# MEM_MUX_3.net
KiCad netlist of a schematic drawn in EAGLE
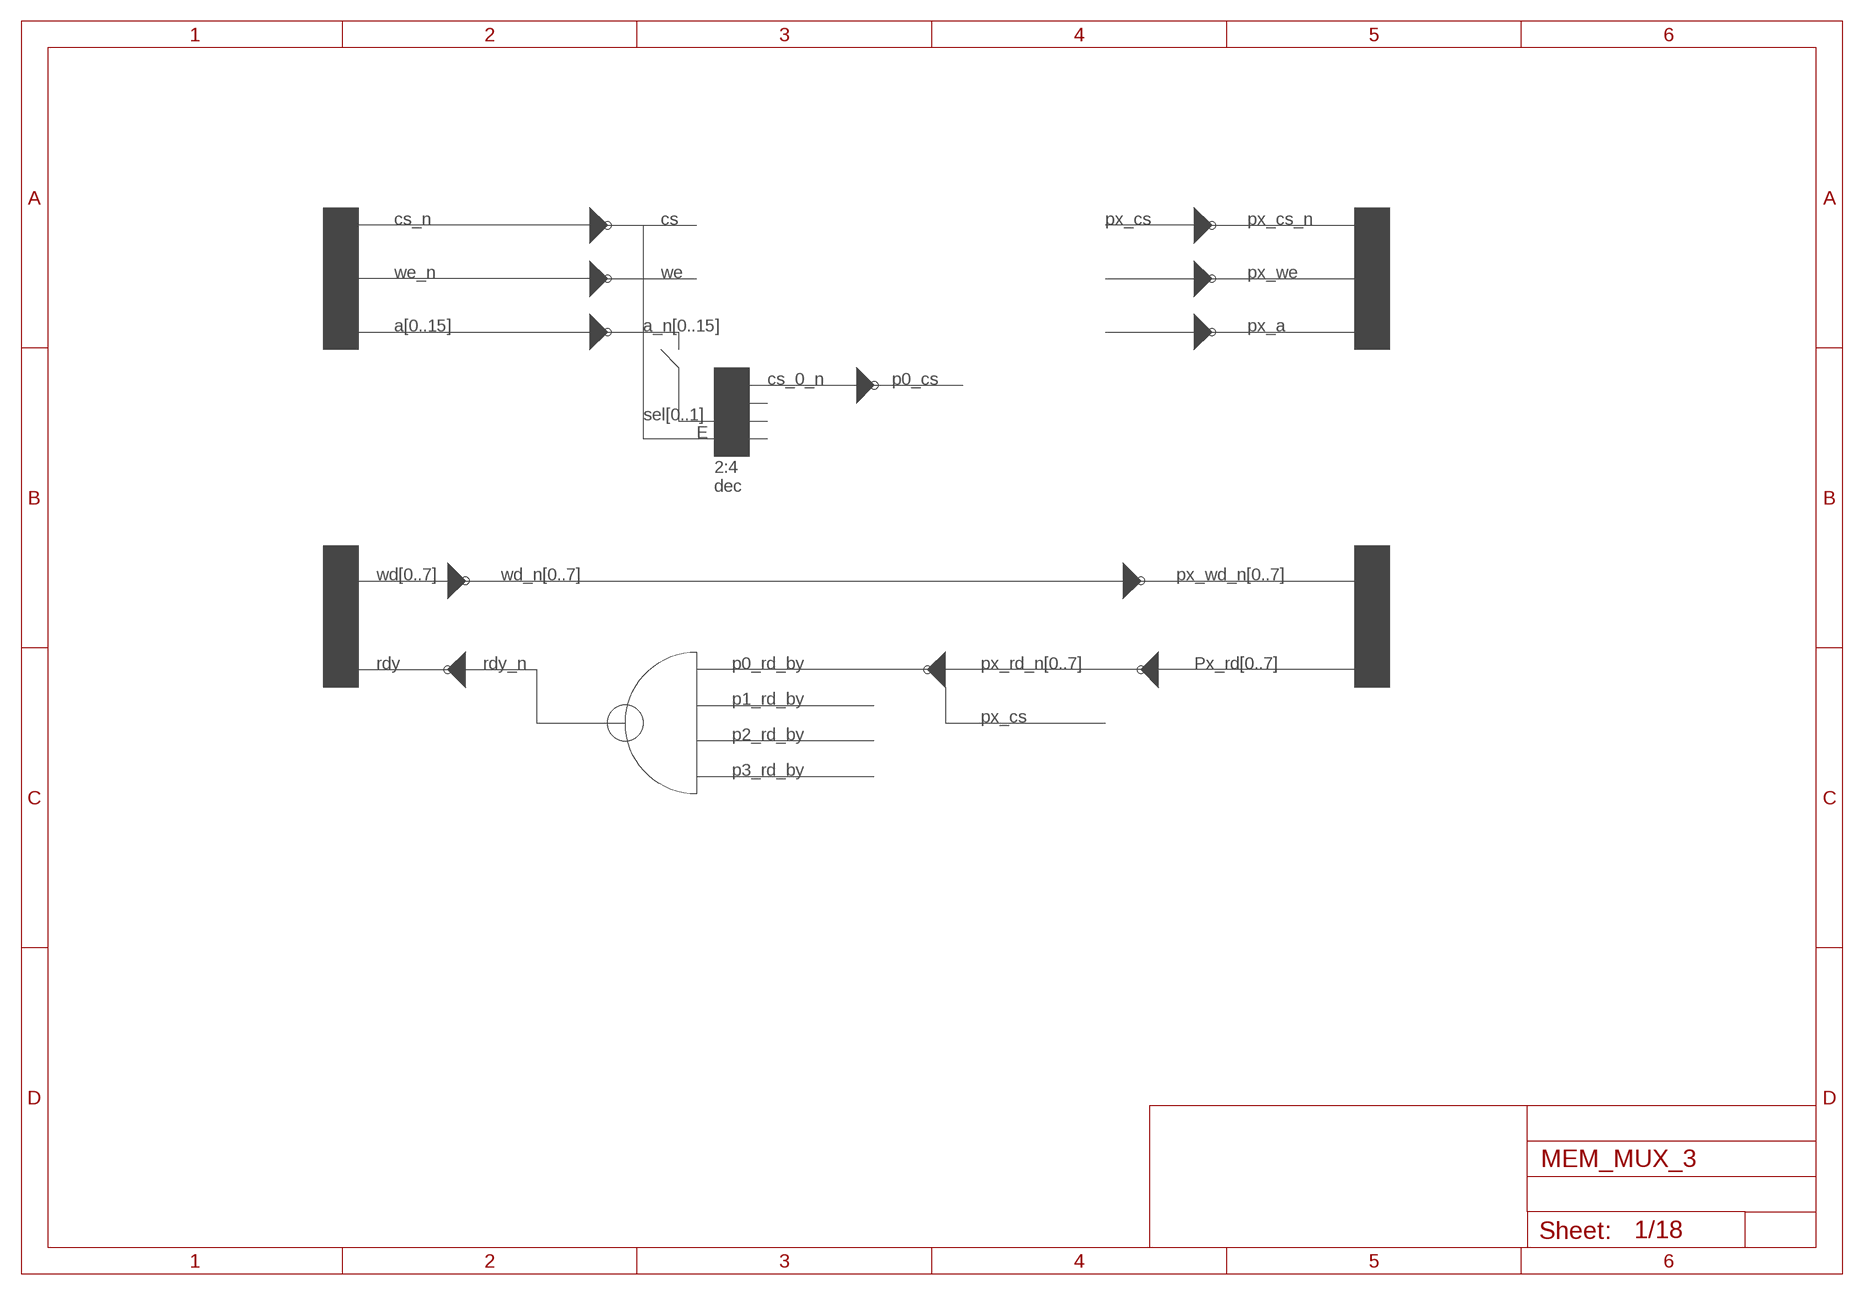
[diagram p0: schematic, sheet 1]
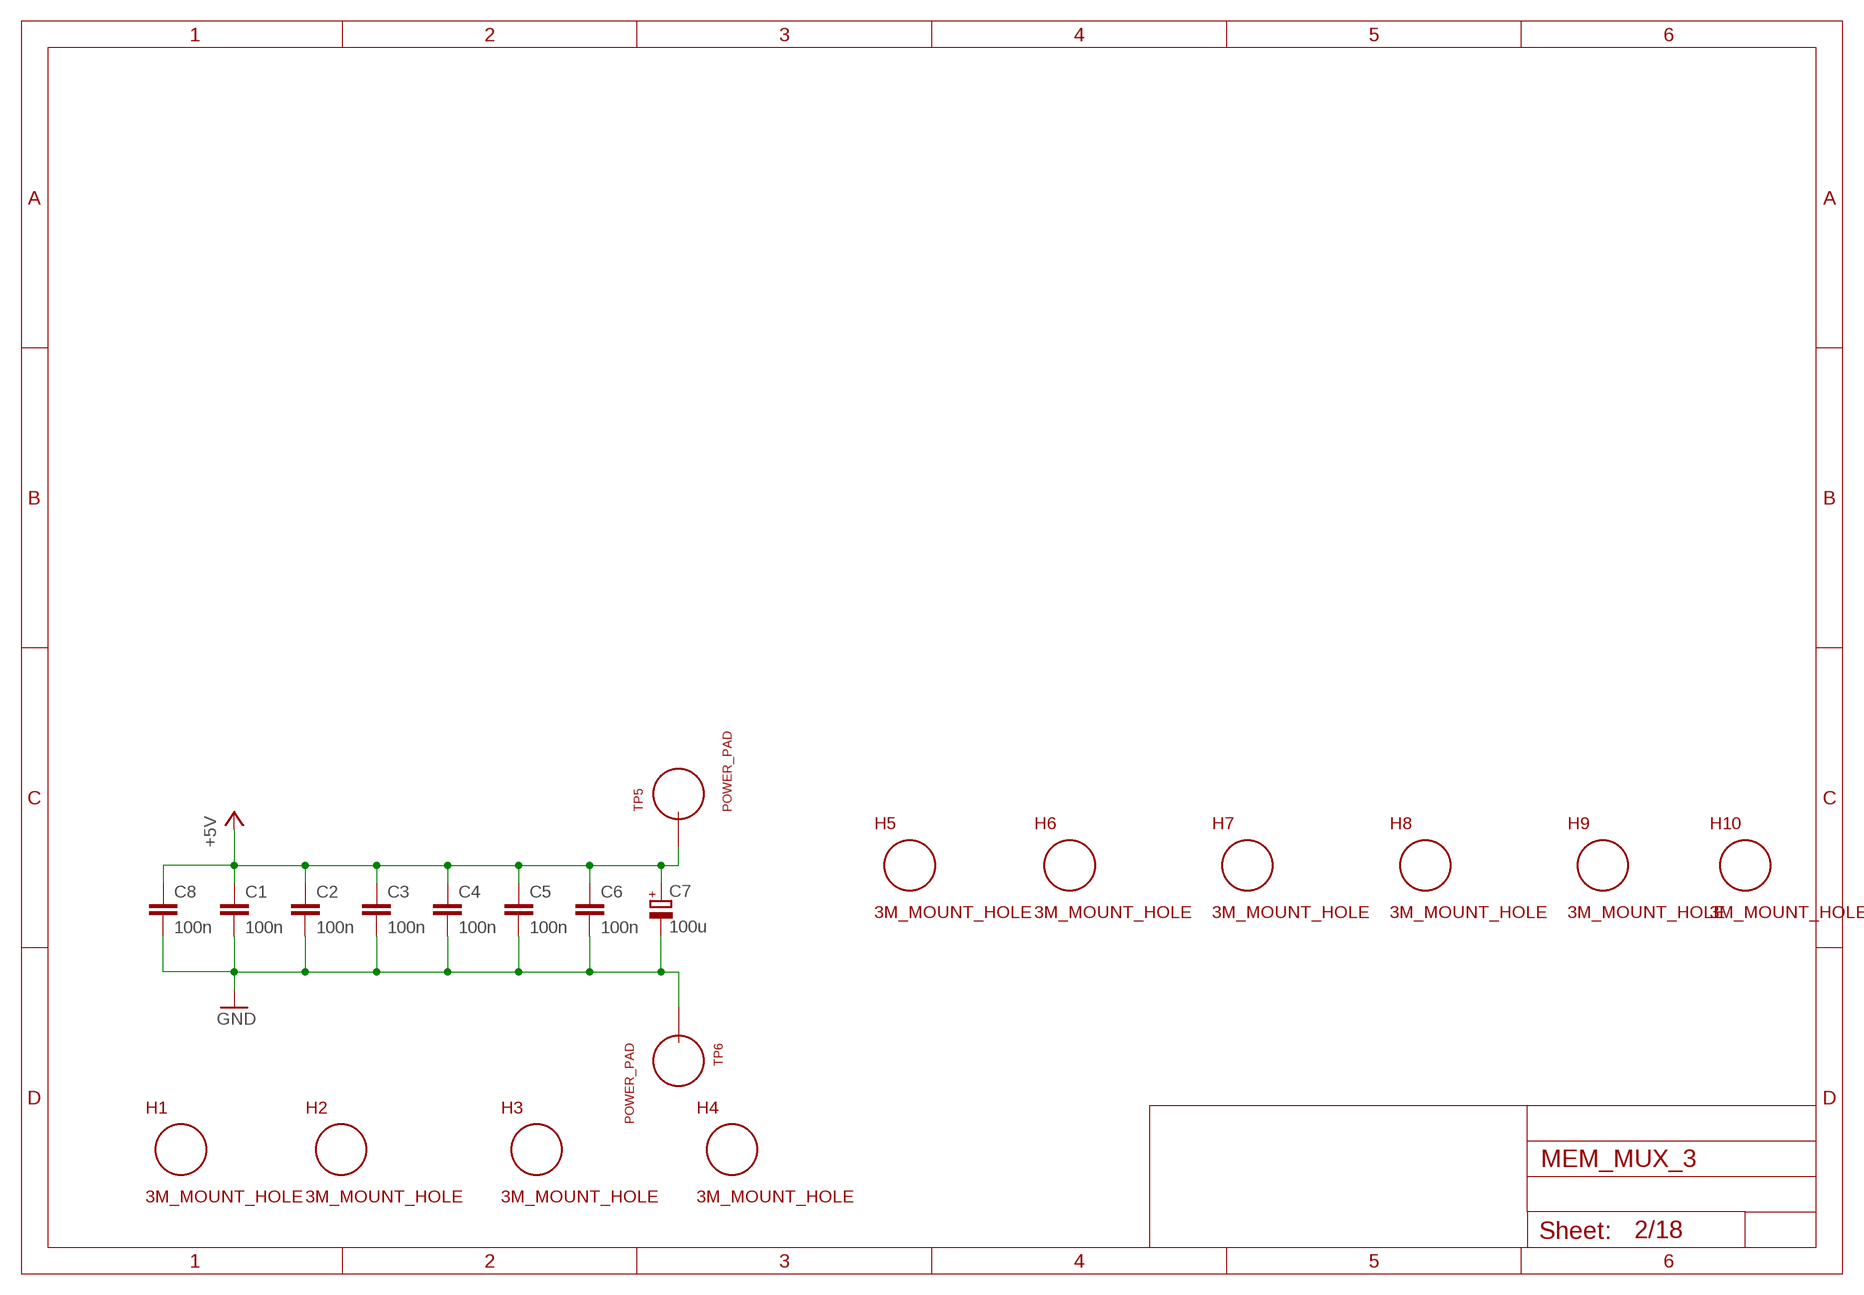
[diagram p1: schematic, sheet 2]
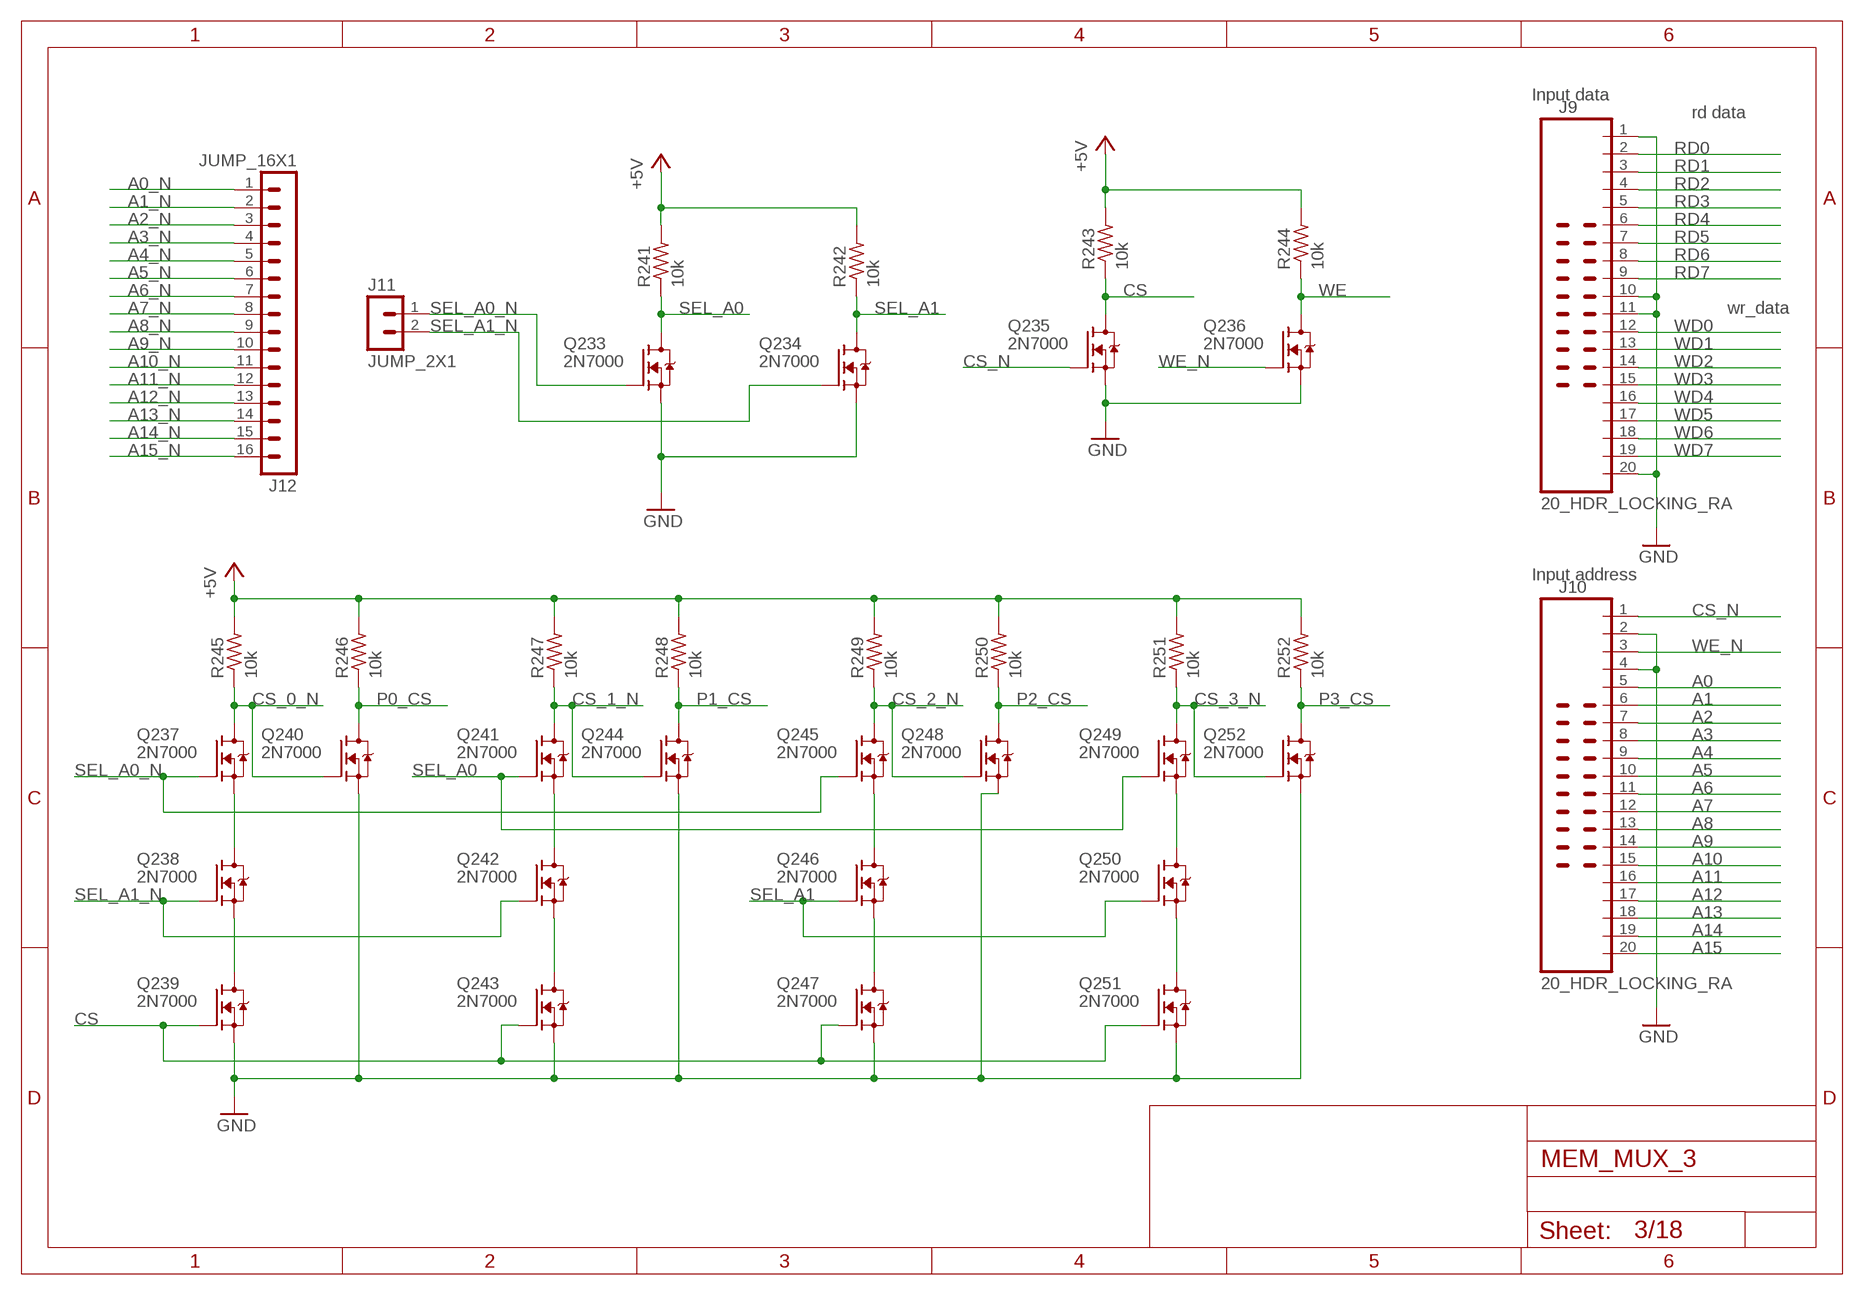
[diagram p2: schematic, sheet 3]
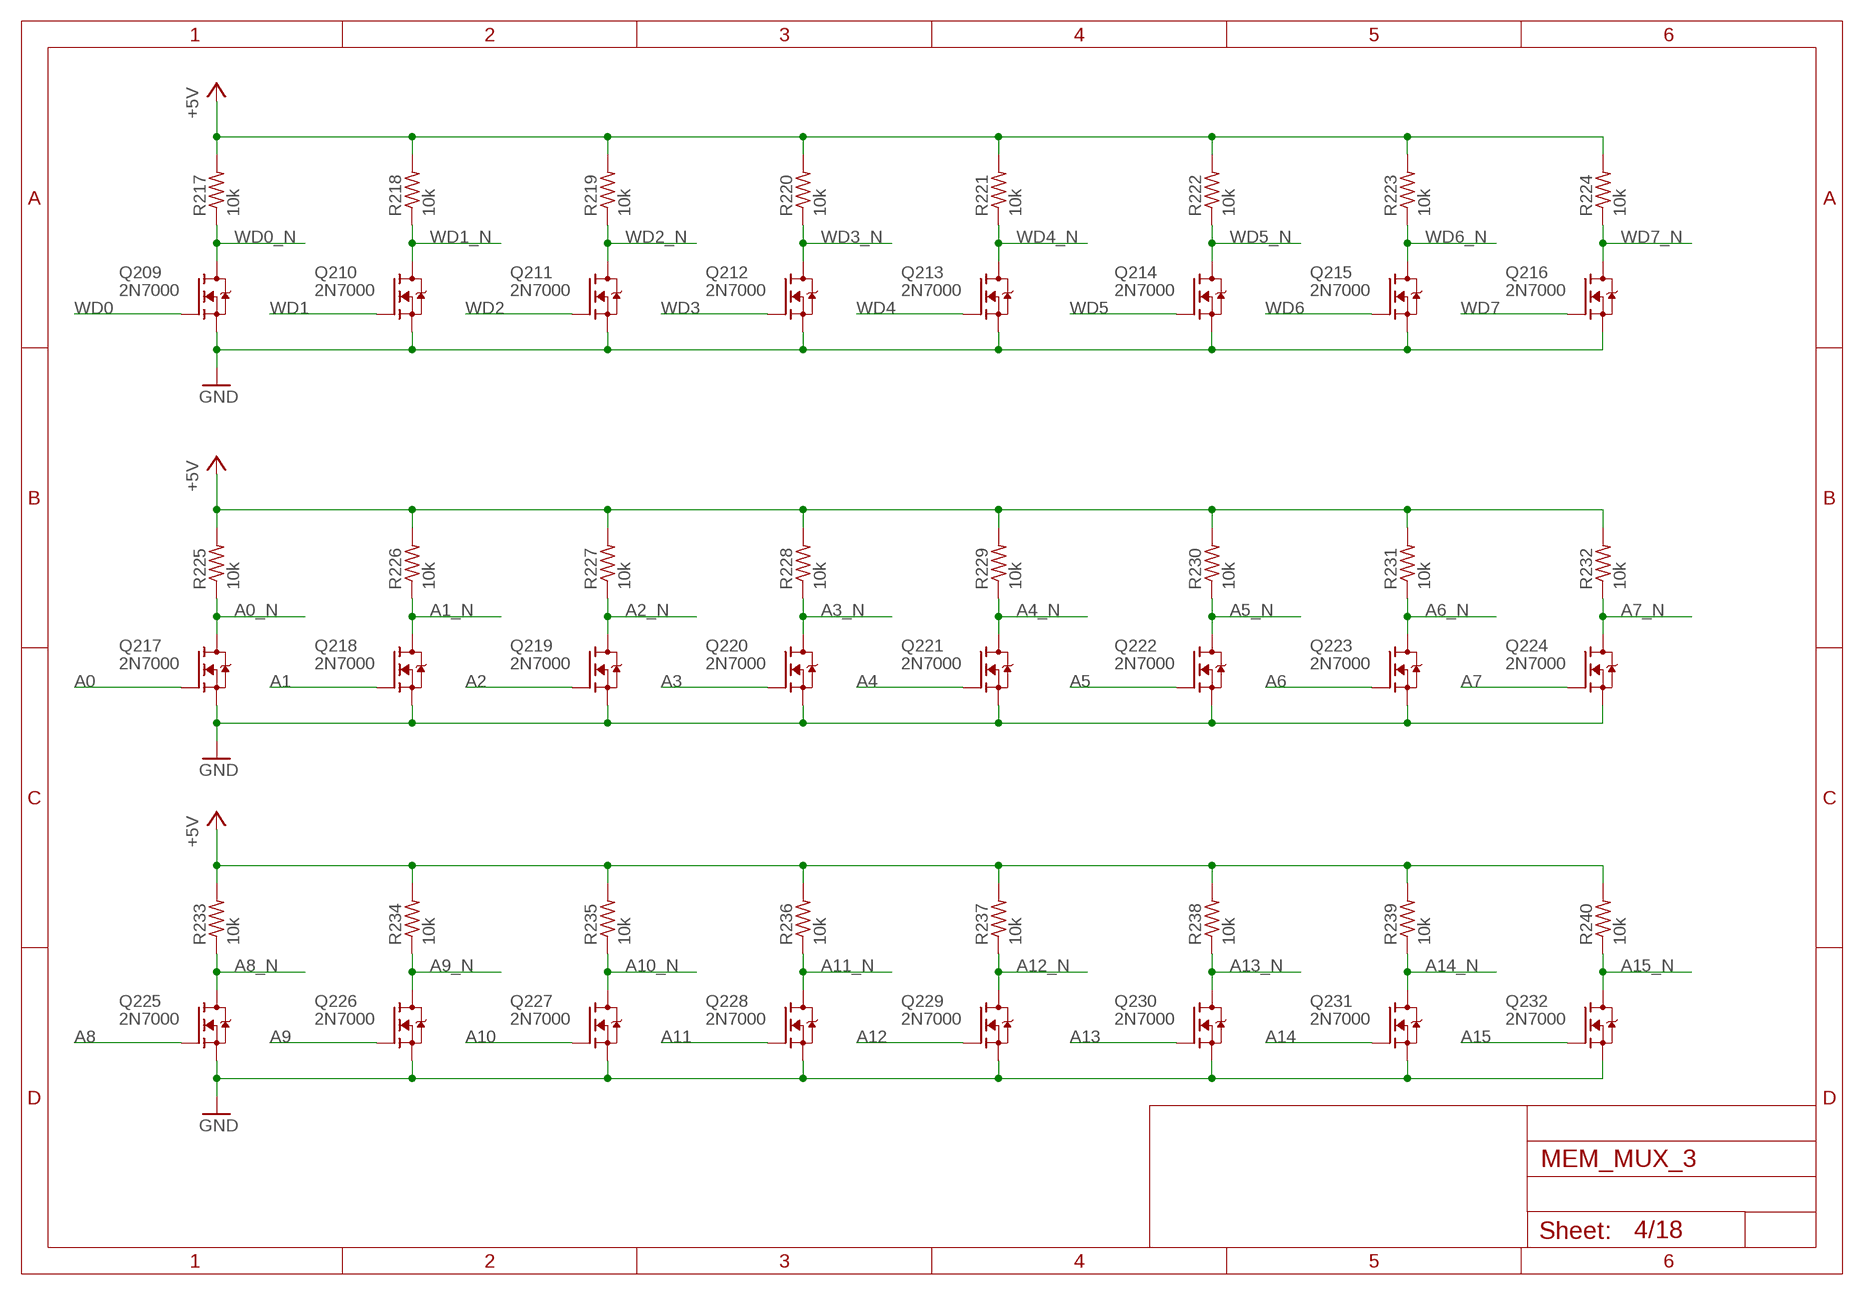
[diagram p3: schematic, sheet 4]
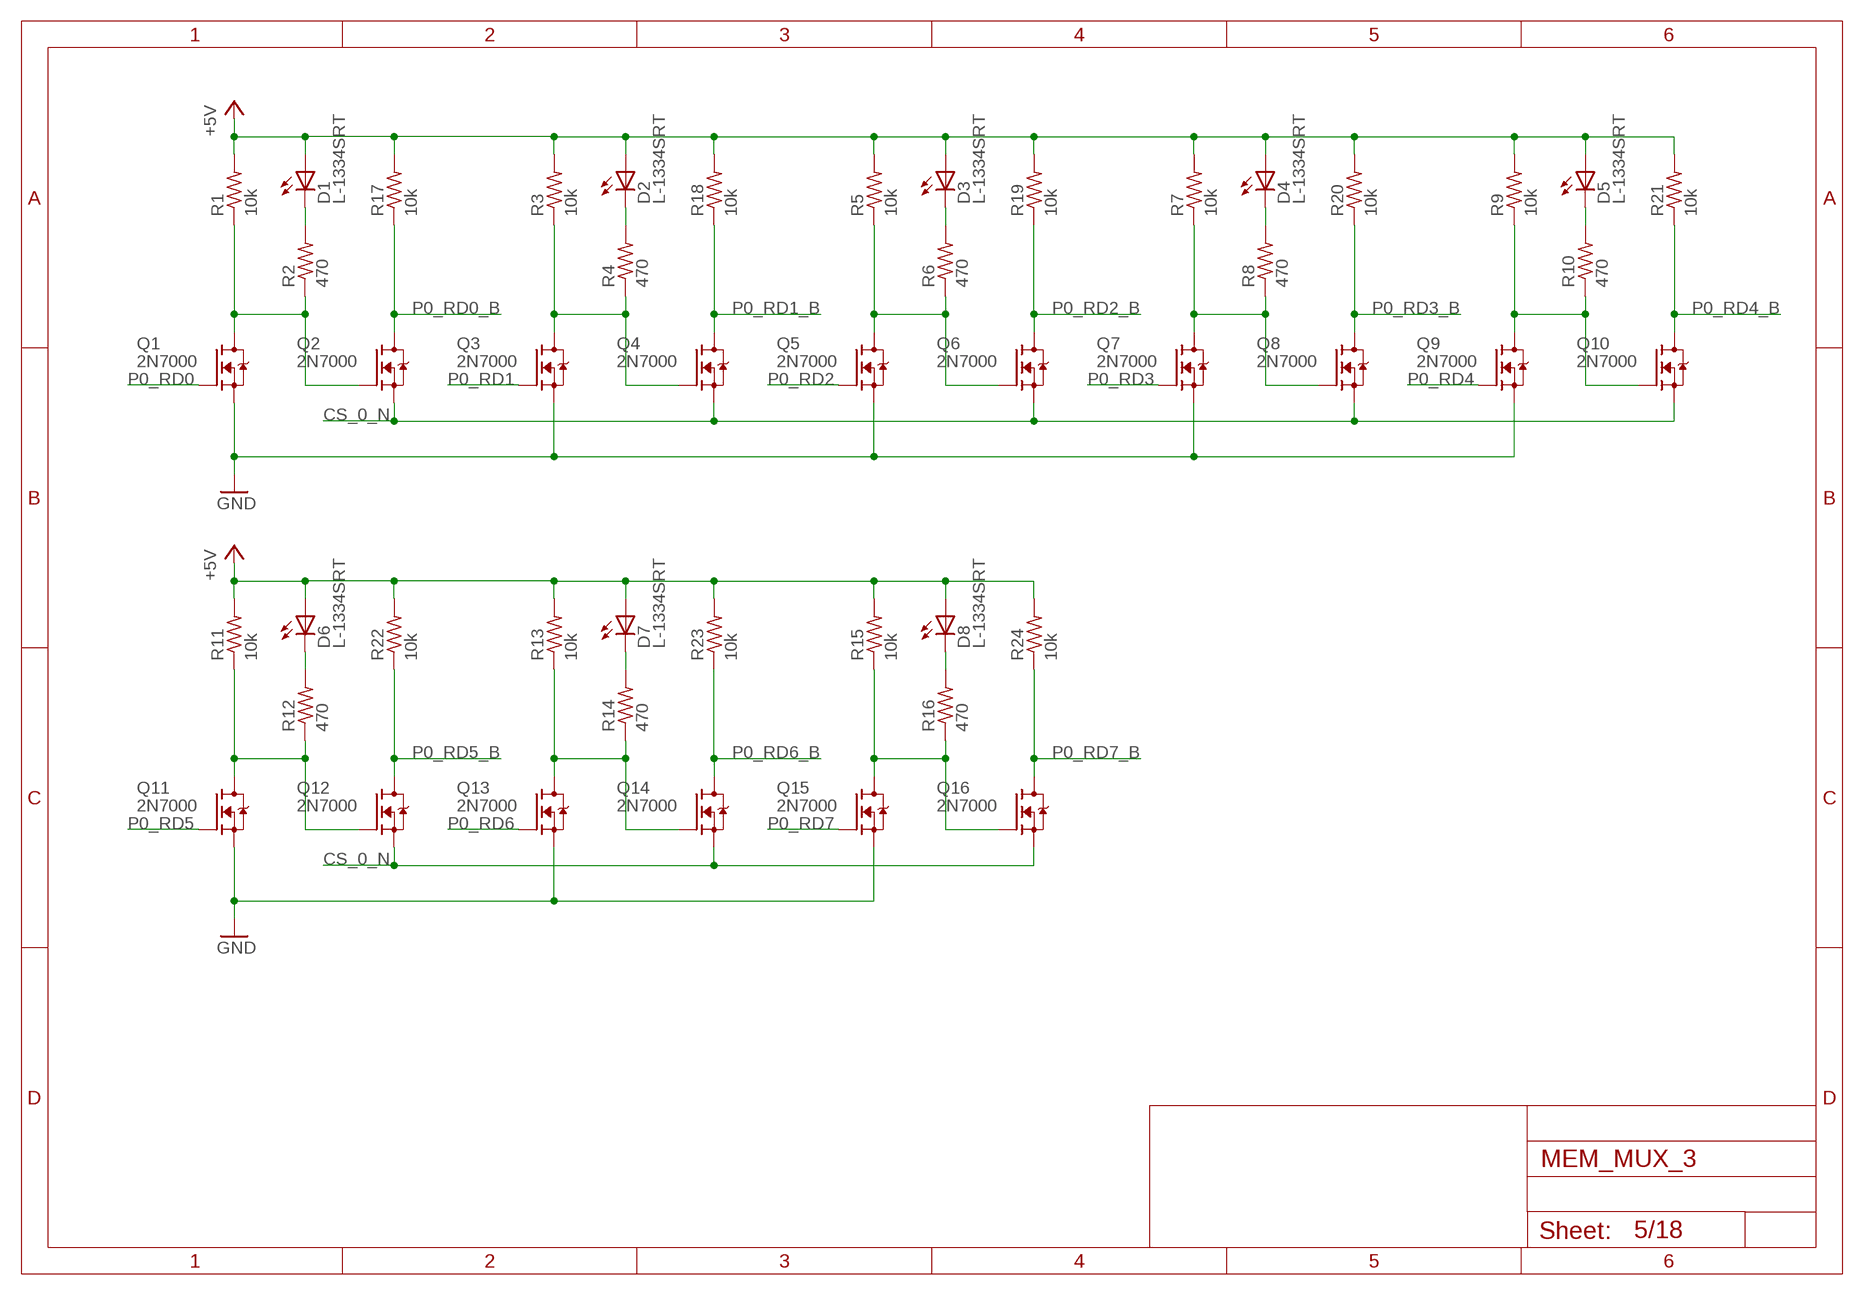
[diagram p4: schematic, sheet 5]
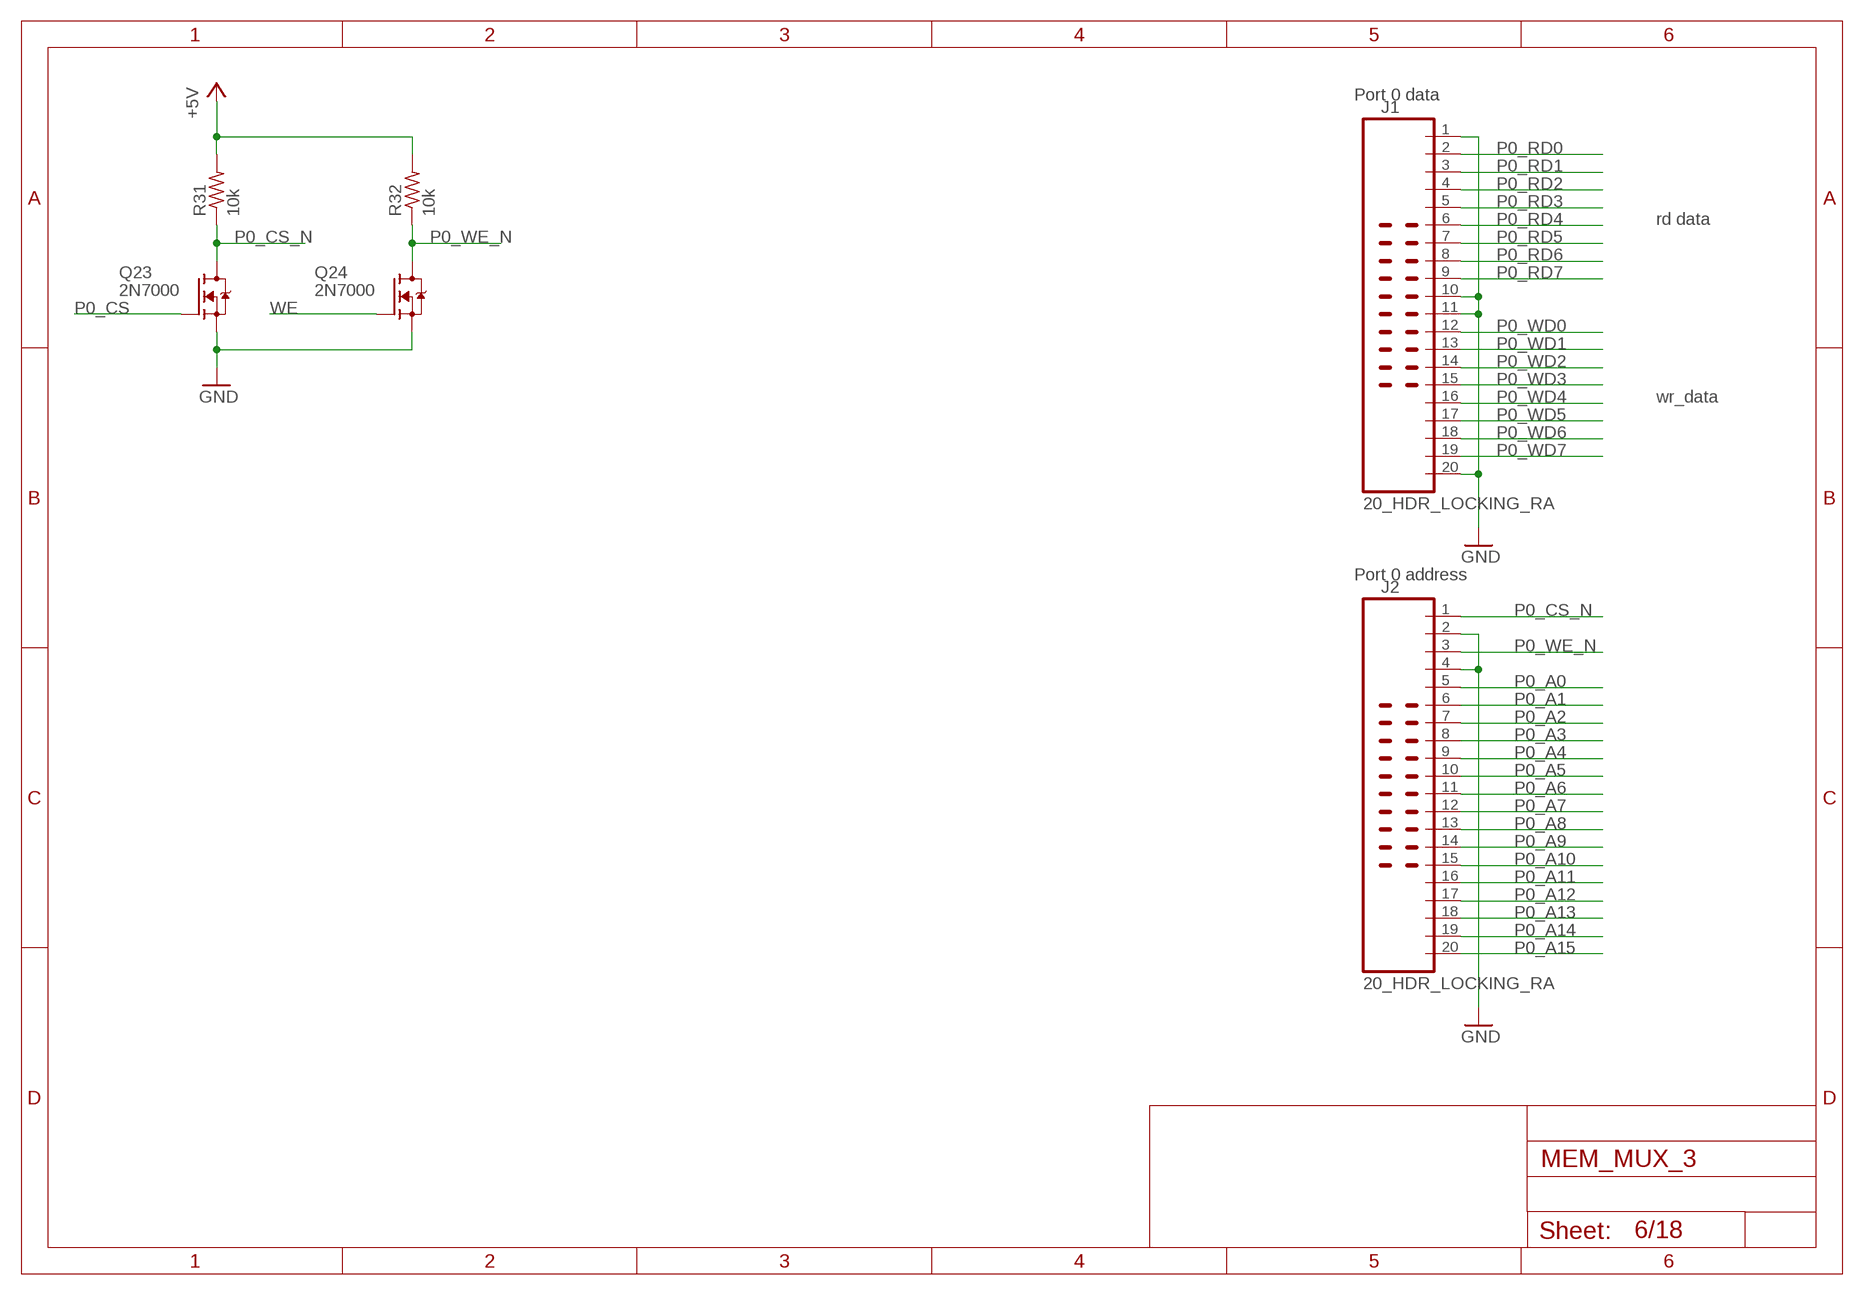
[diagram p5: schematic, sheet 6]
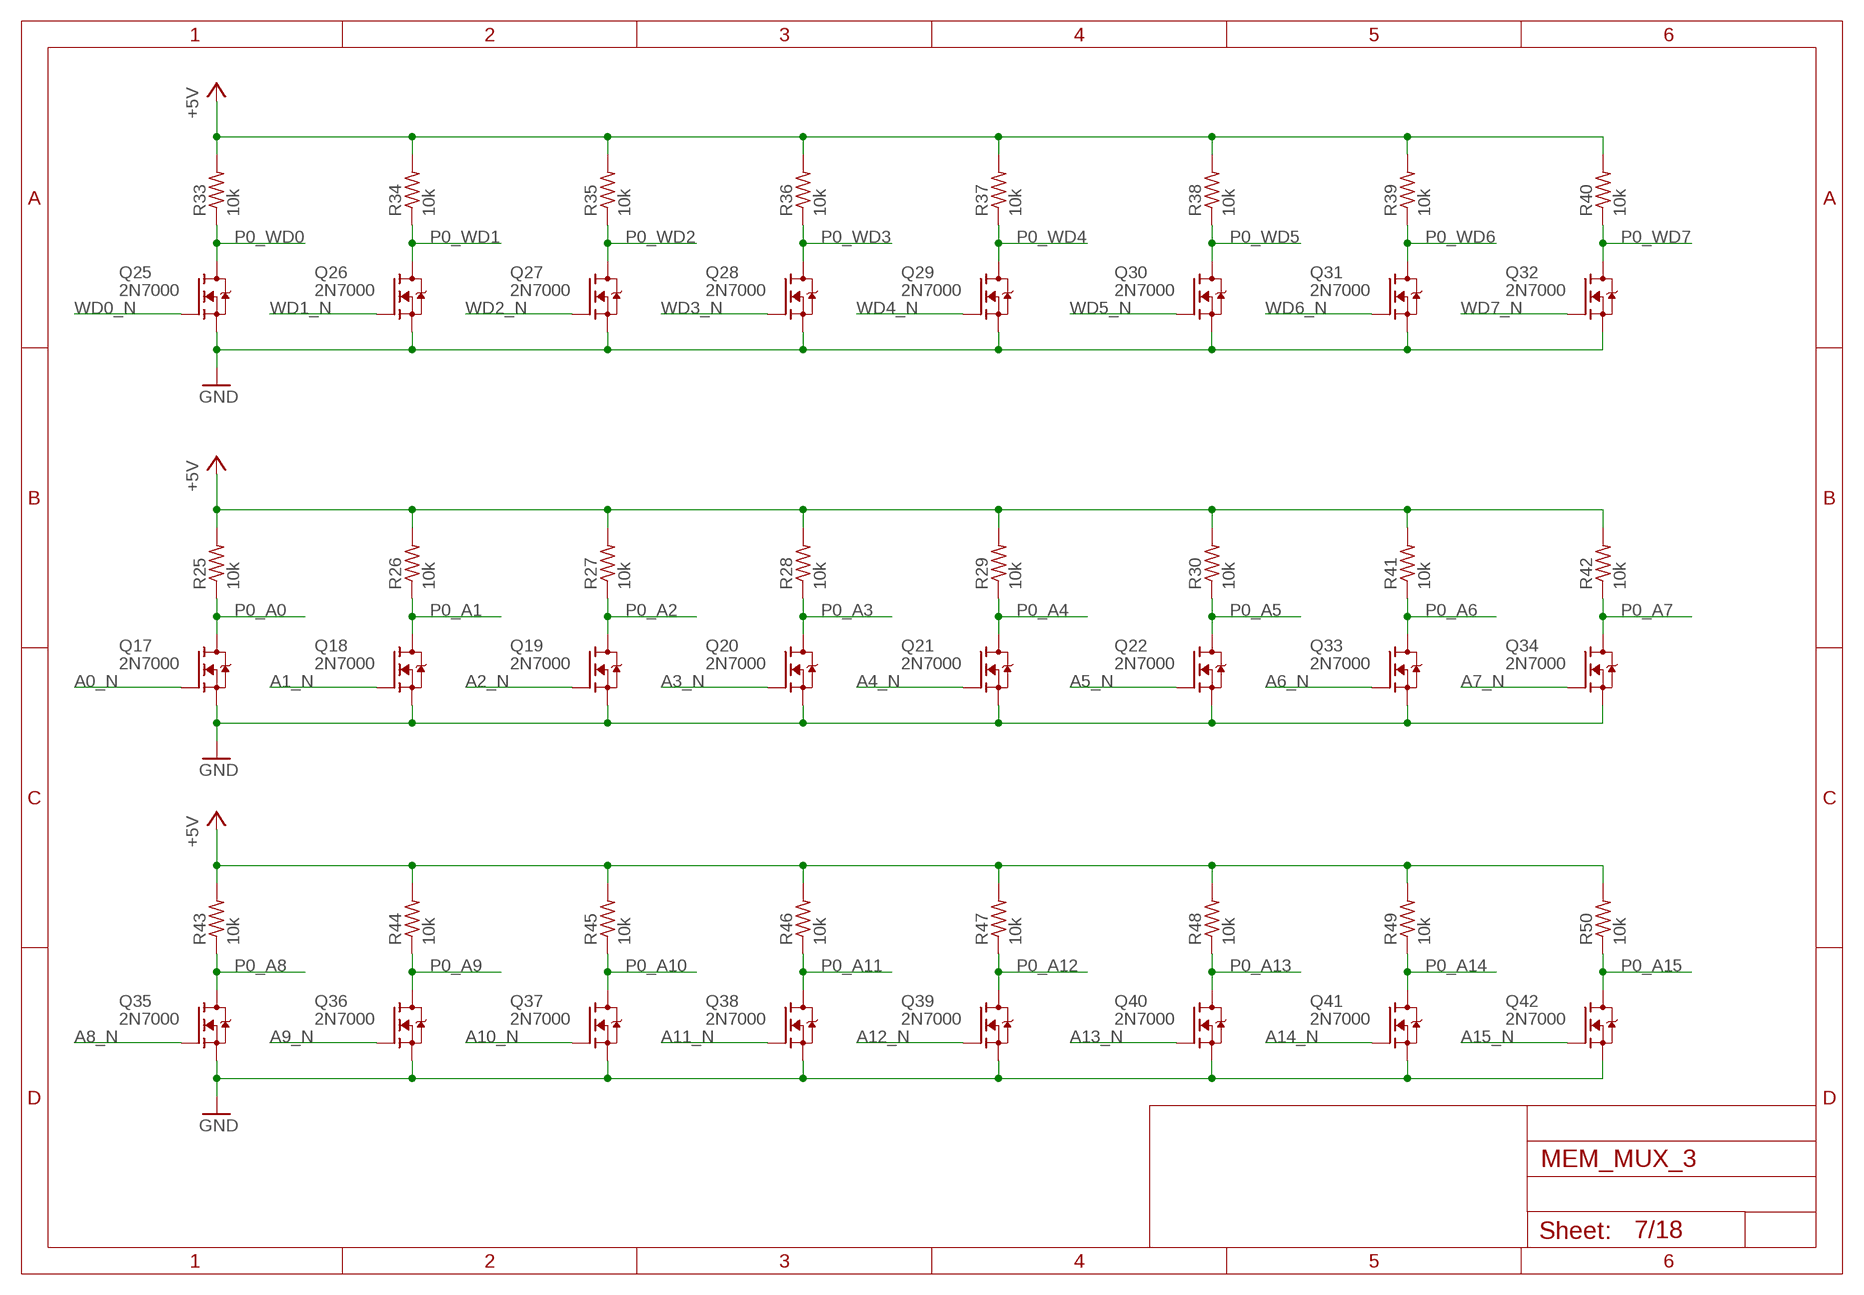
[diagram p6: schematic, sheet 7]
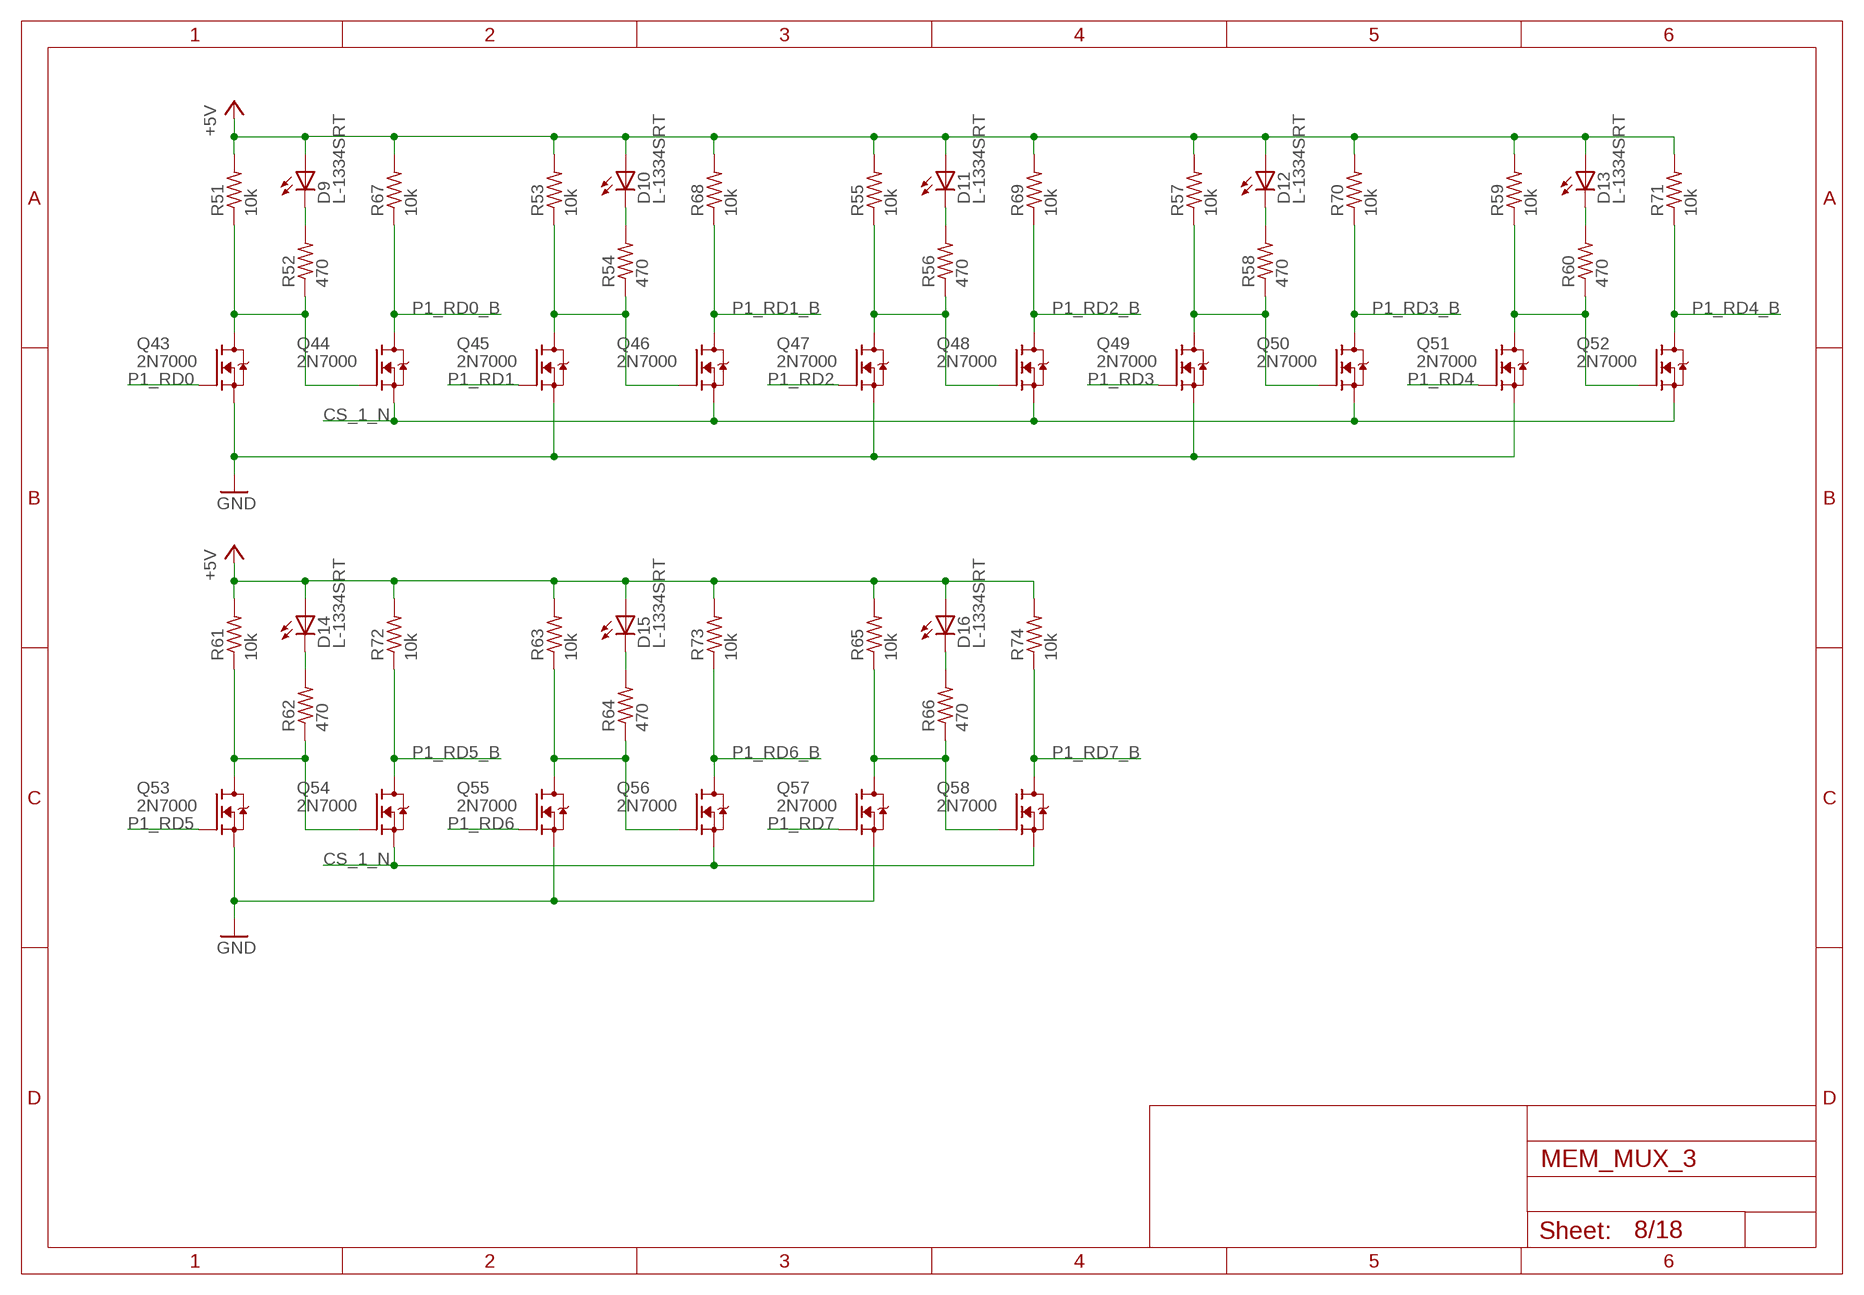
[diagram p7: schematic, sheet 8]
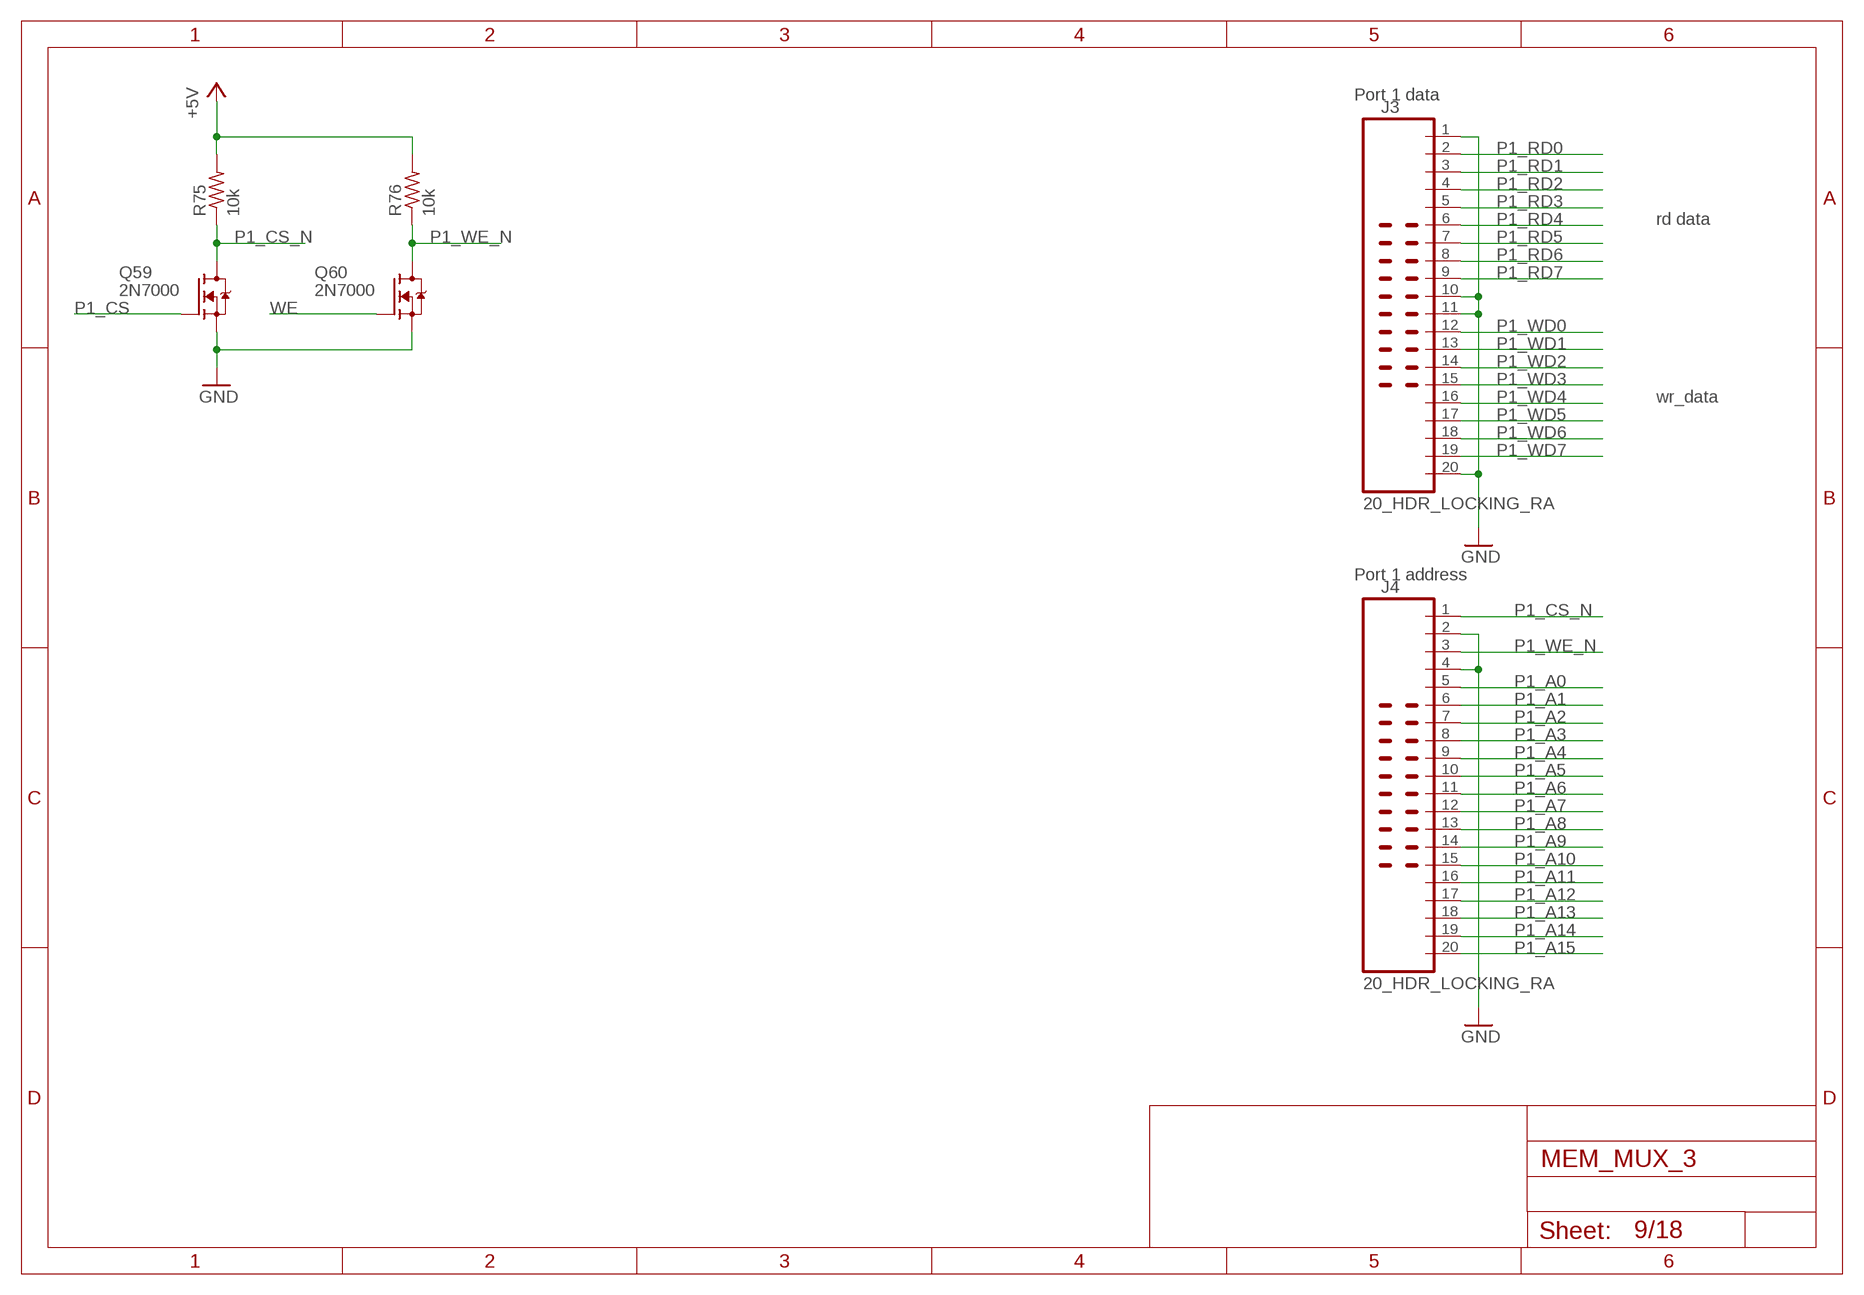
[diagram p8: schematic, sheet 9]
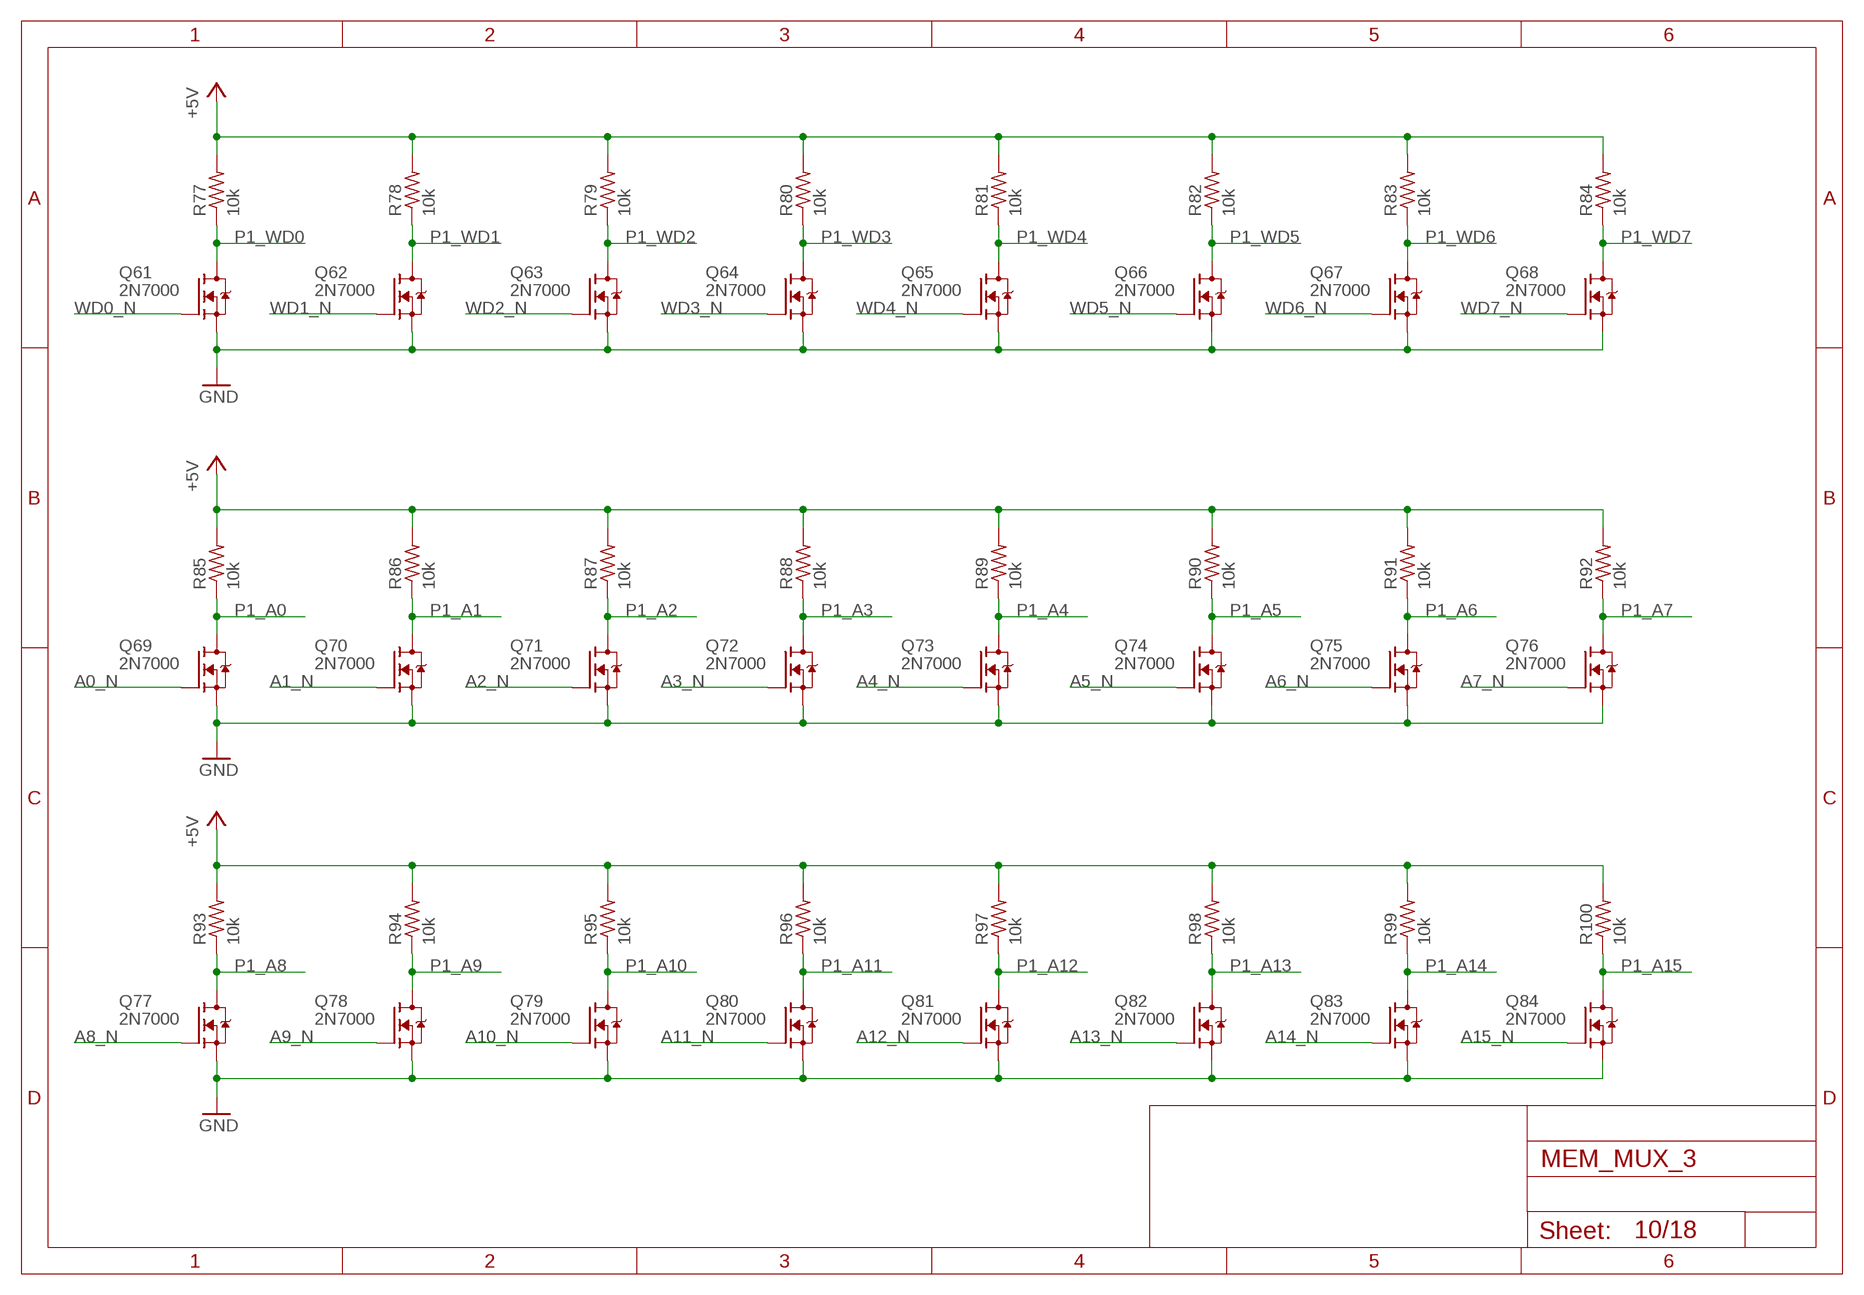
[diagram p9: schematic, sheet 10]
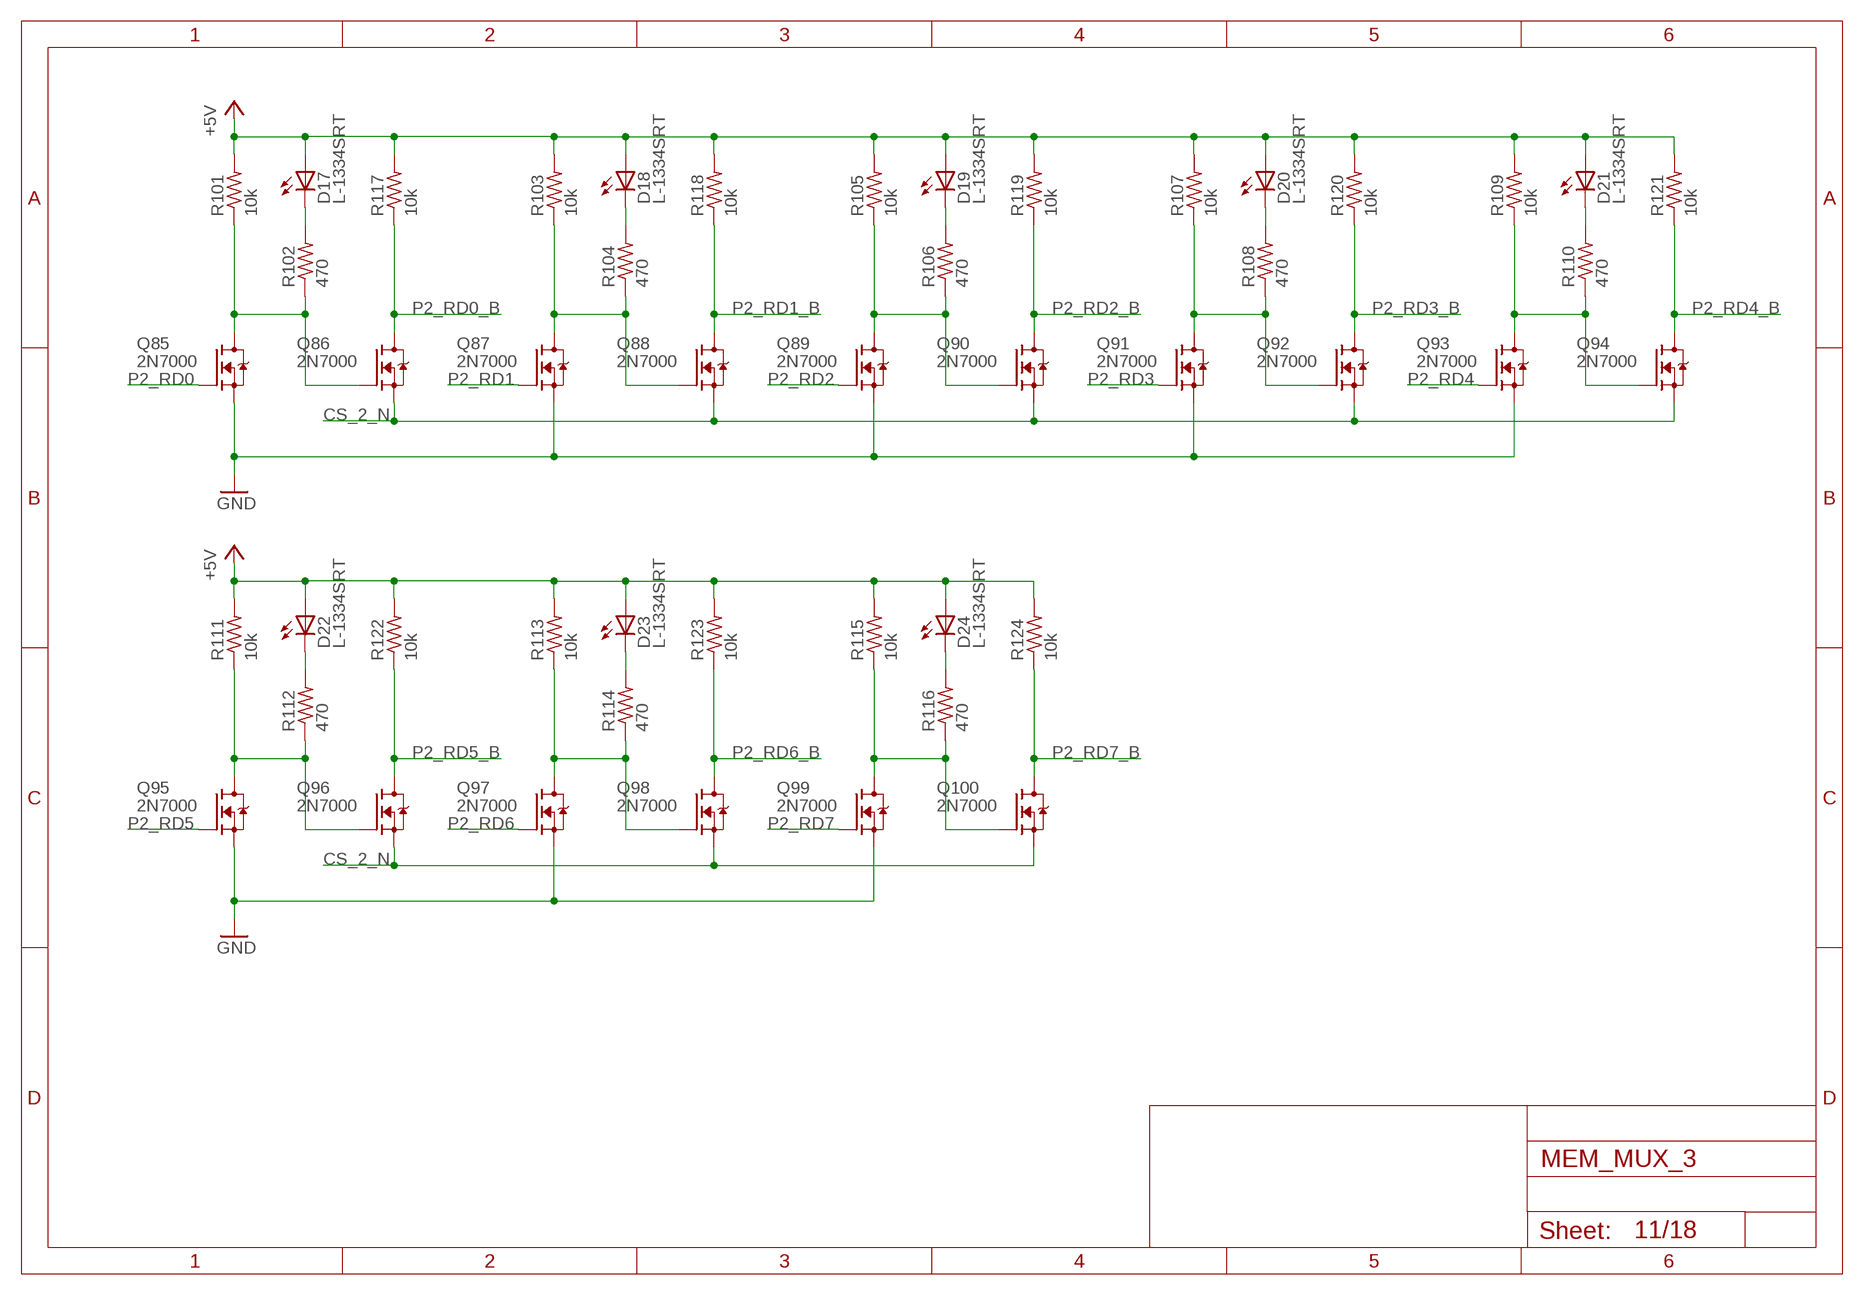
[diagram p10: schematic, sheet 11]
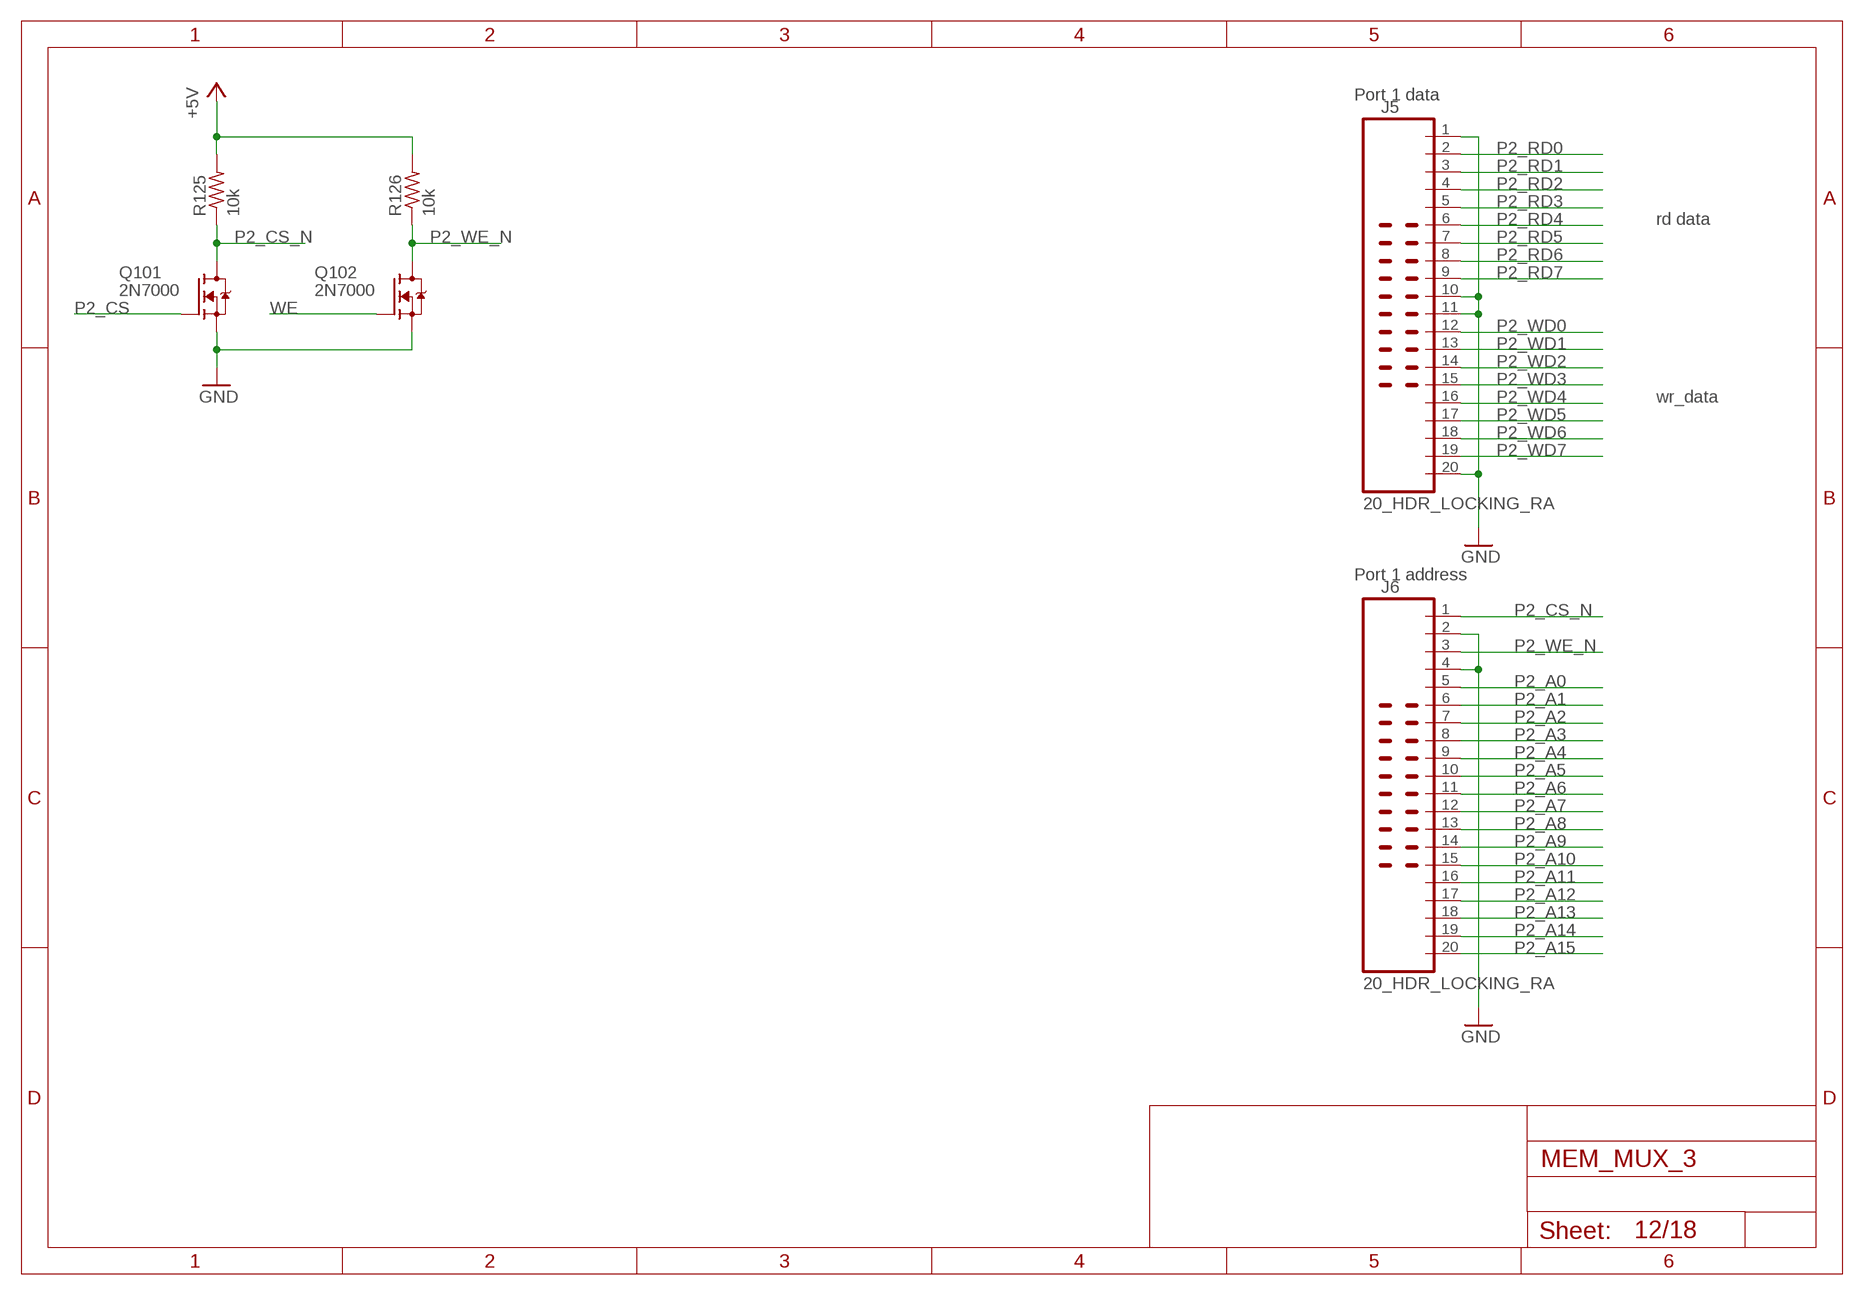
[diagram p11: schematic, sheet 12]
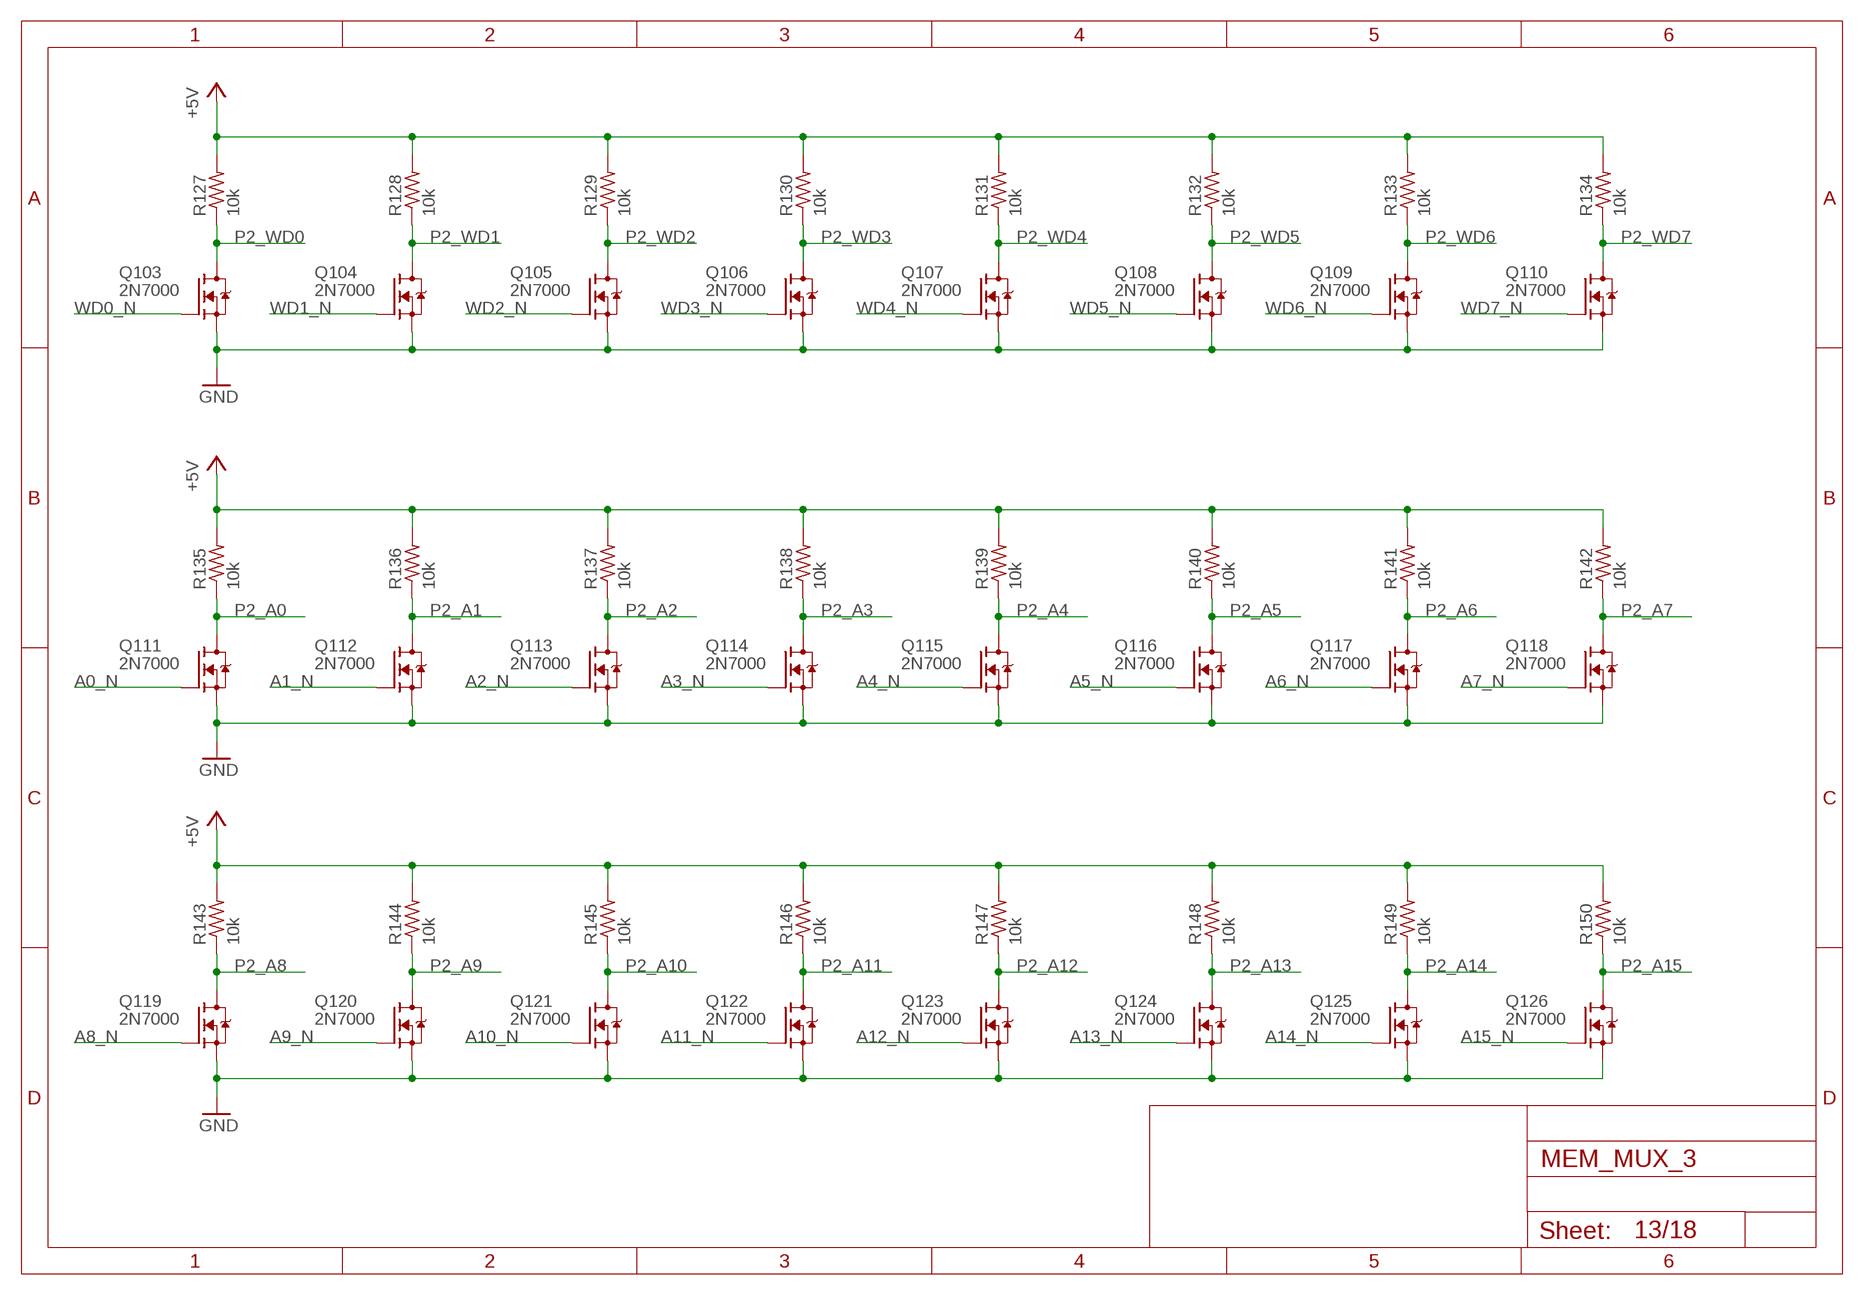
[diagram p12: schematic, sheet 13]
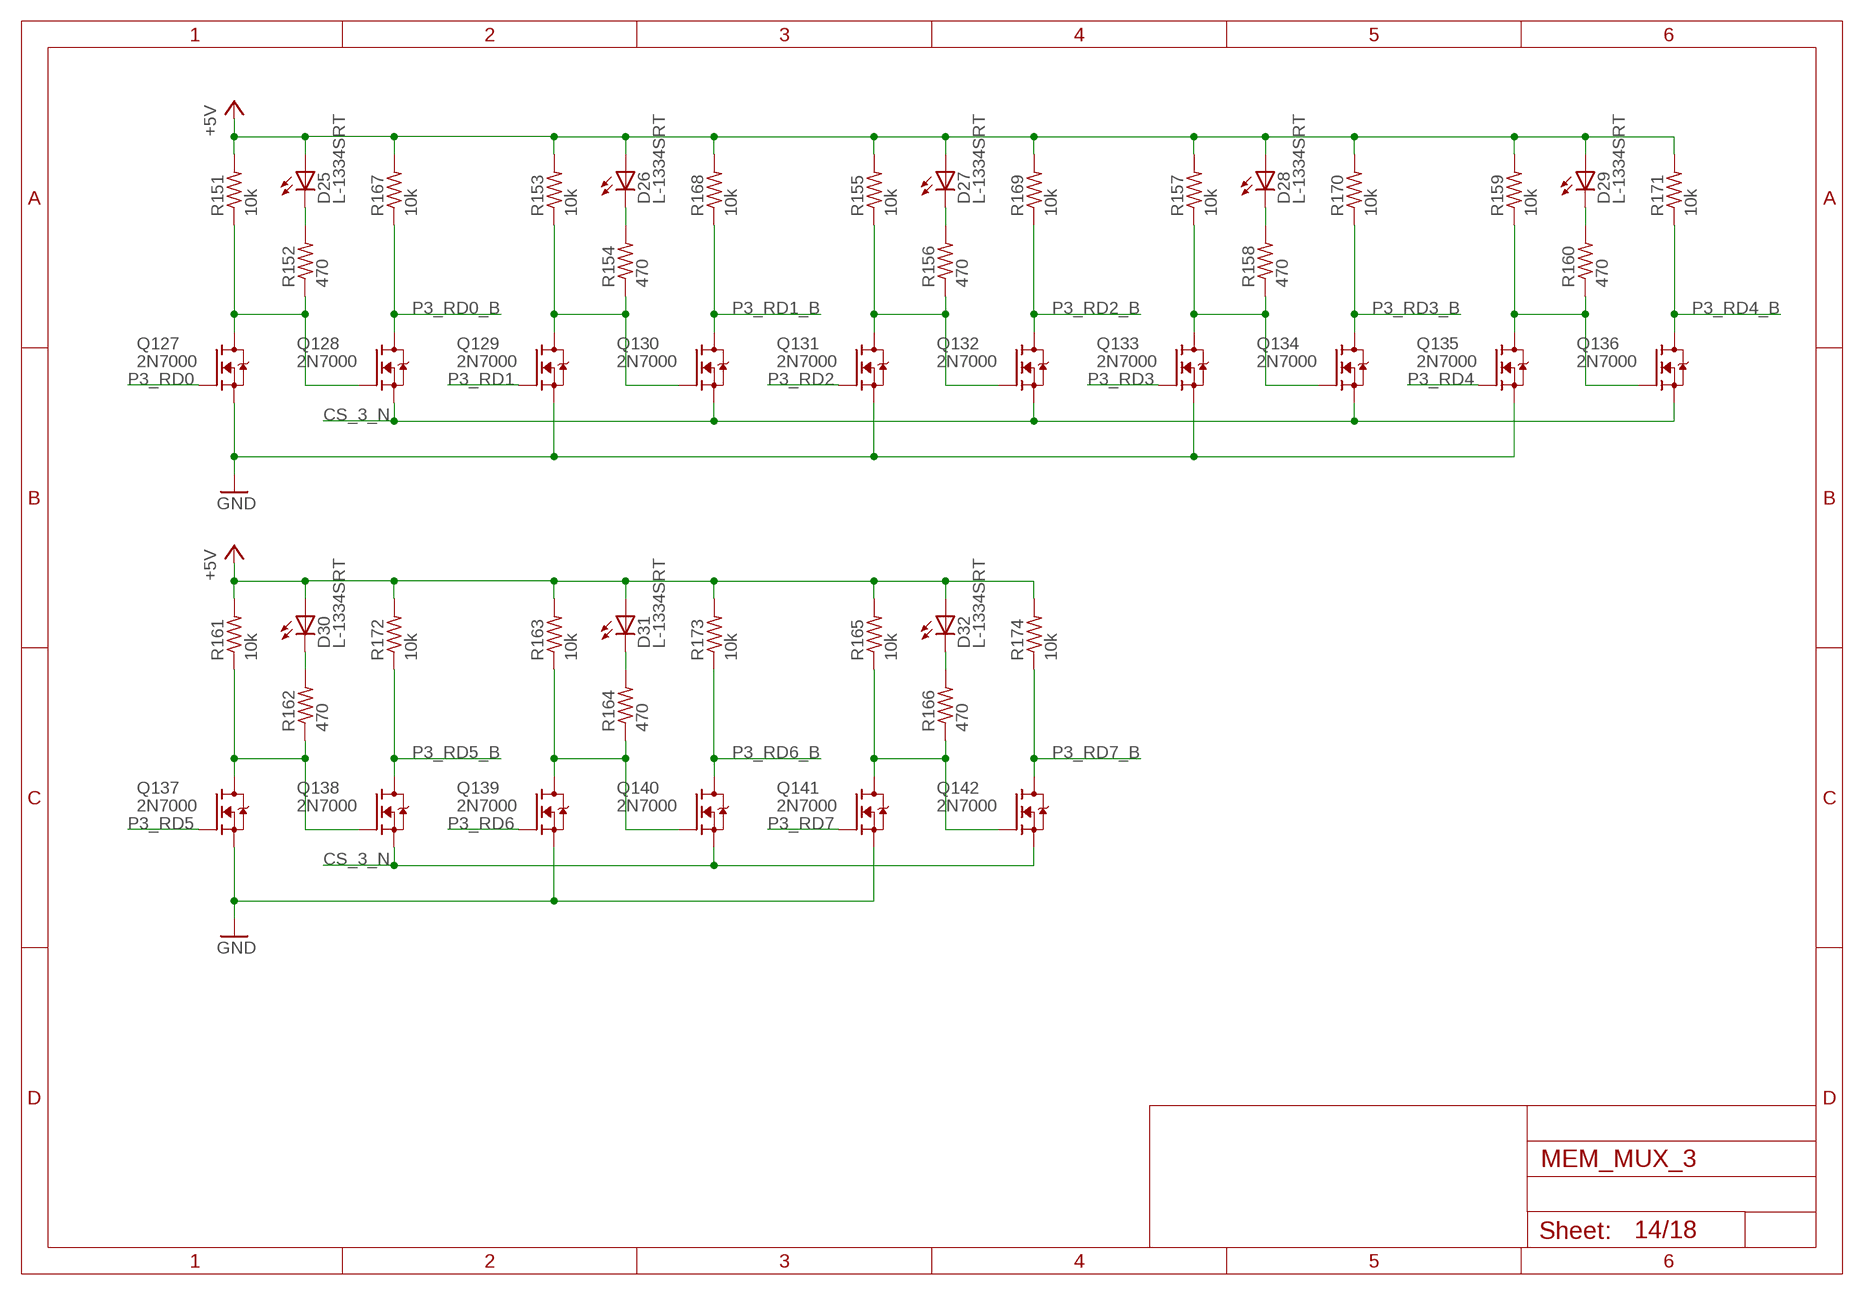
[diagram p13: schematic, sheet 14]
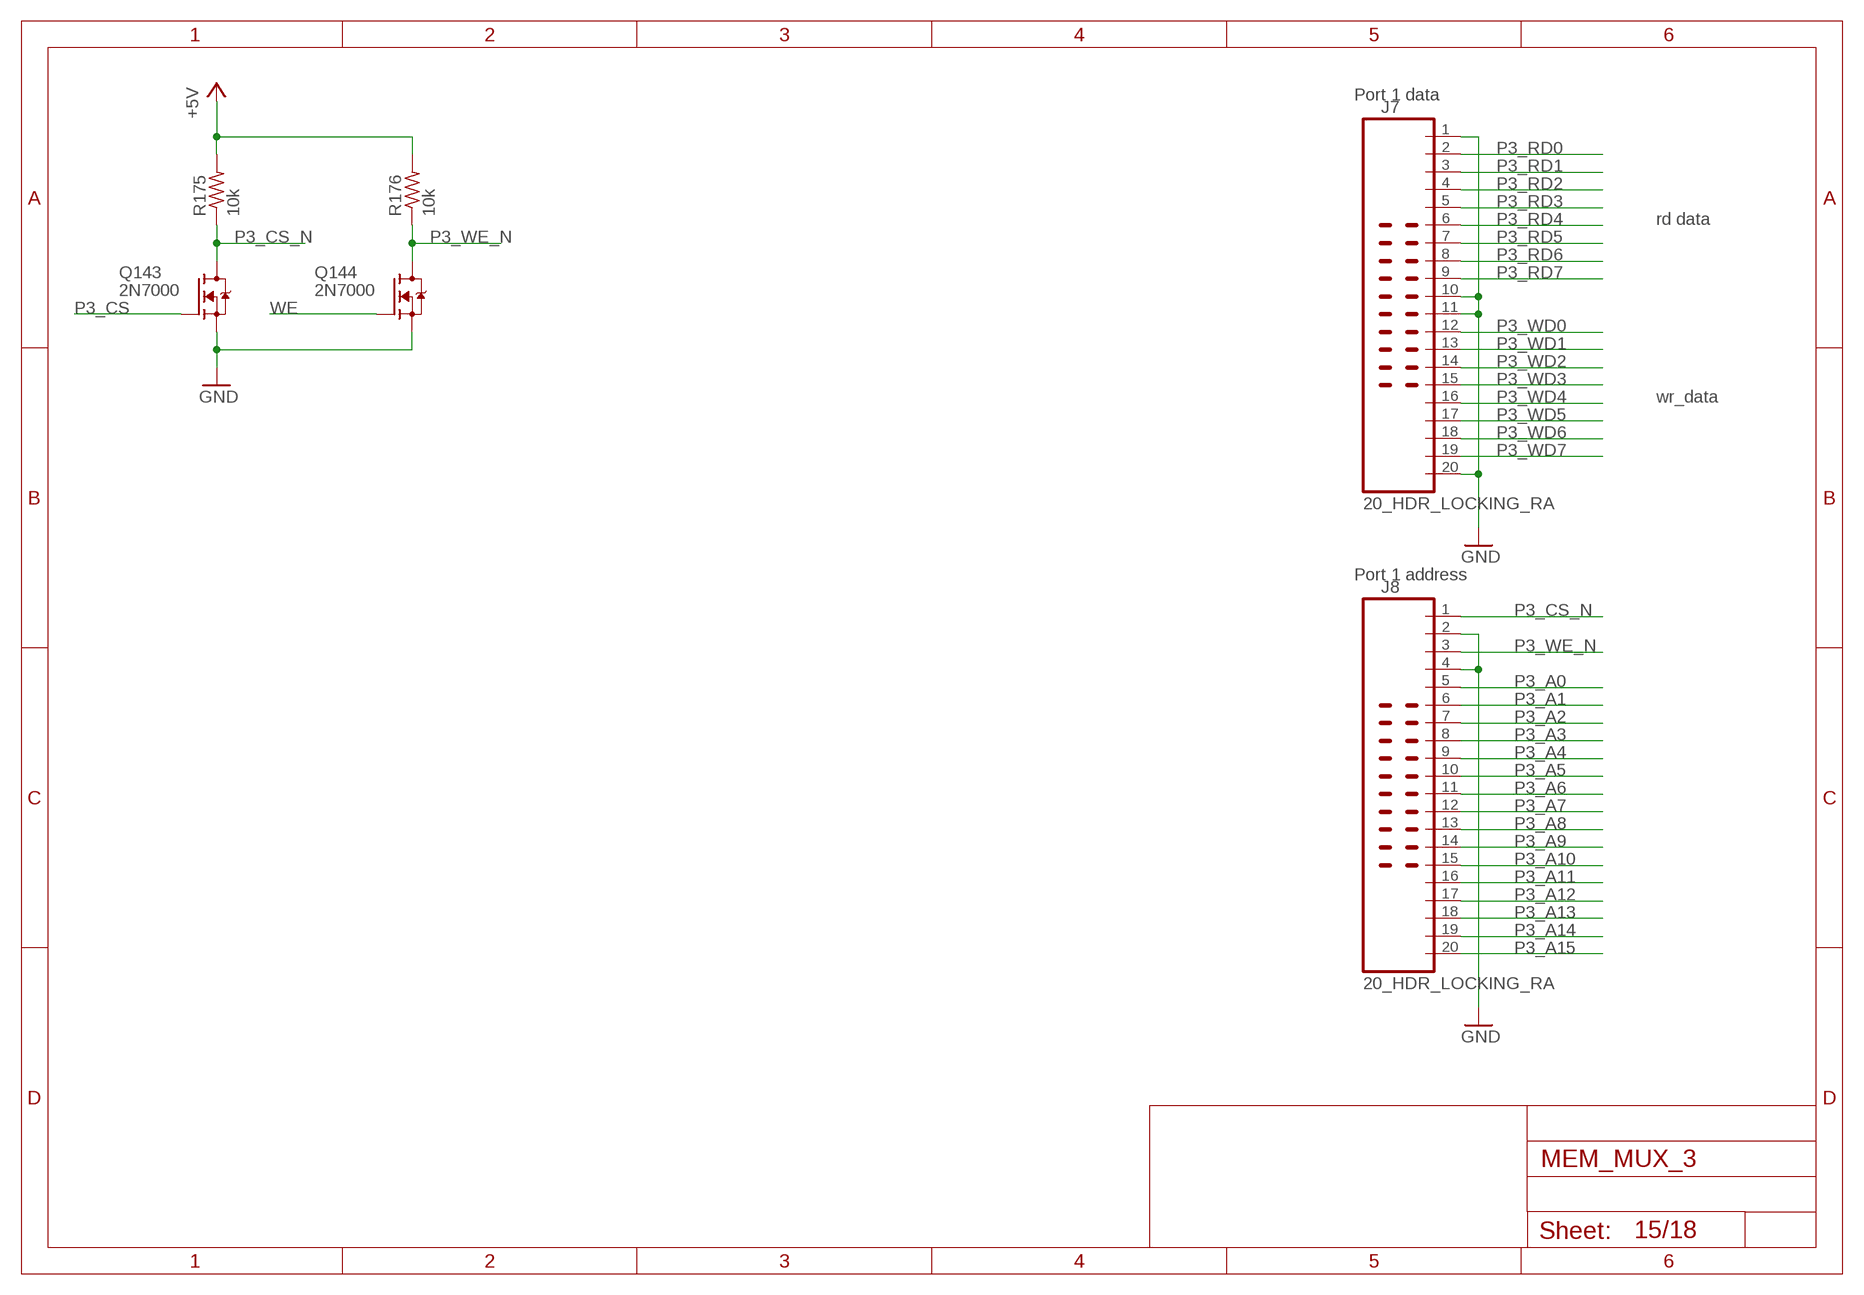
[diagram p14: schematic, sheet 15]
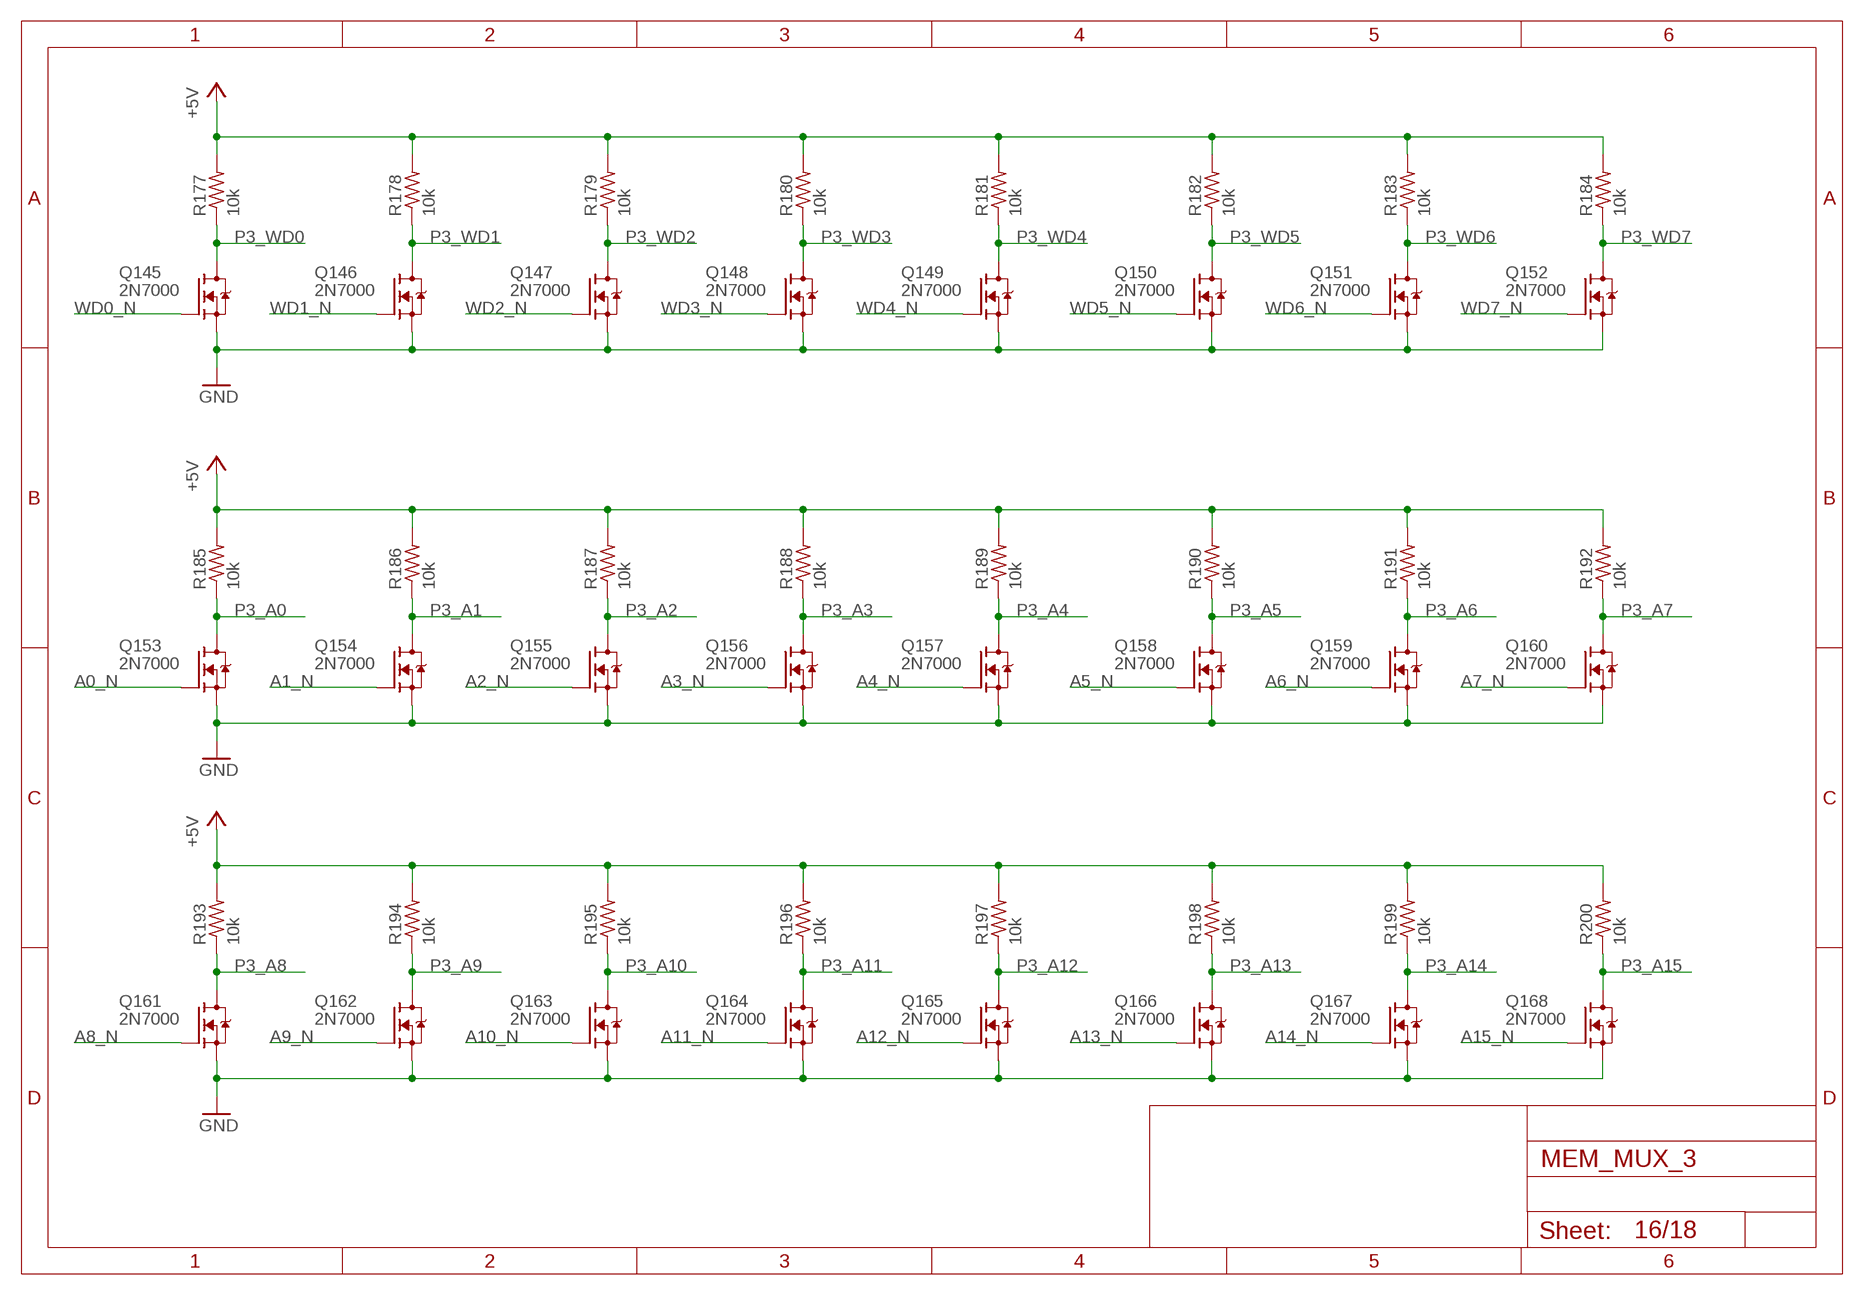
[diagram p15: schematic, sheet 16]
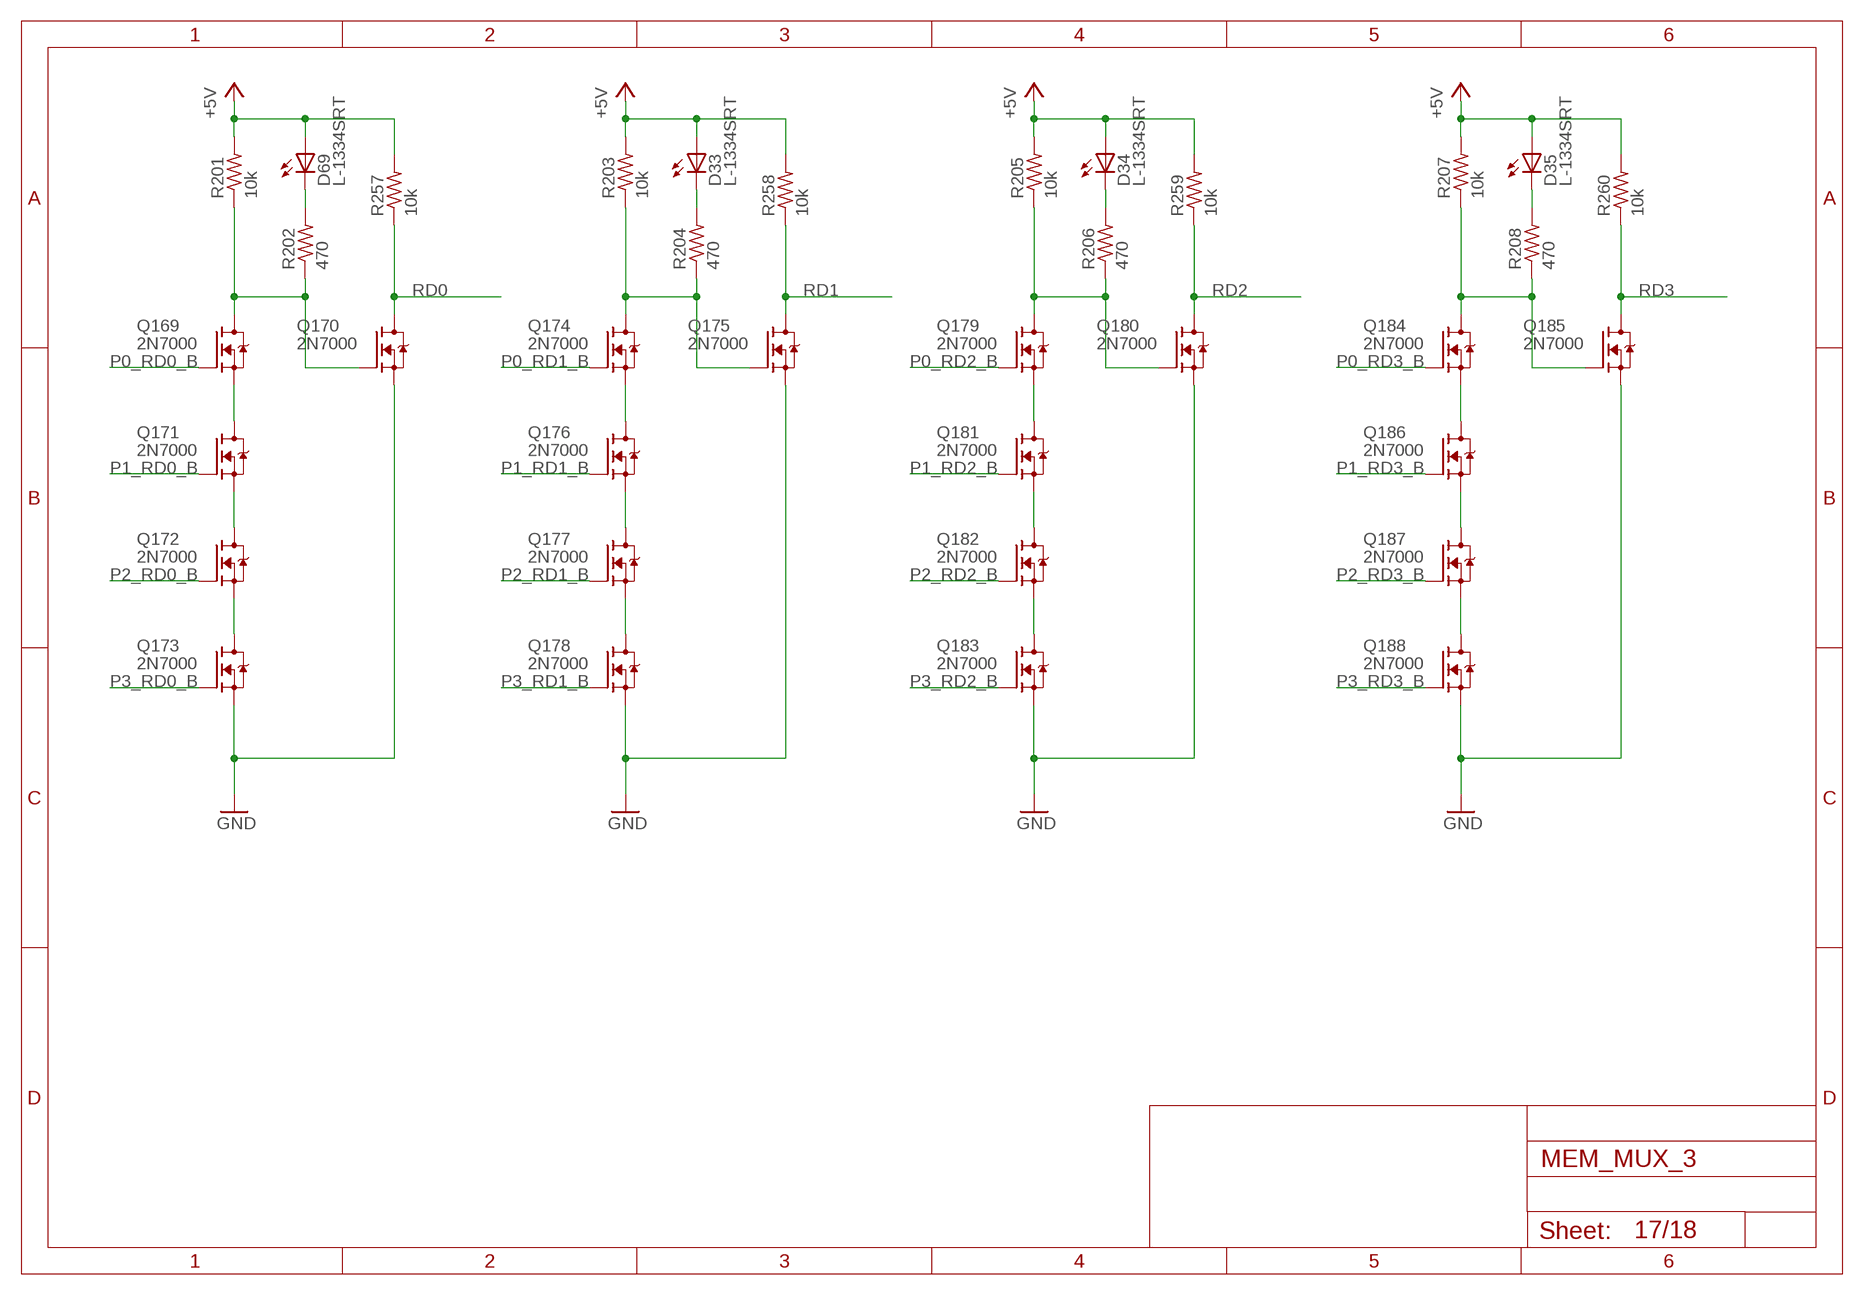
[diagram p16: schematic, sheet 17]
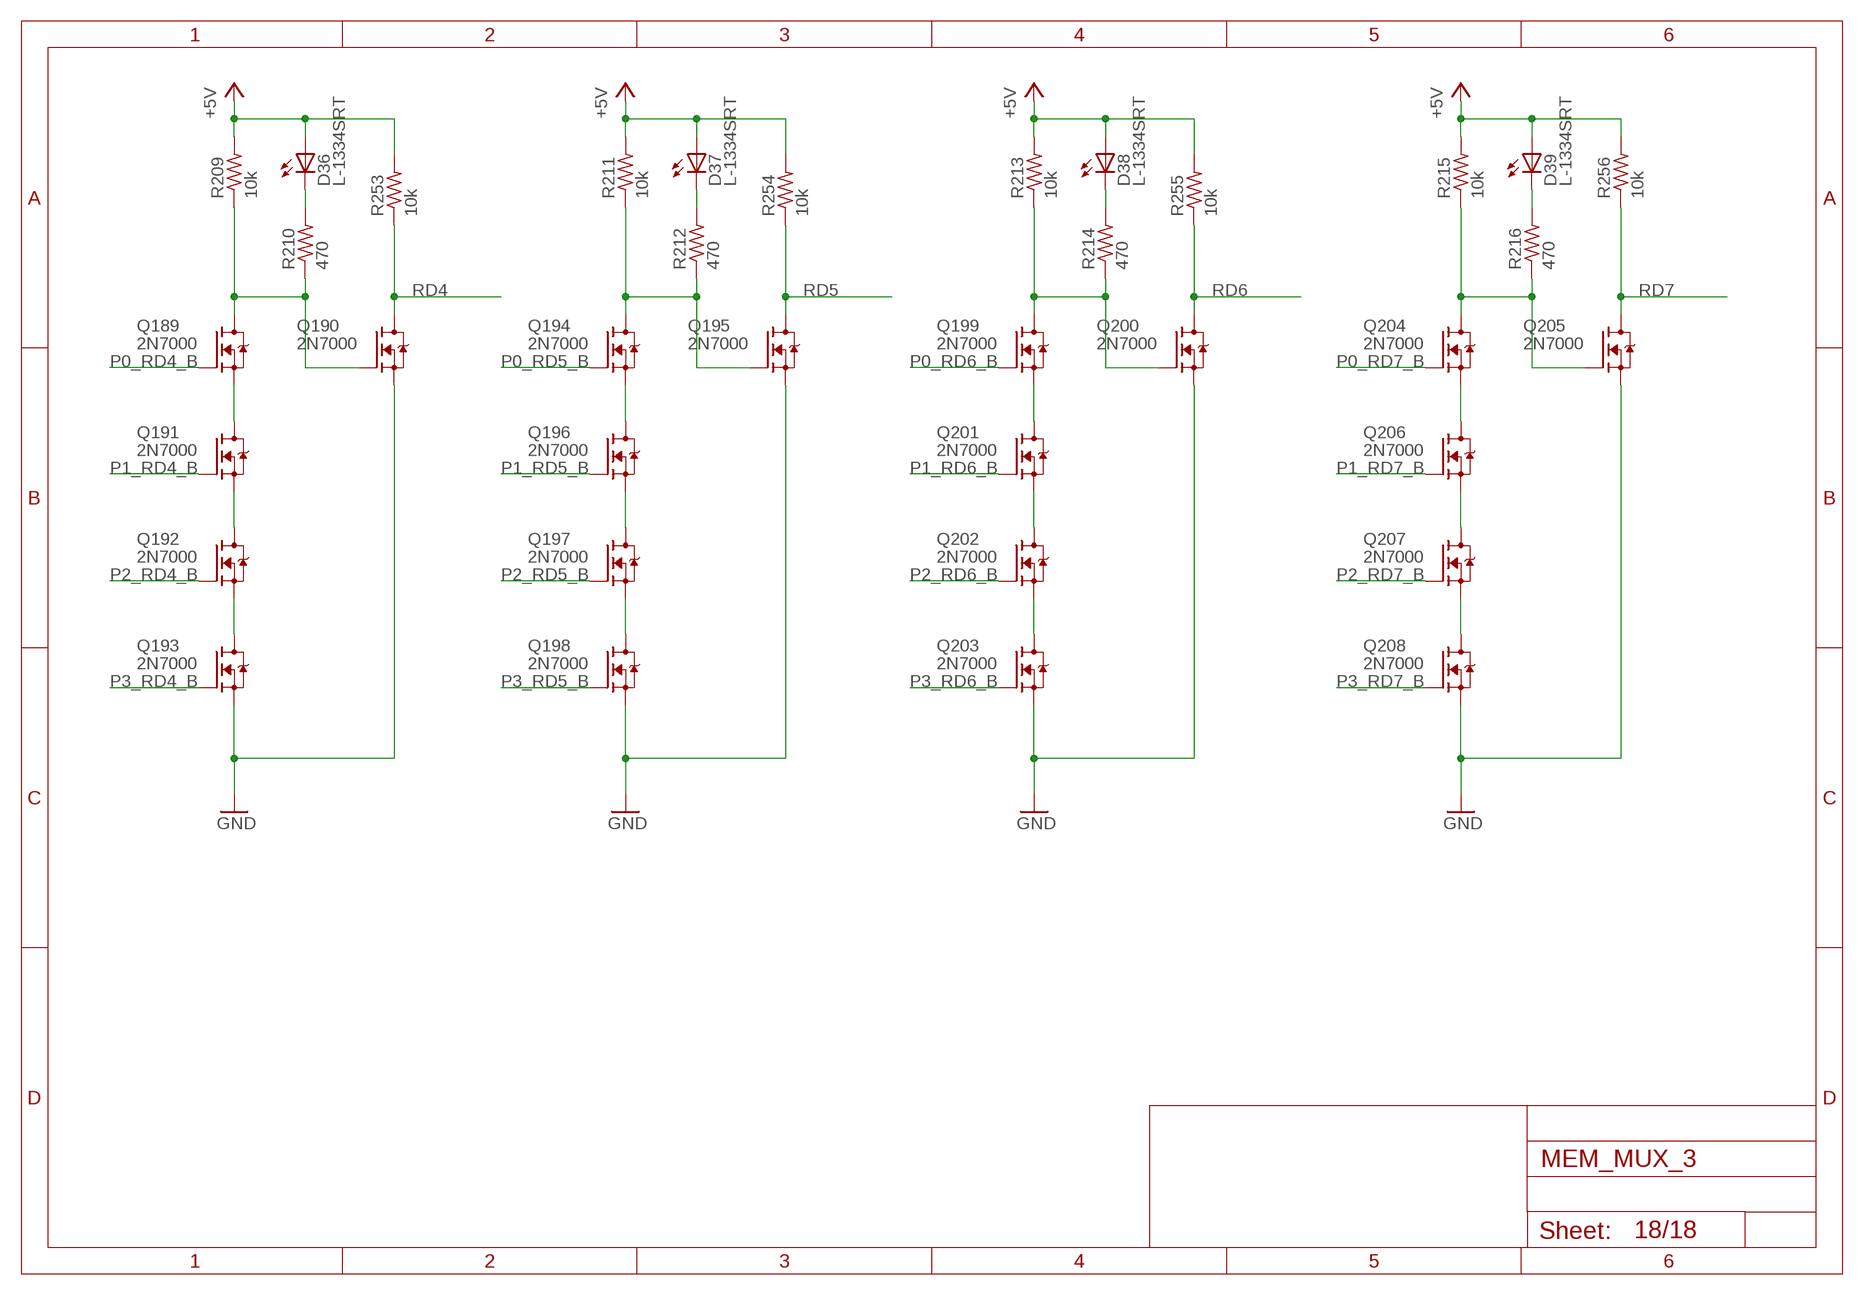
[diagram p17: schematic, sheet 18]

(export (version "E")
  (design (tool "Eeschema 10.0.6"))
  (components
    (comp (ref "J3")
      (value "20_HDR_LOCKING_RA")
      (footprint "eagle-import:20_HDR_LOCKING_RA")
      (libsource (lib "eagle-import") (part "20_HDR_LOCKING_RA"))
    )
    (comp (ref "J4")
      (value "20_HDR_LOCKING_RA")
      (footprint "eagle-import:20_HDR_LOCKING_RA")
      (libsource (lib "eagle-import") (part "20_HDR_LOCKING_RA"))
    )
    (comp (ref "Q59")
      (value "2N7000")
      (footprint "eagle-import:TO92-DGS")
      (libsource (lib "eagle-import") (part "2N7000"))
    )
    (comp (ref "Q60")
      (value "2N7000")
      (footprint "eagle-import:TO92-DGS")
      (libsource (lib "eagle-import") (part "2N7000"))
    )
    (comp (ref "R75")
      (value "10k")
      (footprint "eagle-import:R_P2INCH")
      (libsource (lib "eagle-import") (part "R_P2INCH"))
    )
    (comp (ref "R76")
      (value "10k")
      (footprint "eagle-import:R_P2INCH")
      (libsource (lib "eagle-import") (part "R_P2INCH"))
    )
    (comp (ref "D25")
      (value "L-1334SRT")
      (footprint "eagle-import:LED3MM")
      (libsource (lib "eagle-import") (part "L-1334SRT"))
    )
    (comp (ref "D26")
      (value "L-1334SRT")
      (footprint "eagle-import:LED3MM")
      (libsource (lib "eagle-import") (part "L-1334SRT"))
    )
    (comp (ref "D27")
      (value "L-1334SRT")
      (footprint "eagle-import:LED3MM")
      (libsource (lib "eagle-import") (part "L-1334SRT"))
    )
    (comp (ref "D28")
      (value "L-1334SRT")
      (footprint "eagle-import:LED3MM")
      (libsource (lib "eagle-import") (part "L-1334SRT"))
    )
    (comp (ref "D29")
      (value "L-1334SRT")
      (footprint "eagle-import:LED3MM")
      (libsource (lib "eagle-import") (part "L-1334SRT"))
    )
    (comp (ref "D30")
      (value "L-1334SRT")
      (footprint "eagle-import:LED3MM")
      (libsource (lib "eagle-import") (part "L-1334SRT"))
    )
    (comp (ref "D31")
      (value "L-1334SRT")
      (footprint "eagle-import:LED3MM")
      (libsource (lib "eagle-import") (part "L-1334SRT"))
    )
    (comp (ref "D32")
      (value "L-1334SRT")
      (footprint "eagle-import:LED3MM")
      (libsource (lib "eagle-import") (part "L-1334SRT"))
    )
    (comp (ref "Q127")
      (value "2N7000")
      (footprint "eagle-import:TO92-DGS")
      (libsource (lib "eagle-import") (part "2N7000"))
    )
    (comp (ref "Q128")
      (value "2N7000")
      (footprint "eagle-import:TO92-DGS")
      (libsource (lib "eagle-import") (part "2N7000"))
    )
    (comp (ref "Q129")
      (value "2N7000")
      (footprint "eagle-import:TO92-DGS")
      (libsource (lib "eagle-import") (part "2N7000"))
    )
    (comp (ref "Q130")
      (value "2N7000")
      (footprint "eagle-import:TO92-DGS")
      (libsource (lib "eagle-import") (part "2N7000"))
    )
    (comp (ref "Q131")
      (value "2N7000")
      (footprint "eagle-import:TO92-DGS")
      (libsource (lib "eagle-import") (part "2N7000"))
    )
    (comp (ref "Q132")
      (value "2N7000")
      (footprint "eagle-import:TO92-DGS")
      (libsource (lib "eagle-import") (part "2N7000"))
    )
    (comp (ref "Q133")
      (value "2N7000")
      (footprint "eagle-import:TO92-DGS")
      (libsource (lib "eagle-import") (part "2N7000"))
    )
    (comp (ref "Q134")
      (value "2N7000")
      (footprint "eagle-import:TO92-DGS")
      (libsource (lib "eagle-import") (part "2N7000"))
    )
    (comp (ref "Q135")
      (value "2N7000")
      (footprint "eagle-import:TO92-DGS")
      (libsource (lib "eagle-import") (part "2N7000"))
    )
    (comp (ref "Q136")
      (value "2N7000")
      (footprint "eagle-import:TO92-DGS")
      (libsource (lib "eagle-import") (part "2N7000"))
    )
    (comp (ref "Q137")
      (value "2N7000")
      (footprint "eagle-import:TO92-DGS")
      (libsource (lib "eagle-import") (part "2N7000"))
    )
    (comp (ref "Q138")
      (value "2N7000")
      (footprint "eagle-import:TO92-DGS")
      (libsource (lib "eagle-import") (part "2N7000"))
    )
    (comp (ref "Q139")
      (value "2N7000")
      (footprint "eagle-import:TO92-DGS")
      (libsource (lib "eagle-import") (part "2N7000"))
    )
    (comp (ref "Q140")
      (value "2N7000")
      (footprint "eagle-import:TO92-DGS")
      (libsource (lib "eagle-import") (part "2N7000"))
    )
    (comp (ref "Q141")
      (value "2N7000")
      (footprint "eagle-import:TO92-DGS")
      (libsource (lib "eagle-import") (part "2N7000"))
    )
    (comp (ref "Q142")
      (value "2N7000")
      (footprint "eagle-import:TO92-DGS")
      (libsource (lib "eagle-import") (part "2N7000"))
    )
    (comp (ref "R151")
      (value "10k")
      (footprint "eagle-import:R_P2INCH")
      (libsource (lib "eagle-import") (part "R_P2INCH"))
    )
    (comp (ref "R152")
      (value "470")
      (footprint "eagle-import:R_P2INCH")
      (libsource (lib "eagle-import") (part "R_P2INCH"))
    )
    (comp (ref "R153")
      (value "10k")
      (footprint "eagle-import:R_P2INCH")
      (libsource (lib "eagle-import") (part "R_P2INCH"))
    )
    (comp (ref "R154")
      (value "470")
      (footprint "eagle-import:R_P2INCH")
      (libsource (lib "eagle-import") (part "R_P2INCH"))
    )
    (comp (ref "R155")
      (value "10k")
      (footprint "eagle-import:R_P2INCH")
      (libsource (lib "eagle-import") (part "R_P2INCH"))
    )
    (comp (ref "R156")
      (value "470")
      (footprint "eagle-import:R_P2INCH")
      (libsource (lib "eagle-import") (part "R_P2INCH"))
    )
    (comp (ref "R157")
      (value "10k")
      (footprint "eagle-import:R_P2INCH")
      (libsource (lib "eagle-import") (part "R_P2INCH"))
    )
    (comp (ref "R158")
      (value "470")
      (footprint "eagle-import:R_P2INCH")
      (libsource (lib "eagle-import") (part "R_P2INCH"))
    )
    (comp (ref "R159")
      (value "10k")
      (footprint "eagle-import:R_P2INCH")
      (libsource (lib "eagle-import") (part "R_P2INCH"))
    )
    (comp (ref "R160")
      (value "470")
      (footprint "eagle-import:R_P2INCH")
      (libsource (lib "eagle-import") (part "R_P2INCH"))
    )
    (comp (ref "R161")
      (value "10k")
      (footprint "eagle-import:R_P2INCH")
      (libsource (lib "eagle-import") (part "R_P2INCH"))
    )
    (comp (ref "R162")
      (value "470")
      (footprint "eagle-import:R_P2INCH")
      (libsource (lib "eagle-import") (part "R_P2INCH"))
    )
    (comp (ref "R163")
      (value "10k")
      (footprint "eagle-import:R_P2INCH")
      (libsource (lib "eagle-import") (part "R_P2INCH"))
    )
    (comp (ref "R164")
      (value "470")
      (footprint "eagle-import:R_P2INCH")
      (libsource (lib "eagle-import") (part "R_P2INCH"))
    )
    (comp (ref "R165")
      (value "10k")
      (footprint "eagle-import:R_P2INCH")
      (libsource (lib "eagle-import") (part "R_P2INCH"))
    )
    (comp (ref "R166")
      (value "470")
      (footprint "eagle-import:R_P2INCH")
      (libsource (lib "eagle-import") (part "R_P2INCH"))
    )
    (comp (ref "R167")
      (value "10k")
      (footprint "eagle-import:R_P2INCH")
      (libsource (lib "eagle-import") (part "R_P2INCH"))
    )
    (comp (ref "R168")
      (value "10k")
      (footprint "eagle-import:R_P2INCH")
      (libsource (lib "eagle-import") (part "R_P2INCH"))
    )
    (comp (ref "R169")
      (value "10k")
      (footprint "eagle-import:R_P2INCH")
      (libsource (lib "eagle-import") (part "R_P2INCH"))
    )
    (comp (ref "R170")
      (value "10k")
      (footprint "eagle-import:R_P2INCH")
      (libsource (lib "eagle-import") (part "R_P2INCH"))
    )
    (comp (ref "R171")
      (value "10k")
      (footprint "eagle-import:R_P2INCH")
      (libsource (lib "eagle-import") (part "R_P2INCH"))
    )
    (comp (ref "R172")
      (value "10k")
      (footprint "eagle-import:R_P2INCH")
      (libsource (lib "eagle-import") (part "R_P2INCH"))
    )
    (comp (ref "R173")
      (value "10k")
      (footprint "eagle-import:R_P2INCH")
      (libsource (lib "eagle-import") (part "R_P2INCH"))
    )
    (comp (ref "R174")
      (value "10k")
      (footprint "eagle-import:R_P2INCH")
      (libsource (lib "eagle-import") (part "R_P2INCH"))
    )
    (comp (ref "Q145")
      (value "2N7000")
      (footprint "eagle-import:TO92-DGS")
      (libsource (lib "eagle-import") (part "2N7000"))
    )
    (comp (ref "Q146")
      (value "2N7000")
      (footprint "eagle-import:TO92-DGS")
      (libsource (lib "eagle-import") (part "2N7000"))
    )
    (comp (ref "Q147")
      (value "2N7000")
      (footprint "eagle-import:TO92-DGS")
      (libsource (lib "eagle-import") (part "2N7000"))
    )
    (comp (ref "Q148")
      (value "2N7000")
      (footprint "eagle-import:TO92-DGS")
      (libsource (lib "eagle-import") (part "2N7000"))
    )
    (comp (ref "Q149")
      (value "2N7000")
      (footprint "eagle-import:TO92-DGS")
      (libsource (lib "eagle-import") (part "2N7000"))
    )
    (comp (ref "Q150")
      (value "2N7000")
      (footprint "eagle-import:TO92-DGS")
      (libsource (lib "eagle-import") (part "2N7000"))
    )
    (comp (ref "Q151")
      (value "2N7000")
      (footprint "eagle-import:TO92-DGS")
      (libsource (lib "eagle-import") (part "2N7000"))
    )
    (comp (ref "Q152")
      (value "2N7000")
      (footprint "eagle-import:TO92-DGS")
      (libsource (lib "eagle-import") (part "2N7000"))
    )
    (comp (ref "Q153")
      (value "2N7000")
      (footprint "eagle-import:TO92-DGS")
      (libsource (lib "eagle-import") (part "2N7000"))
    )
    (comp (ref "Q154")
      (value "2N7000")
      (footprint "eagle-import:TO92-DGS")
      (libsource (lib "eagle-import") (part "2N7000"))
    )
    (comp (ref "Q155")
      (value "2N7000")
      (footprint "eagle-import:TO92-DGS")
      (libsource (lib "eagle-import") (part "2N7000"))
    )
    (comp (ref "Q156")
      (value "2N7000")
      (footprint "eagle-import:TO92-DGS")
      (libsource (lib "eagle-import") (part "2N7000"))
    )
    (comp (ref "Q157")
      (value "2N7000")
      (footprint "eagle-import:TO92-DGS")
      (libsource (lib "eagle-import") (part "2N7000"))
    )
    (comp (ref "Q158")
      (value "2N7000")
      (footprint "eagle-import:TO92-DGS")
      (libsource (lib "eagle-import") (part "2N7000"))
    )
    (comp (ref "Q159")
      (value "2N7000")
      (footprint "eagle-import:TO92-DGS")
      (libsource (lib "eagle-import") (part "2N7000"))
    )
    (comp (ref "Q160")
      (value "2N7000")
      (footprint "eagle-import:TO92-DGS")
      (libsource (lib "eagle-import") (part "2N7000"))
    )
    (comp (ref "Q161")
      (value "2N7000")
      (footprint "eagle-import:TO92-DGS")
      (libsource (lib "eagle-import") (part "2N7000"))
    )
    (comp (ref "Q162")
      (value "2N7000")
      (footprint "eagle-import:TO92-DGS")
      (libsource (lib "eagle-import") (part "2N7000"))
    )
    (comp (ref "Q163")
      (value "2N7000")
      (footprint "eagle-import:TO92-DGS")
      (libsource (lib "eagle-import") (part "2N7000"))
    )
    (comp (ref "Q164")
      (value "2N7000")
      (footprint "eagle-import:TO92-DGS")
      (libsource (lib "eagle-import") (part "2N7000"))
    )
    (comp (ref "Q165")
      (value "2N7000")
      (footprint "eagle-import:TO92-DGS")
      (libsource (lib "eagle-import") (part "2N7000"))
    )
    (comp (ref "Q166")
      (value "2N7000")
      (footprint "eagle-import:TO92-DGS")
      (libsource (lib "eagle-import") (part "2N7000"))
    )
    (comp (ref "Q167")
      (value "2N7000")
      (footprint "eagle-import:TO92-DGS")
      (libsource (lib "eagle-import") (part "2N7000"))
    )
    (comp (ref "Q168")
      (value "2N7000")
      (footprint "eagle-import:TO92-DGS")
      (libsource (lib "eagle-import") (part "2N7000"))
    )
    (comp (ref "R177")
      (value "10k")
      (footprint "eagle-import:R_P2INCH")
      (libsource (lib "eagle-import") (part "R_P2INCH"))
    )
    (comp (ref "R178")
      (value "10k")
      (footprint "eagle-import:R_P2INCH")
      (libsource (lib "eagle-import") (part "R_P2INCH"))
    )
    (comp (ref "R179")
      (value "10k")
      (footprint "eagle-import:R_P2INCH")
      (libsource (lib "eagle-import") (part "R_P2INCH"))
    )
    (comp (ref "R180")
      (value "10k")
      (footprint "eagle-import:R_P2INCH")
      (libsource (lib "eagle-import") (part "R_P2INCH"))
    )
    (comp (ref "R181")
      (value "10k")
      (footprint "eagle-import:R_P2INCH")
      (libsource (lib "eagle-import") (part "R_P2INCH"))
    )
    (comp (ref "R182")
      (value "10k")
      (footprint "eagle-import:R_P2INCH")
      (libsource (lib "eagle-import") (part "R_P2INCH"))
    )
    (comp (ref "R183")
      (value "10k")
      (footprint "eagle-import:R_P2INCH")
      (libsource (lib "eagle-import") (part "R_P2INCH"))
    )
    (comp (ref "R184")
      (value "10k")
      (footprint "eagle-import:R_P2INCH")
      (libsource (lib "eagle-import") (part "R_P2INCH"))
    )
    (comp (ref "R185")
      (value "10k")
      (footprint "eagle-import:R_P2INCH")
      (libsource (lib "eagle-import") (part "R_P2INCH"))
    )
    (comp (ref "R186")
      (value "10k")
      (footprint "eagle-import:R_P2INCH")
      (libsource (lib "eagle-import") (part "R_P2INCH"))
    )
    (comp (ref "R187")
      (value "10k")
      (footprint "eagle-import:R_P2INCH")
      (libsource (lib "eagle-import") (part "R_P2INCH"))
    )
    (comp (ref "R188")
      (value "10k")
      (footprint "eagle-import:R_P2INCH")
      (libsource (lib "eagle-import") (part "R_P2INCH"))
    )
    (comp (ref "R189")
      (value "10k")
      (footprint "eagle-import:R_P2INCH")
      (libsource (lib "eagle-import") (part "R_P2INCH"))
    )
    (comp (ref "R190")
      (value "10k")
      (footprint "eagle-import:R_P2INCH")
      (libsource (lib "eagle-import") (part "R_P2INCH"))
    )
    (comp (ref "R191")
      (value "10k")
      (footprint "eagle-import:R_P2INCH")
      (libsource (lib "eagle-import") (part "R_P2INCH"))
    )
    (comp (ref "R192")
      (value "10k")
      (footprint "eagle-import:R_P2INCH")
      (libsource (lib "eagle-import") (part "R_P2INCH"))
    )
    (comp (ref "R193")
      (value "10k")
      (footprint "eagle-import:R_P2INCH")
      (libsource (lib "eagle-import") (part "R_P2INCH"))
    )
    (comp (ref "R194")
      (value "10k")
      (footprint "eagle-import:R_P2INCH")
      (libsource (lib "eagle-import") (part "R_P2INCH"))
    )
    (comp (ref "R195")
      (value "10k")
      (footprint "eagle-import:R_P2INCH")
      (libsource (lib "eagle-import") (part "R_P2INCH"))
    )
    (comp (ref "R196")
      (value "10k")
      (footprint "eagle-import:R_P2INCH")
      (libsource (lib "eagle-import") (part "R_P2INCH"))
    )
    (comp (ref "R197")
      (value "10k")
      (footprint "eagle-import:R_P2INCH")
      (libsource (lib "eagle-import") (part "R_P2INCH"))
    )
    (comp (ref "R198")
      (value "10k")
      (footprint "eagle-import:R_P2INCH")
      (libsource (lib "eagle-import") (part "R_P2INCH"))
    )
    (comp (ref "R199")
      (value "10k")
      (footprint "eagle-import:R_P2INCH")
      (libsource (lib "eagle-import") (part "R_P2INCH"))
    )
    (comp (ref "R200")
      (value "10k")
      (footprint "eagle-import:R_P2INCH")
      (libsource (lib "eagle-import") (part "R_P2INCH"))
    )
    (comp (ref "C1")
      (value "100n")
      (footprint "eagle-import:CAP_P2INCH")
      (libsource (lib "eagle-import") (part "C_P2INCH"))
    )
    (comp (ref "C2")
      (value "100n")
      (footprint "eagle-import:CAP_P2INCH")
      (libsource (lib "eagle-import") (part "C_P2INCH"))
    )
    (comp (ref "C3")
      (value "100n")
      (footprint "eagle-import:CAP_P2INCH")
      (libsource (lib "eagle-import") (part "C_P2INCH"))
    )
    (comp (ref "C4")
      (value "100n")
      (footprint "eagle-import:CAP_P2INCH")
      (libsource (lib "eagle-import") (part "C_P2INCH"))
    )
    (comp (ref "C5")
      (value "100n")
      (footprint "eagle-import:CAP_P2INCH")
      (libsource (lib "eagle-import") (part "C_P2INCH"))
    )
    (comp (ref "C6")
      (value "100n")
      (footprint "eagle-import:CAP_P2INCH")
      (libsource (lib "eagle-import") (part "C_P2INCH"))
    )
    (comp (ref "C7")
      (value "100u")
      (footprint "eagle-import:POLARISED_CAP_2P5_6P3MM")
      (libsource (lib "eagle-import") (part "POLARISED_CAP_2P5_6P3MM"))
    )
    (comp (ref "C8")
      (value "100n")
      (footprint "eagle-import:CAP_P2INCH")
      (libsource (lib "eagle-import") (part "C_P2INCH"))
    )
    (comp (ref "H1")
      (value "3M_MOUNT_HOLE")
      (footprint "eagle-import:3M_HOLE")
      (libsource (lib "eagle-import") (part "3M_MOUNT_HOLE"))
    )
    (comp (ref "H2")
      (value "3M_MOUNT_HOLE")
      (footprint "eagle-import:3M_HOLE")
      (libsource (lib "eagle-import") (part "3M_MOUNT_HOLE"))
    )
    (comp (ref "H3")
      (value "3M_MOUNT_HOLE")
      (footprint "eagle-import:3M_HOLE")
      (libsource (lib "eagle-import") (part "3M_MOUNT_HOLE"))
    )
    (comp (ref "H4")
      (value "3M_MOUNT_HOLE")
      (footprint "eagle-import:3M_HOLE")
      (libsource (lib "eagle-import") (part "3M_MOUNT_HOLE"))
    )
    (comp (ref "H5")
      (value "3M_MOUNT_HOLE")
      (footprint "eagle-import:3M_HOLE")
      (libsource (lib "eagle-import") (part "3M_MOUNT_HOLE"))
    )
    (comp (ref "H6")
      (value "3M_MOUNT_HOLE")
      (footprint "eagle-import:3M_HOLE")
      (libsource (lib "eagle-import") (part "3M_MOUNT_HOLE"))
    )
    (comp (ref "H7")
      (value "3M_MOUNT_HOLE")
      (footprint "eagle-import:3M_HOLE")
      (libsource (lib "eagle-import") (part "3M_MOUNT_HOLE"))
    )
    (comp (ref "H8")
      (value "3M_MOUNT_HOLE")
      (footprint "eagle-import:3M_HOLE")
      (libsource (lib "eagle-import") (part "3M_MOUNT_HOLE"))
    )
    (comp (ref "H9")
      (value "3M_MOUNT_HOLE")
      (footprint "eagle-import:3M_HOLE")
      (libsource (lib "eagle-import") (part "3M_MOUNT_HOLE"))
    )
    (comp (ref "H10")
      (value "3M_MOUNT_HOLE")
      (footprint "eagle-import:3M_HOLE")
      (libsource (lib "eagle-import") (part "3M_MOUNT_HOLE"))
    )
    (comp (ref "TP5")
      (value "POWER_PAD")
      (footprint "eagle-import:POWER_PAD")
      (libsource (lib "eagle-import") (part "POWER_PAD"))
    )
    (comp (ref "TP6")
      (value "POWER_PAD")
      (footprint "eagle-import:POWER_PAD")
      (libsource (lib "eagle-import") (part "POWER_PAD"))
    )
    (comp (ref "Q61")
      (value "2N7000")
      (footprint "eagle-import:TO92-DGS")
      (libsource (lib "eagle-import") (part "2N7000"))
    )
    (comp (ref "Q62")
      (value "2N7000")
      (footprint "eagle-import:TO92-DGS")
      (libsource (lib "eagle-import") (part "2N7000"))
    )
    (comp (ref "Q63")
      (value "2N7000")
      (footprint "eagle-import:TO92-DGS")
      (libsource (lib "eagle-import") (part "2N7000"))
    )
    (comp (ref "Q64")
      (value "2N7000")
      (footprint "eagle-import:TO92-DGS")
      (libsource (lib "eagle-import") (part "2N7000"))
    )
    (comp (ref "Q65")
      (value "2N7000")
      (footprint "eagle-import:TO92-DGS")
      (libsource (lib "eagle-import") (part "2N7000"))
    )
    (comp (ref "Q66")
      (value "2N7000")
      (footprint "eagle-import:TO92-DGS")
      (libsource (lib "eagle-import") (part "2N7000"))
    )
    (comp (ref "Q67")
      (value "2N7000")
      (footprint "eagle-import:TO92-DGS")
      (libsource (lib "eagle-import") (part "2N7000"))
    )
    (comp (ref "Q68")
      (value "2N7000")
      (footprint "eagle-import:TO92-DGS")
      (libsource (lib "eagle-import") (part "2N7000"))
    )
    (comp (ref "Q69")
      (value "2N7000")
      (footprint "eagle-import:TO92-DGS")
      (libsource (lib "eagle-import") (part "2N7000"))
    )
    (comp (ref "Q70")
      (value "2N7000")
      (footprint "eagle-import:TO92-DGS")
      (libsource (lib "eagle-import") (part "2N7000"))
    )
    (comp (ref "Q71")
      (value "2N7000")
      (footprint "eagle-import:TO92-DGS")
      (libsource (lib "eagle-import") (part "2N7000"))
    )
    (comp (ref "Q72")
      (value "2N7000")
      (footprint "eagle-import:TO92-DGS")
      (libsource (lib "eagle-import") (part "2N7000"))
    )
    (comp (ref "Q73")
      (value "2N7000")
      (footprint "eagle-import:TO92-DGS")
      (libsource (lib "eagle-import") (part "2N7000"))
    )
    (comp (ref "Q74")
      (value "2N7000")
      (footprint "eagle-import:TO92-DGS")
      (libsource (lib "eagle-import") (part "2N7000"))
    )
    (comp (ref "Q75")
      (value "2N7000")
      (footprint "eagle-import:TO92-DGS")
      (libsource (lib "eagle-import") (part "2N7000"))
    )
    (comp (ref "Q76")
      (value "2N7000")
      (footprint "eagle-import:TO92-DGS")
      (libsource (lib "eagle-import") (part "2N7000"))
    )
    (comp (ref "Q77")
      (value "2N7000")
      (footprint "eagle-import:TO92-DGS")
      (libsource (lib "eagle-import") (part "2N7000"))
    )
    (comp (ref "Q78")
      (value "2N7000")
      (footprint "eagle-import:TO92-DGS")
      (libsource (lib "eagle-import") (part "2N7000"))
    )
    (comp (ref "Q79")
      (value "2N7000")
      (footprint "eagle-import:TO92-DGS")
      (libsource (lib "eagle-import") (part "2N7000"))
    )
    (comp (ref "Q80")
      (value "2N7000")
      (footprint "eagle-import:TO92-DGS")
      (libsource (lib "eagle-import") (part "2N7000"))
    )
    (comp (ref "Q81")
      (value "2N7000")
      (footprint "eagle-import:TO92-DGS")
      (libsource (lib "eagle-import") (part "2N7000"))
    )
    (comp (ref "Q82")
      (value "2N7000")
      (footprint "eagle-import:TO92-DGS")
      (libsource (lib "eagle-import") (part "2N7000"))
    )
    (comp (ref "Q83")
      (value "2N7000")
      (footprint "eagle-import:TO92-DGS")
      (libsource (lib "eagle-import") (part "2N7000"))
    )
    (comp (ref "Q84")
      (value "2N7000")
      (footprint "eagle-import:TO92-DGS")
      (libsource (lib "eagle-import") (part "2N7000"))
    )
    (comp (ref "R77")
      (value "10k")
      (footprint "eagle-import:R_P2INCH")
      (libsource (lib "eagle-import") (part "R_P2INCH"))
    )
    (comp (ref "R78")
      (value "10k")
      (footprint "eagle-import:R_P2INCH")
      (libsource (lib "eagle-import") (part "R_P2INCH"))
    )
    (comp (ref "R79")
      (value "10k")
      (footprint "eagle-import:R_P2INCH")
      (libsource (lib "eagle-import") (part "R_P2INCH"))
    )
    (comp (ref "R80")
      (value "10k")
      (footprint "eagle-import:R_P2INCH")
      (libsource (lib "eagle-import") (part "R_P2INCH"))
    )
    (comp (ref "R81")
      (value "10k")
      (footprint "eagle-import:R_P2INCH")
      (libsource (lib "eagle-import") (part "R_P2INCH"))
    )
    (comp (ref "R82")
      (value "10k")
      (footprint "eagle-import:R_P2INCH")
      (libsource (lib "eagle-import") (part "R_P2INCH"))
    )
    (comp (ref "R83")
      (value "10k")
      (footprint "eagle-import:R_P2INCH")
      (libsource (lib "eagle-import") (part "R_P2INCH"))
    )
    (comp (ref "R84")
      (value "10k")
      (footprint "eagle-import:R_P2INCH")
      (libsource (lib "eagle-import") (part "R_P2INCH"))
    )
    (comp (ref "R85")
      (value "10k")
      (footprint "eagle-import:R_P2INCH")
      (libsource (lib "eagle-import") (part "R_P2INCH"))
    )
    (comp (ref "R86")
      (value "10k")
      (footprint "eagle-import:R_P2INCH")
      (libsource (lib "eagle-import") (part "R_P2INCH"))
    )
    (comp (ref "R87")
      (value "10k")
      (footprint "eagle-import:R_P2INCH")
      (libsource (lib "eagle-import") (part "R_P2INCH"))
    )
    (comp (ref "R88")
      (value "10k")
      (footprint "eagle-import:R_P2INCH")
      (libsource (lib "eagle-import") (part "R_P2INCH"))
    )
    (comp (ref "R89")
      (value "10k")
      (footprint "eagle-import:R_P2INCH")
      (libsource (lib "eagle-import") (part "R_P2INCH"))
    )
    (comp (ref "R90")
      (value "10k")
      (footprint "eagle-import:R_P2INCH")
      (libsource (lib "eagle-import") (part "R_P2INCH"))
    )
    (comp (ref "R91")
      (value "10k")
      (footprint "eagle-import:R_P2INCH")
      (libsource (lib "eagle-import") (part "R_P2INCH"))
    )
    (comp (ref "R92")
      (value "10k")
      (footprint "eagle-import:R_P2INCH")
      (libsource (lib "eagle-import") (part "R_P2INCH"))
    )
    (comp (ref "R93")
      (value "10k")
      (footprint "eagle-import:R_P2INCH")
      (libsource (lib "eagle-import") (part "R_P2INCH"))
    )
    (comp (ref "R94")
      (value "10k")
      (footprint "eagle-import:R_P2INCH")
      (libsource (lib "eagle-import") (part "R_P2INCH"))
    )
    (comp (ref "R95")
      (value "10k")
      (footprint "eagle-import:R_P2INCH")
      (libsource (lib "eagle-import") (part "R_P2INCH"))
    )
    (comp (ref "R96")
      (value "10k")
      (footprint "eagle-import:R_P2INCH")
      (libsource (lib "eagle-import") (part "R_P2INCH"))
    )
    (comp (ref "R97")
      (value "10k")
      (footprint "eagle-import:R_P2INCH")
      (libsource (lib "eagle-import") (part "R_P2INCH"))
    )
    (comp (ref "R98")
      (value "10k")
      (footprint "eagle-import:R_P2INCH")
      (libsource (lib "eagle-import") (part "R_P2INCH"))
    )
    (comp (ref "R99")
      (value "10k")
      (footprint "eagle-import:R_P2INCH")
      (libsource (lib "eagle-import") (part "R_P2INCH"))
    )
    (comp (ref "R100")
      (value "10k")
      (footprint "eagle-import:R_P2INCH")
      (libsource (lib "eagle-import") (part "R_P2INCH"))
    )
    (comp (ref "Q209")
      (value "2N7000")
      (footprint "eagle-import:TO92-DGS")
      (libsource (lib "eagle-import") (part "2N7000"))
    )
    (comp (ref "Q210")
      (value "2N7000")
      (footprint "eagle-import:TO92-DGS")
      (libsource (lib "eagle-import") (part "2N7000"))
    )
    (comp (ref "Q211")
      (value "2N7000")
      (footprint "eagle-import:TO92-DGS")
      (libsource (lib "eagle-import") (part "2N7000"))
    )
    (comp (ref "Q212")
      (value "2N7000")
      (footprint "eagle-import:TO92-DGS")
      (libsource (lib "eagle-import") (part "2N7000"))
    )
    (comp (ref "Q213")
      (value "2N7000")
      (footprint "eagle-import:TO92-DGS")
      (libsource (lib "eagle-import") (part "2N7000"))
    )
    (comp (ref "Q214")
      (value "2N7000")
      (footprint "eagle-import:TO92-DGS")
      (libsource (lib "eagle-import") (part "2N7000"))
    )
    (comp (ref "Q215")
      (value "2N7000")
      (footprint "eagle-import:TO92-DGS")
      (libsource (lib "eagle-import") (part "2N7000"))
    )
    (comp (ref "Q216")
      (value "2N7000")
      (footprint "eagle-import:TO92-DGS")
      (libsource (lib "eagle-import") (part "2N7000"))
    )
    (comp (ref "Q217")
      (value "2N7000")
      (footprint "eagle-import:TO92-DGS")
      (libsource (lib "eagle-import") (part "2N7000"))
    )
    (comp (ref "Q218")
      (value "2N7000")
      (footprint "eagle-import:TO92-DGS")
      (libsource (lib "eagle-import") (part "2N7000"))
    )
    (comp (ref "Q219")
      (value "2N7000")
      (footprint "eagle-import:TO92-DGS")
      (libsource (lib "eagle-import") (part "2N7000"))
    )
    (comp (ref "Q220")
      (value "2N7000")
      (footprint "eagle-import:TO92-DGS")
      (libsource (lib "eagle-import") (part "2N7000"))
    )
    (comp (ref "Q221")
      (value "2N7000")
      (footprint "eagle-import:TO92-DGS")
      (libsource (lib "eagle-import") (part "2N7000"))
    )
    (comp (ref "Q222")
      (value "2N7000")
      (footprint "eagle-import:TO92-DGS")
      (libsource (lib "eagle-import") (part "2N7000"))
    )
    (comp (ref "Q223")
      (value "2N7000")
      (footprint "eagle-import:TO92-DGS")
      (libsource (lib "eagle-import") (part "2N7000"))
    )
    (comp (ref "Q224")
      (value "2N7000")
      (footprint "eagle-import:TO92-DGS")
      (libsource (lib "eagle-import") (part "2N7000"))
    )
    (comp (ref "Q225")
      (value "2N7000")
      (footprint "eagle-import:TO92-DGS")
      (libsource (lib "eagle-import") (part "2N7000"))
    )
    (comp (ref "Q226")
      (value "2N7000")
      (footprint "eagle-import:TO92-DGS")
      (libsource (lib "eagle-import") (part "2N7000"))
    )
    (comp (ref "Q227")
      (value "2N7000")
      (footprint "eagle-import:TO92-DGS")
      (libsource (lib "eagle-import") (part "2N7000"))
    )
    (comp (ref "Q228")
      (value "2N7000")
      (footprint "eagle-import:TO92-DGS")
      (libsource (lib "eagle-import") (part "2N7000"))
    )
    (comp (ref "Q229")
      (value "2N7000")
      (footprint "eagle-import:TO92-DGS")
      (libsource (lib "eagle-import") (part "2N7000"))
    )
    (comp (ref "Q230")
      (value "2N7000")
      (footprint "eagle-import:TO92-DGS")
      (libsource (lib "eagle-import") (part "2N7000"))
    )
    (comp (ref "Q231")
      (value "2N7000")
      (footprint "eagle-import:TO92-DGS")
      (libsource (lib "eagle-import") (part "2N7000"))
    )
    (comp (ref "Q232")
      (value "2N7000")
      (footprint "eagle-import:TO92-DGS")
      (libsource (lib "eagle-import") (part "2N7000"))
    )
    (comp (ref "R217")
      (value "10k")
      (footprint "eagle-import:R_P2INCH")
      (libsource (lib "eagle-import") (part "R_P2INCH"))
    )
    (comp (ref "R218")
      (value "10k")
      (footprint "eagle-import:R_P2INCH")
      (libsource (lib "eagle-import") (part "R_P2INCH"))
    )
    (comp (ref "R219")
      (value "10k")
      (footprint "eagle-import:R_P2INCH")
      (libsource (lib "eagle-import") (part "R_P2INCH"))
    )
    (comp (ref "R220")
      (value "10k")
      (footprint "eagle-import:R_P2INCH")
      (libsource (lib "eagle-import") (part "R_P2INCH"))
    )
    (comp (ref "R221")
      (value "10k")
      (footprint "eagle-import:R_P2INCH")
      (libsource (lib "eagle-import") (part "R_P2INCH"))
    )
    (comp (ref "R222")
      (value "10k")
      (footprint "eagle-import:R_P2INCH")
      (libsource (lib "eagle-import") (part "R_P2INCH"))
    )
    (comp (ref "R223")
      (value "10k")
      (footprint "eagle-import:R_P2INCH")
      (libsource (lib "eagle-import") (part "R_P2INCH"))
    )
    (comp (ref "R224")
      (value "10k")
      (footprint "eagle-import:R_P2INCH")
      (libsource (lib "eagle-import") (part "R_P2INCH"))
    )
    (comp (ref "R225")
      (value "10k")
      (footprint "eagle-import:R_P2INCH")
      (libsource (lib "eagle-import") (part "R_P2INCH"))
    )
    (comp (ref "R226")
      (value "10k")
      (footprint "eagle-import:R_P2INCH")
      (libsource (lib "eagle-import") (part "R_P2INCH"))
    )
    (comp (ref "R227")
      (value "10k")
      (footprint "eagle-import:R_P2INCH")
      (libsource (lib "eagle-import") (part "R_P2INCH"))
    )
    (comp (ref "R228")
      (value "10k")
      (footprint "eagle-import:R_P2INCH")
      (libsource (lib "eagle-import") (part "R_P2INCH"))
    )
    (comp (ref "R229")
      (value "10k")
      (footprint "eagle-import:R_P2INCH")
      (libsource (lib "eagle-import") (part "R_P2INCH"))
    )
    (comp (ref "R230")
      (value "10k")
      (footprint "eagle-import:R_P2INCH")
      (libsource (lib "eagle-import") (part "R_P2INCH"))
    )
    (comp (ref "R231")
      (value "10k")
      (footprint "eagle-import:R_P2INCH")
      (libsource (lib "eagle-import") (part "R_P2INCH"))
    )
    (comp (ref "R232")
      (value "10k")
      (footprint "eagle-import:R_P2INCH")
      (libsource (lib "eagle-import") (part "R_P2INCH"))
    )
    (comp (ref "R233")
      (value "10k")
      (footprint "eagle-import:R_P2INCH")
      (libsource (lib "eagle-import") (part "R_P2INCH"))
    )
    (comp (ref "R234")
      (value "10k")
      (footprint "eagle-import:R_P2INCH")
      (libsource (lib "eagle-import") (part "R_P2INCH"))
    )
    (comp (ref "R235")
      (value "10k")
      (footprint "eagle-import:R_P2INCH")
      (libsource (lib "eagle-import") (part "R_P2INCH"))
    )
    (comp (ref "R236")
      (value "10k")
      (footprint "eagle-import:R_P2INCH")
      (libsource (lib "eagle-import") (part "R_P2INCH"))
    )
    (comp (ref "R237")
      (value "10k")
      (footprint "eagle-import:R_P2INCH")
      (libsource (lib "eagle-import") (part "R_P2INCH"))
    )
    (comp (ref "R238")
      (value "10k")
      (footprint "eagle-import:R_P2INCH")
      (libsource (lib "eagle-import") (part "R_P2INCH"))
    )
    (comp (ref "R239")
      (value "10k")
      (footprint "eagle-import:R_P2INCH")
      (libsource (lib "eagle-import") (part "R_P2INCH"))
    )
    (comp (ref "R240")
      (value "10k")
      (footprint "eagle-import:R_P2INCH")
      (libsource (lib "eagle-import") (part "R_P2INCH"))
    )
    (comp (ref "Q103")
      (value "2N7000")
      (footprint "eagle-import:TO92-DGS")
      (libsource (lib "eagle-import") (part "2N7000"))
    )
    (comp (ref "Q104")
      (value "2N7000")
      (footprint "eagle-import:TO92-DGS")
      (libsource (lib "eagle-import") (part "2N7000"))
    )
    (comp (ref "Q105")
      (value "2N7000")
      (footprint "eagle-import:TO92-DGS")
      (libsource (lib "eagle-import") (part "2N7000"))
    )
    (comp (ref "Q106")
      (value "2N7000")
      (footprint "eagle-import:TO92-DGS")
      (libsource (lib "eagle-import") (part "2N7000"))
    )
    (comp (ref "Q107")
      (value "2N7000")
      (footprint "eagle-import:TO92-DGS")
      (libsource (lib "eagle-import") (part "2N7000"))
    )
    (comp (ref "Q108")
      (value "2N7000")
      (footprint "eagle-import:TO92-DGS")
      (libsource (lib "eagle-import") (part "2N7000"))
    )
    (comp (ref "Q109")
      (value "2N7000")
      (footprint "eagle-import:TO92-DGS")
      (libsource (lib "eagle-import") (part "2N7000"))
    )
    (comp (ref "Q110")
      (value "2N7000")
      (footprint "eagle-import:TO92-DGS")
      (libsource (lib "eagle-import") (part "2N7000"))
    )
    (comp (ref "Q111")
      (value "2N7000")
      (footprint "eagle-import:TO92-DGS")
      (libsource (lib "eagle-import") (part "2N7000"))
    )
    (comp (ref "Q112")
      (value "2N7000")
      (footprint "eagle-import:TO92-DGS")
      (libsource (lib "eagle-import") (part "2N7000"))
    )
    (comp (ref "Q113")
      (value "2N7000")
      (footprint "eagle-import:TO92-DGS")
      (libsource (lib "eagle-import") (part "2N7000"))
    )
    (comp (ref "Q114")
      (value "2N7000")
      (footprint "eagle-import:TO92-DGS")
      (libsource (lib "eagle-import") (part "2N7000"))
    )
    (comp (ref "Q115")
      (value "2N7000")
      (footprint "eagle-import:TO92-DGS")
      (libsource (lib "eagle-import") (part "2N7000"))
    )
    (comp (ref "Q116")
      (value "2N7000")
      (footprint "eagle-import:TO92-DGS")
      (libsource (lib "eagle-import") (part "2N7000"))
    )
    (comp (ref "Q117")
      (value "2N7000")
      (footprint "eagle-import:TO92-DGS")
      (libsource (lib "eagle-import") (part "2N7000"))
    )
    (comp (ref "Q118")
      (value "2N7000")
      (footprint "eagle-import:TO92-DGS")
      (libsource (lib "eagle-import") (part "2N7000"))
    )
    (comp (ref "Q119")
      (value "2N7000")
      (footprint "eagle-import:TO92-DGS")
      (libsource (lib "eagle-import") (part "2N7000"))
    )
    (comp (ref "Q120")
      (value "2N7000")
      (footprint "eagle-import:TO92-DGS")
      (libsource (lib "eagle-import") (part "2N7000"))
    )
    (comp (ref "Q121")
      (value "2N7000")
      (footprint "eagle-import:TO92-DGS")
      (libsource (lib "eagle-import") (part "2N7000"))
    )
    (comp (ref "Q122")
      (value "2N7000")
      (footprint "eagle-import:TO92-DGS")
      (libsource (lib "eagle-import") (part "2N7000"))
    )
    (comp (ref "Q123")
      (value "2N7000")
      (footprint "eagle-import:TO92-DGS")
      (libsource (lib "eagle-import") (part "2N7000"))
    )
    (comp (ref "Q124")
      (value "2N7000")
      (footprint "eagle-import:TO92-DGS")
      (libsource (lib "eagle-import") (part "2N7000"))
    )
    (comp (ref "Q125")
      (value "2N7000")
      (footprint "eagle-import:TO92-DGS")
      (libsource (lib "eagle-import") (part "2N7000"))
    )
    (comp (ref "Q126")
      (value "2N7000")
      (footprint "eagle-import:TO92-DGS")
      (libsource (lib "eagle-import") (part "2N7000"))
    )
    (comp (ref "R127")
      (value "10k")
      (footprint "eagle-import:R_P2INCH")
      (libsource (lib "eagle-import") (part "R_P2INCH"))
    )
    (comp (ref "R128")
      (value "10k")
      (footprint "eagle-import:R_P2INCH")
      (libsource (lib "eagle-import") (part "R_P2INCH"))
    )
    (comp (ref "R129")
      (value "10k")
      (footprint "eagle-import:R_P2INCH")
      (libsource (lib "eagle-import") (part "R_P2INCH"))
    )
    (comp (ref "R130")
      (value "10k")
      (footprint "eagle-import:R_P2INCH")
      (libsource (lib "eagle-import") (part "R_P2INCH"))
    )
    (comp (ref "R131")
      (value "10k")
      (footprint "eagle-import:R_P2INCH")
      (libsource (lib "eagle-import") (part "R_P2INCH"))
    )
    (comp (ref "R132")
      (value "10k")
      (footprint "eagle-import:R_P2INCH")
      (libsource (lib "eagle-import") (part "R_P2INCH"))
    )
    (comp (ref "R133")
      (value "10k")
      (footprint "eagle-import:R_P2INCH")
      (libsource (lib "eagle-import") (part "R_P2INCH"))
    )
    (comp (ref "R134")
      (value "10k")
      (footprint "eagle-import:R_P2INCH")
      (libsource (lib "eagle-import") (part "R_P2INCH"))
    )
    (comp (ref "R135")
      (value "10k")
      (footprint "eagle-import:R_P2INCH")
      (libsource (lib "eagle-import") (part "R_P2INCH"))
    )
    (comp (ref "R136")
      (value "10k")
      (footprint "eagle-import:R_P2INCH")
      (libsource (lib "eagle-import") (part "R_P2INCH"))
    )
    (comp (ref "R137")
      (value "10k")
      (footprint "eagle-import:R_P2INCH")
      (libsource (lib "eagle-import") (part "R_P2INCH"))
    )
    (comp (ref "R138")
      (value "10k")
      (footprint "eagle-import:R_P2INCH")
      (libsource (lib "eagle-import") (part "R_P2INCH"))
    )
    (comp (ref "R139")
      (value "10k")
      (footprint "eagle-import:R_P2INCH")
      (libsource (lib "eagle-import") (part "R_P2INCH"))
    )
    (comp (ref "R140")
      (value "10k")
      (footprint "eagle-import:R_P2INCH")
      (libsource (lib "eagle-import") (part "R_P2INCH"))
    )
    (comp (ref "R141")
      (value "10k")
      (footprint "eagle-import:R_P2INCH")
      (libsource (lib "eagle-import") (part "R_P2INCH"))
    )
    (comp (ref "R142")
      (value "10k")
      (footprint "eagle-import:R_P2INCH")
      (libsource (lib "eagle-import") (part "R_P2INCH"))
    )
    (comp (ref "R143")
      (value "10k")
      (footprint "eagle-import:R_P2INCH")
      (libsource (lib "eagle-import") (part "R_P2INCH"))
    )
    (comp (ref "R144")
      (value "10k")
      (footprint "eagle-import:R_P2INCH")
      (libsource (lib "eagle-import") (part "R_P2INCH"))
    )
    (comp (ref "R145")
      (value "10k")
      (footprint "eagle-import:R_P2INCH")
      (libsource (lib "eagle-import") (part "R_P2INCH"))
    )
    (comp (ref "R146")
      (value "10k")
      (footprint "eagle-import:R_P2INCH")
      (libsource (lib "eagle-import") (part "R_P2INCH"))
    )
    (comp (ref "R147")
      (value "10k")
      (footprint "eagle-import:R_P2INCH")
      (libsource (lib "eagle-import") (part "R_P2INCH"))
    )
    (comp (ref "R148")
      (value "10k")
      (footprint "eagle-import:R_P2INCH")
      (libsource (lib "eagle-import") (part "R_P2INCH"))
    )
    (comp (ref "R149")
      (value "10k")
      (footprint "eagle-import:R_P2INCH")
      (libsource (lib "eagle-import") (part "R_P2INCH"))
    )
    (comp (ref "R150")
      (value "10k")
      (footprint "eagle-import:R_P2INCH")
      (libsource (lib "eagle-import") (part "R_P2INCH"))
    )
    (comp (ref "J1")
      (value "20_HDR_LOCKING_RA")
      (footprint "eagle-import:20_HDR_LOCKING_RA")
      (libsource (lib "eagle-import") (part "20_HDR_LOCKING_RA"))
    )
    (comp (ref "J2")
      (value "20_HDR_LOCKING_RA")
      (footprint "eagle-import:20_HDR_LOCKING_RA")
      (libsource (lib "eagle-import") (part "20_HDR_LOCKING_RA"))
    )
    (comp (ref "Q23")
      (value "2N7000")
      (footprint "eagle-import:TO92-DGS")
      (libsource (lib "eagle-import") (part "2N7000"))
    )
    (comp (ref "Q24")
      (value "2N7000")
      (footprint "eagle-import:TO92-DGS")
      (libsource (lib "eagle-import") (part "2N7000"))
    )
    (comp (ref "R31")
      (value "10k")
      (footprint "eagle-import:R_P2INCH")
      (libsource (lib "eagle-import") (part "R_P2INCH"))
    )
    (comp (ref "R32")
      (value "10k")
      (footprint "eagle-import:R_P2INCH")
      (libsource (lib "eagle-import") (part "R_P2INCH"))
    )
    (comp (ref "D36")
      (value "L-1334SRT")
      (footprint "eagle-import:LED3MM")
      (libsource (lib "eagle-import") (part "L-1334SRT"))
    )
    (comp (ref "D37")
      (value "L-1334SRT")
      (footprint "eagle-import:LED3MM")
      (libsource (lib "eagle-import") (part "L-1334SRT"))
    )
    (comp (ref "D38")
      (value "L-1334SRT")
      (footprint "eagle-import:LED3MM")
      (libsource (lib "eagle-import") (part "L-1334SRT"))
    )
    (comp (ref "D39")
      (value "L-1334SRT")
      (footprint "eagle-import:LED3MM")
      (libsource (lib "eagle-import") (part "L-1334SRT"))
    )
    (comp (ref "Q189")
      (value "2N7000")
      (footprint "eagle-import:TO92-DGS")
      (libsource (lib "eagle-import") (part "2N7000"))
    )
    (comp (ref "Q190")
      (value "2N7000")
      (footprint "eagle-import:TO92-DGS")
      (libsource (lib "eagle-import") (part "2N7000"))
    )
    (comp (ref "Q191")
      (value "2N7000")
      (footprint "eagle-import:TO92-DGS")
      (libsource (lib "eagle-import") (part "2N7000"))
    )
    (comp (ref "Q192")
      (value "2N7000")
      (footprint "eagle-import:TO92-DGS")
      (libsource (lib "eagle-import") (part "2N7000"))
    )
    (comp (ref "Q193")
      (value "2N7000")
      (footprint "eagle-import:TO92-DGS")
      (libsource (lib "eagle-import") (part "2N7000"))
    )
    (comp (ref "Q194")
      (value "2N7000")
      (footprint "eagle-import:TO92-DGS")
      (libsource (lib "eagle-import") (part "2N7000"))
    )
    (comp (ref "Q195")
      (value "2N7000")
      (footprint "eagle-import:TO92-DGS")
      (libsource (lib "eagle-import") (part "2N7000"))
    )
    (comp (ref "Q196")
      (value "2N7000")
      (footprint "eagle-import:TO92-DGS")
      (libsource (lib "eagle-import") (part "2N7000"))
    )
    (comp (ref "Q197")
      (value "2N7000")
      (footprint "eagle-import:TO92-DGS")
      (libsource (lib "eagle-import") (part "2N7000"))
    )
    (comp (ref "Q198")
      (value "2N7000")
      (footprint "eagle-import:TO92-DGS")
      (libsource (lib "eagle-import") (part "2N7000"))
    )
    (comp (ref "Q199")
      (value "2N7000")
      (footprint "eagle-import:TO92-DGS")
      (libsource (lib "eagle-import") (part "2N7000"))
    )
    (comp (ref "Q200")
      (value "2N7000")
      (footprint "eagle-import:TO92-DGS")
      (libsource (lib "eagle-import") (part "2N7000"))
    )
    (comp (ref "Q201")
      (value "2N7000")
      (footprint "eagle-import:TO92-DGS")
      (libsource (lib "eagle-import") (part "2N7000"))
    )
    (comp (ref "Q202")
      (value "2N7000")
      (footprint "eagle-import:TO92-DGS")
      (libsource (lib "eagle-import") (part "2N7000"))
    )
    (comp (ref "Q203")
      (value "2N7000")
      (footprint "eagle-import:TO92-DGS")
      (libsource (lib "eagle-import") (part "2N7000"))
    )
    (comp (ref "Q204")
      (value "2N7000")
      (footprint "eagle-import:TO92-DGS")
      (libsource (lib "eagle-import") (part "2N7000"))
    )
    (comp (ref "Q205")
      (value "2N7000")
      (footprint "eagle-import:TO92-DGS")
      (libsource (lib "eagle-import") (part "2N7000"))
    )
    (comp (ref "Q206")
      (value "2N7000")
      (footprint "eagle-import:TO92-DGS")
      (libsource (lib "eagle-import") (part "2N7000"))
    )
    (comp (ref "Q207")
      (value "2N7000")
      (footprint "eagle-import:TO92-DGS")
      (libsource (lib "eagle-import") (part "2N7000"))
    )
    (comp (ref "Q208")
      (value "2N7000")
      (footprint "eagle-import:TO92-DGS")
      (libsource (lib "eagle-import") (part "2N7000"))
    )
    (comp (ref "R209")
      (value "10k")
      (footprint "eagle-import:R_P2INCH")
      (libsource (lib "eagle-import") (part "R_P2INCH"))
    )
    (comp (ref "R210")
      (value "470")
      (footprint "eagle-import:R_P2INCH")
      (libsource (lib "eagle-import") (part "R_P2INCH"))
    )
    (comp (ref "R211")
      (value "10k")
      (footprint "eagle-import:R_P2INCH")
      (libsource (lib "eagle-import") (part "R_P2INCH"))
    )
    (comp (ref "R212")
      (value "470")
      (footprint "eagle-import:R_P2INCH")
      (libsource (lib "eagle-import") (part "R_P2INCH"))
    )
    (comp (ref "R213")
      (value "10k")
      (footprint "eagle-import:R_P2INCH")
      (libsource (lib "eagle-import") (part "R_P2INCH"))
    )
    (comp (ref "R214")
      (value "470")
      (footprint "eagle-import:R_P2INCH")
      (libsource (lib "eagle-import") (part "R_P2INCH"))
    )
    (comp (ref "R215")
      (value "10k")
      (footprint "eagle-import:R_P2INCH")
      (libsource (lib "eagle-import") (part "R_P2INCH"))
    )
    (comp (ref "R216")
      (value "470")
      (footprint "eagle-import:R_P2INCH")
      (libsource (lib "eagle-import") (part "R_P2INCH"))
    )
    (comp (ref "R253")
      (value "10k")
      (footprint "eagle-import:R_P2INCH")
      (libsource (lib "eagle-import") (part "R_P2INCH"))
    )
    (comp (ref "R254")
      (value "10k")
      (footprint "eagle-import:R_P2INCH")
      (libsource (lib "eagle-import") (part "R_P2INCH"))
    )
    (comp (ref "R255")
      (value "10k")
      (footprint "eagle-import:R_P2INCH")
      (libsource (lib "eagle-import") (part "R_P2INCH"))
    )
    (comp (ref "R256")
      (value "10k")
      (footprint "eagle-import:R_P2INCH")
      (libsource (lib "eagle-import") (part "R_P2INCH"))
    )
    (comp (ref "D17")
      (value "L-1334SRT")
      (footprint "eagle-import:LED3MM")
      (libsource (lib "eagle-import") (part "L-1334SRT"))
    )
    (comp (ref "D18")
      (value "L-1334SRT")
      (footprint "eagle-import:LED3MM")
      (libsource (lib "eagle-import") (part "L-1334SRT"))
    )
    (comp (ref "D19")
      (value "L-1334SRT")
      (footprint "eagle-import:LED3MM")
      (libsource (lib "eagle-import") (part "L-1334SRT"))
    )
    (comp (ref "D20")
      (value "L-1334SRT")
      (footprint "eagle-import:LED3MM")
      (libsource (lib "eagle-import") (part "L-1334SRT"))
    )
    (comp (ref "D21")
      (value "L-1334SRT")
      (footprint "eagle-import:LED3MM")
      (libsource (lib "eagle-import") (part "L-1334SRT"))
    )
    (comp (ref "D22")
      (value "L-1334SRT")
      (footprint "eagle-import:LED3MM")
      (libsource (lib "eagle-import") (part "L-1334SRT"))
    )
    (comp (ref "D23")
      (value "L-1334SRT")
      (footprint "eagle-import:LED3MM")
      (libsource (lib "eagle-import") (part "L-1334SRT"))
    )
    (comp (ref "D24")
      (value "L-1334SRT")
      (footprint "eagle-import:LED3MM")
      (libsource (lib "eagle-import") (part "L-1334SRT"))
    )
    (comp (ref "Q85")
      (value "2N7000")
      (footprint "eagle-import:TO92-DGS")
      (libsource (lib "eagle-import") (part "2N7000"))
    )
    (comp (ref "Q86")
      (value "2N7000")
      (footprint "eagle-import:TO92-DGS")
      (libsource (lib "eagle-import") (part "2N7000"))
    )
    (comp (ref "Q87")
      (value "2N7000")
      (footprint "eagle-import:TO92-DGS")
      (libsource (lib "eagle-import") (part "2N7000"))
    )
    (comp (ref "Q88")
      (value "2N7000")
      (footprint "eagle-import:TO92-DGS")
      (libsource (lib "eagle-import") (part "2N7000"))
    )
    (comp (ref "Q89")
      (value "2N7000")
      (footprint "eagle-import:TO92-DGS")
      (libsource (lib "eagle-import") (part "2N7000"))
    )
    (comp (ref "Q90")
      (value "2N7000")
      (footprint "eagle-import:TO92-DGS")
      (libsource (lib "eagle-import") (part "2N7000"))
    )
    (comp (ref "Q91")
      (value "2N7000")
      (footprint "eagle-import:TO92-DGS")
      (libsource (lib "eagle-import") (part "2N7000"))
    )
    (comp (ref "Q92")
      (value "2N7000")
      (footprint "eagle-import:TO92-DGS")
      (libsource (lib "eagle-import") (part "2N7000"))
    )
    (comp (ref "Q93")
      (value "2N7000")
      (footprint "eagle-import:TO92-DGS")
      (libsource (lib "eagle-import") (part "2N7000"))
    )
    (comp (ref "Q94")
      (value "2N7000")
      (footprint "eagle-import:TO92-DGS")
      (libsource (lib "eagle-import") (part "2N7000"))
    )
    (comp (ref "Q95")
      (value "2N7000")
      (footprint "eagle-import:TO92-DGS")
      (libsource (lib "eagle-import") (part "2N7000"))
    )
    (comp (ref "Q96")
      (value "2N7000")
      (footprint "eagle-import:TO92-DGS")
      (libsource (lib "eagle-import") (part "2N7000"))
    )
    (comp (ref "Q97")
      (value "2N7000")
      (footprint "eagle-import:TO92-DGS")
      (libsource (lib "eagle-import") (part "2N7000"))
    )
    (comp (ref "Q98")
      (value "2N7000")
      (footprint "eagle-import:TO92-DGS")
      (libsource (lib "eagle-import") (part "2N7000"))
    )
    (comp (ref "Q99")
      (value "2N7000")
      (footprint "eagle-import:TO92-DGS")
      (libsource (lib "eagle-import") (part "2N7000"))
    )
    (comp (ref "Q100")
      (value "2N7000")
      (footprint "eagle-import:TO92-DGS")
      (libsource (lib "eagle-import") (part "2N7000"))
    )
    (comp (ref "R101")
      (value "10k")
      (footprint "eagle-import:R_P2INCH")
      (libsource (lib "eagle-import") (part "R_P2INCH"))
    )
    (comp (ref "R102")
      (value "470")
      (footprint "eagle-import:R_P2INCH")
      (libsource (lib "eagle-import") (part "R_P2INCH"))
    )
    (comp (ref "R103")
      (value "10k")
      (footprint "eagle-import:R_P2INCH")
      (libsource (lib "eagle-import") (part "R_P2INCH"))
    )
    (comp (ref "R104")
      (value "470")
      (footprint "eagle-import:R_P2INCH")
      (libsource (lib "eagle-import") (part "R_P2INCH"))
    )
    (comp (ref "R105")
      (value "10k")
      (footprint "eagle-import:R_P2INCH")
      (libsource (lib "eagle-import") (part "R_P2INCH"))
    )
    (comp (ref "R106")
      (value "470")
      (footprint "eagle-import:R_P2INCH")
      (libsource (lib "eagle-import") (part "R_P2INCH"))
    )
    (comp (ref "R107")
      (value "10k")
      (footprint "eagle-import:R_P2INCH")
      (libsource (lib "eagle-import") (part "R_P2INCH"))
    )
    (comp (ref "R108")
      (value "470")
      (footprint "eagle-import:R_P2INCH")
      (libsource (lib "eagle-import") (part "R_P2INCH"))
    )
    (comp (ref "R109")
      (value "10k")
      (footprint "eagle-import:R_P2INCH")
      (libsource (lib "eagle-import") (part "R_P2INCH"))
    )
    (comp (ref "R110")
      (value "470")
      (footprint "eagle-import:R_P2INCH")
      (libsource (lib "eagle-import") (part "R_P2INCH"))
    )
    (comp (ref "R111")
      (value "10k")
      (footprint "eagle-import:R_P2INCH")
      (libsource (lib "eagle-import") (part "R_P2INCH"))
    )
    (comp (ref "R112")
      (value "470")
      (footprint "eagle-import:R_P2INCH")
      (libsource (lib "eagle-import") (part "R_P2INCH"))
    )
    (comp (ref "R113")
      (value "10k")
      (footprint "eagle-import:R_P2INCH")
      (libsource (lib "eagle-import") (part "R_P2INCH"))
    )
    (comp (ref "R114")
      (value "470")
      (footprint "eagle-import:R_P2INCH")
      (libsource (lib "eagle-import") (part "R_P2INCH"))
    )
    (comp (ref "R115")
      (value "10k")
      (footprint "eagle-import:R_P2INCH")
      (libsource (lib "eagle-import") (part "R_P2INCH"))
    )
    (comp (ref "R116")
      (value "470")
      (footprint "eagle-import:R_P2INCH")
      (libsource (lib "eagle-import") (part "R_P2INCH"))
    )
    (comp (ref "R117")
      (value "10k")
      (footprint "eagle-import:R_P2INCH")
      (libsource (lib "eagle-import") (part "R_P2INCH"))
    )
    (comp (ref "R118")
      (value "10k")
      (footprint "eagle-import:R_P2INCH")
      (libsource (lib "eagle-import") (part "R_P2INCH"))
    )
    (comp (ref "R119")
      (value "10k")
      (footprint "eagle-import:R_P2INCH")
      (libsource (lib "eagle-import") (part "R_P2INCH"))
    )
    (comp (ref "R120")
      (value "10k")
      (footprint "eagle-import:R_P2INCH")
      (libsource (lib "eagle-import") (part "R_P2INCH"))
    )
    (comp (ref "R121")
      (value "10k")
      (footprint "eagle-import:R_P2INCH")
      (libsource (lib "eagle-import") (part "R_P2INCH"))
    )
    (comp (ref "R122")
      (value "10k")
      (footprint "eagle-import:R_P2INCH")
      (libsource (lib "eagle-import") (part "R_P2INCH"))
    )
    (comp (ref "R123")
      (value "10k")
      (footprint "eagle-import:R_P2INCH")
      (libsource (lib "eagle-import") (part "R_P2INCH"))
    )
    (comp (ref "R124")
      (value "10k")
      (footprint "eagle-import:R_P2INCH")
      (libsource (lib "eagle-import") (part "R_P2INCH"))
    )
    (comp (ref "J7")
      (value "20_HDR_LOCKING_RA")
      (footprint "eagle-import:20_HDR_LOCKING_RA")
      (libsource (lib "eagle-import") (part "20_HDR_LOCKING_RA"))
    )
    (comp (ref "J8")
      (value "20_HDR_LOCKING_RA")
      (footprint "eagle-import:20_HDR_LOCKING_RA")
      (libsource (lib "eagle-import") (part "20_HDR_LOCKING_RA"))
    )
    (comp (ref "Q143")
      (value "2N7000")
      (footprint "eagle-import:TO92-DGS")
      (libsource (lib "eagle-import") (part "2N7000"))
    )
    (comp (ref "Q144")
      (value "2N7000")
      (footprint "eagle-import:TO92-DGS")
      (libsource (lib "eagle-import") (part "2N7000"))
    )
    (comp (ref "R175")
      (value "10k")
      (footprint "eagle-import:R_P2INCH")
      (libsource (lib "eagle-import") (part "R_P2INCH"))
    )
    (comp (ref "R176")
      (value "10k")
      (footprint "eagle-import:R_P2INCH")
      (libsource (lib "eagle-import") (part "R_P2INCH"))
    )
    (comp (ref "J9")
      (value "20_HDR_LOCKING_RA")
      (footprint "eagle-import:20_HDR_LOCKING_RA")
      (libsource (lib "eagle-import") (part "20_HDR_LOCKING_RA"))
    )
    (comp (ref "J10")
      (value "20_HDR_LOCKING_RA")
      (footprint "eagle-import:20_HDR_LOCKING_RA")
      (libsource (lib "eagle-import") (part "20_HDR_LOCKING_RA"))
    )
    (comp (ref "J11")
      (value "JUMP_2X1")
      (footprint "eagle-import:JUMP_2X1")
      (libsource (lib "eagle-import") (part "JUMP_2X1"))
    )
    (comp (ref "J12")
      (value "JUMP_16X1")
      (footprint "eagle-import:JUMP_16X1")
      (libsource (lib "eagle-import") (part "JUMP_16X1"))
    )
    (comp (ref "Q233")
      (value "2N7000")
      (footprint "eagle-import:TO92-DGS")
      (libsource (lib "eagle-import") (part "2N7000"))
    )
    (comp (ref "Q234")
      (value "2N7000")
      (footprint "eagle-import:TO92-DGS")
      (libsource (lib "eagle-import") (part "2N7000"))
    )
    (comp (ref "Q235")
      (value "2N7000")
      (footprint "eagle-import:TO92-DGS")
      (libsource (lib "eagle-import") (part "2N7000"))
    )
    (comp (ref "Q236")
      (value "2N7000")
      (footprint "eagle-import:TO92-DGS")
      (libsource (lib "eagle-import") (part "2N7000"))
    )
    (comp (ref "Q237")
      (value "2N7000")
      (footprint "eagle-import:TO92-DGS")
      (libsource (lib "eagle-import") (part "2N7000"))
    )
    (comp (ref "Q238")
      (value "2N7000")
      (footprint "eagle-import:TO92-DGS")
      (libsource (lib "eagle-import") (part "2N7000"))
    )
    (comp (ref "Q239")
      (value "2N7000")
      (footprint "eagle-import:TO92-DGS")
      (libsource (lib "eagle-import") (part "2N7000"))
    )
    (comp (ref "Q240")
      (value "2N7000")
      (footprint "eagle-import:TO92-DGS")
      (libsource (lib "eagle-import") (part "2N7000"))
    )
    (comp (ref "Q241")
      (value "2N7000")
      (footprint "eagle-import:TO92-DGS")
      (libsource (lib "eagle-import") (part "2N7000"))
    )
    (comp (ref "Q242")
      (value "2N7000")
      (footprint "eagle-import:TO92-DGS")
      (libsource (lib "eagle-import") (part "2N7000"))
    )
    (comp (ref "Q243")
      (value "2N7000")
      (footprint "eagle-import:TO92-DGS")
      (libsource (lib "eagle-import") (part "2N7000"))
    )
    (comp (ref "Q244")
      (value "2N7000")
      (footprint "eagle-import:TO92-DGS")
      (libsource (lib "eagle-import") (part "2N7000"))
    )
    (comp (ref "Q245")
      (value "2N7000")
      (footprint "eagle-import:TO92-DGS")
      (libsource (lib "eagle-import") (part "2N7000"))
    )
    (comp (ref "Q246")
      (value "2N7000")
      (footprint "eagle-import:TO92-DGS")
      (libsource (lib "eagle-import") (part "2N7000"))
    )
    (comp (ref "Q247")
      (value "2N7000")
      (footprint "eagle-import:TO92-DGS")
      (libsource (lib "eagle-import") (part "2N7000"))
    )
    (comp (ref "Q248")
      (value "2N7000")
      (footprint "eagle-import:TO92-DGS")
      (libsource (lib "eagle-import") (part "2N7000"))
    )
    (comp (ref "Q249")
      (value "2N7000")
      (footprint "eagle-import:TO92-DGS")
      (libsource (lib "eagle-import") (part "2N7000"))
    )
    (comp (ref "Q250")
      (value "2N7000")
      (footprint "eagle-import:TO92-DGS")
      (libsource (lib "eagle-import") (part "2N7000"))
    )
    (comp (ref "Q251")
      (value "2N7000")
      (footprint "eagle-import:TO92-DGS")
      (libsource (lib "eagle-import") (part "2N7000"))
    )
    (comp (ref "Q252")
      (value "2N7000")
      (footprint "eagle-import:TO92-DGS")
      (libsource (lib "eagle-import") (part "2N7000"))
    )
    (comp (ref "R241")
      (value "10k")
      (footprint "eagle-import:R_P2INCH")
      (libsource (lib "eagle-import") (part "R_P2INCH"))
    )
    (comp (ref "R242")
      (value "10k")
      (footprint "eagle-import:R_P2INCH")
      (libsource (lib "eagle-import") (part "R_P2INCH"))
    )
    (comp (ref "R243")
      (value "10k")
      (footprint "eagle-import:R_P2INCH")
      (libsource (lib "eagle-import") (part "R_P2INCH"))
    )
    (comp (ref "R244")
      (value "10k")
      (footprint "eagle-import:R_P2INCH")
      (libsource (lib "eagle-import") (part "R_P2INCH"))
    )
    (comp (ref "R245")
      (value "10k")
      (footprint "eagle-import:R_P2INCH")
      (libsource (lib "eagle-import") (part "R_P2INCH"))
    )
    (comp (ref "R246")
      (value "10k")
      (footprint "eagle-import:R_P2INCH")
      (libsource (lib "eagle-import") (part "R_P2INCH"))
    )
    (comp (ref "R247")
      (value "10k")
      (footprint "eagle-import:R_P2INCH")
      (libsource (lib "eagle-import") (part "R_P2INCH"))
    )
    (comp (ref "R248")
      (value "10k")
      (footprint "eagle-import:R_P2INCH")
      (libsource (lib "eagle-import") (part "R_P2INCH"))
    )
    (comp (ref "R249")
      (value "10k")
      (footprint "eagle-import:R_P2INCH")
      (libsource (lib "eagle-import") (part "R_P2INCH"))
    )
    (comp (ref "R250")
      (value "10k")
      (footprint "eagle-import:R_P2INCH")
      (libsource (lib "eagle-import") (part "R_P2INCH"))
    )
    (comp (ref "R251")
      (value "10k")
      (footprint "eagle-import:R_P2INCH")
      (libsource (lib "eagle-import") (part "R_P2INCH"))
    )
    (comp (ref "R252")
      (value "10k")
      (footprint "eagle-import:R_P2INCH")
      (libsource (lib "eagle-import") (part "R_P2INCH"))
    )
    (comp (ref "D33")
      (value "L-1334SRT")
      (footprint "eagle-import:LED3MM")
      (libsource (lib "eagle-import") (part "L-1334SRT"))
    )
    (comp (ref "D34")
      (value "L-1334SRT")
      (footprint "eagle-import:LED3MM")
      (libsource (lib "eagle-import") (part "L-1334SRT"))
    )
    (comp (ref "D35")
      (value "L-1334SRT")
      (footprint "eagle-import:LED3MM")
      (libsource (lib "eagle-import") (part "L-1334SRT"))
    )
    (comp (ref "D69")
      (value "L-1334SRT")
      (footprint "eagle-import:LED3MM")
      (libsource (lib "eagle-import") (part "L-1334SRT"))
    )
    (comp (ref "Q169")
      (value "2N7000")
      (footprint "eagle-import:TO92-DGS")
      (libsource (lib "eagle-import") (part "2N7000"))
    )
    (comp (ref "Q170")
      (value "2N7000")
      (footprint "eagle-import:TO92-DGS")
      (libsource (lib "eagle-import") (part "2N7000"))
    )
    (comp (ref "Q171")
      (value "2N7000")
      (footprint "eagle-import:TO92-DGS")
      (libsource (lib "eagle-import") (part "2N7000"))
    )
    (comp (ref "Q172")
      (value "2N7000")
      (footprint "eagle-import:TO92-DGS")
      (libsource (lib "eagle-import") (part "2N7000"))
    )
    (comp (ref "Q173")
      (value "2N7000")
      (footprint "eagle-import:TO92-DGS")
      (libsource (lib "eagle-import") (part "2N7000"))
    )
    (comp (ref "Q174")
      (value "2N7000")
      (footprint "eagle-import:TO92-DGS")
      (libsource (lib "eagle-import") (part "2N7000"))
    )
    (comp (ref "Q175")
      (value "2N7000")
      (footprint "eagle-import:TO92-DGS")
      (libsource (lib "eagle-import") (part "2N7000"))
    )
    (comp (ref "Q176")
      (value "2N7000")
      (footprint "eagle-import:TO92-DGS")
      (libsource (lib "eagle-import") (part "2N7000"))
    )
    (comp (ref "Q177")
      (value "2N7000")
      (footprint "eagle-import:TO92-DGS")
      (libsource (lib "eagle-import") (part "2N7000"))
    )
    (comp (ref "Q178")
      (value "2N7000")
      (footprint "eagle-import:TO92-DGS")
      (libsource (lib "eagle-import") (part "2N7000"))
    )
    (comp (ref "Q179")
      (value "2N7000")
      (footprint "eagle-import:TO92-DGS")
      (libsource (lib "eagle-import") (part "2N7000"))
    )
    (comp (ref "Q180")
      (value "2N7000")
      (footprint "eagle-import:TO92-DGS")
      (libsource (lib "eagle-import") (part "2N7000"))
    )
    (comp (ref "Q181")
      (value "2N7000")
      (footprint "eagle-import:TO92-DGS")
      (libsource (lib "eagle-import") (part "2N7000"))
    )
    (comp (ref "Q182")
      (value "2N7000")
      (footprint "eagle-import:TO92-DGS")
      (libsource (lib "eagle-import") (part "2N7000"))
    )
    (comp (ref "Q183")
      (value "2N7000")
      (footprint "eagle-import:TO92-DGS")
      (libsource (lib "eagle-import") (part "2N7000"))
    )
    (comp (ref "Q184")
      (value "2N7000")
      (footprint "eagle-import:TO92-DGS")
      (libsource (lib "eagle-import") (part "2N7000"))
    )
    (comp (ref "Q185")
      (value "2N7000")
      (footprint "eagle-import:TO92-DGS")
      (libsource (lib "eagle-import") (part "2N7000"))
    )
    (comp (ref "Q186")
      (value "2N7000")
      (footprint "eagle-import:TO92-DGS")
      (libsource (lib "eagle-import") (part "2N7000"))
    )
    (comp (ref "Q187")
      (value "2N7000")
      (footprint "eagle-import:TO92-DGS")
      (libsource (lib "eagle-import") (part "2N7000"))
    )
    (comp (ref "Q188")
      (value "2N7000")
      (footprint "eagle-import:TO92-DGS")
      (libsource (lib "eagle-import") (part "2N7000"))
    )
    (comp (ref "R201")
      (value "10k")
      (footprint "eagle-import:R_P2INCH")
      (libsource (lib "eagle-import") (part "R_P2INCH"))
    )
    (comp (ref "R202")
      (value "470")
      (footprint "eagle-import:R_P2INCH")
      (libsource (lib "eagle-import") (part "R_P2INCH"))
    )
    (comp (ref "R203")
      (value "10k")
      (footprint "eagle-import:R_P2INCH")
      (libsource (lib "eagle-import") (part "R_P2INCH"))
    )
    (comp (ref "R204")
      (value "470")
      (footprint "eagle-import:R_P2INCH")
      (libsource (lib "eagle-import") (part "R_P2INCH"))
    )
    (comp (ref "R205")
      (value "10k")
      (footprint "eagle-import:R_P2INCH")
      (libsource (lib "eagle-import") (part "R_P2INCH"))
    )
    (comp (ref "R206")
      (value "470")
      (footprint "eagle-import:R_P2INCH")
      (libsource (lib "eagle-import") (part "R_P2INCH"))
    )
    (comp (ref "R207")
      (value "10k")
      (footprint "eagle-import:R_P2INCH")
      (libsource (lib "eagle-import") (part "R_P2INCH"))
    )
    (comp (ref "R208")
      (value "470")
      (footprint "eagle-import:R_P2INCH")
      (libsource (lib "eagle-import") (part "R_P2INCH"))
    )
    (comp (ref "R257")
      (value "10k")
      (footprint "eagle-import:R_P2INCH")
      (libsource (lib "eagle-import") (part "R_P2INCH"))
    )
    (comp (ref "R258")
      (value "10k")
      (footprint "eagle-import:R_P2INCH")
      (libsource (lib "eagle-import") (part "R_P2INCH"))
    )
    (comp (ref "R259")
      (value "10k")
      (footprint "eagle-import:R_P2INCH")
      (libsource (lib "eagle-import") (part "R_P2INCH"))
    )
    (comp (ref "R260")
      (value "10k")
      (footprint "eagle-import:R_P2INCH")
      (libsource (lib "eagle-import") (part "R_P2INCH"))
    )
    (comp (ref "D1")
      (value "L-1334SRT")
      (footprint "eagle-import:LED3MM")
      (libsource (lib "eagle-import") (part "L-1334SRT"))
    )
    (comp (ref "D2")
      (value "L-1334SRT")
      (footprint "eagle-import:LED3MM")
      (libsource (lib "eagle-import") (part "L-1334SRT"))
    )
    (comp (ref "D3")
      (value "L-1334SRT")
      (footprint "eagle-import:LED3MM")
      (libsource (lib "eagle-import") (part "L-1334SRT"))
    )
    (comp (ref "D4")
      (value "L-1334SRT")
      (footprint "eagle-import:LED3MM")
      (libsource (lib "eagle-import") (part "L-1334SRT"))
    )
    (comp (ref "D5")
      (value "L-1334SRT")
      (footprint "eagle-import:LED3MM")
      (libsource (lib "eagle-import") (part "L-1334SRT"))
    )
    (comp (ref "D6")
      (value "L-1334SRT")
      (footprint "eagle-import:LED3MM")
      (libsource (lib "eagle-import") (part "L-1334SRT"))
    )
    (comp (ref "D7")
      (value "L-1334SRT")
      (footprint "eagle-import:LED3MM")
      (libsource (lib "eagle-import") (part "L-1334SRT"))
    )
    (comp (ref "D8")
      (value "L-1334SRT")
      (footprint "eagle-import:LED3MM")
      (libsource (lib "eagle-import") (part "L-1334SRT"))
    )
    (comp (ref "Q1")
      (value "2N7000")
      (footprint "eagle-import:TO92-DGS")
      (libsource (lib "eagle-import") (part "2N7000"))
    )
    (comp (ref "Q2")
      (value "2N7000")
      (footprint "eagle-import:TO92-DGS")
      (libsource (lib "eagle-import") (part "2N7000"))
    )
    (comp (ref "Q3")
      (value "2N7000")
      (footprint "eagle-import:TO92-DGS")
      (libsource (lib "eagle-import") (part "2N7000"))
    )
    (comp (ref "Q4")
      (value "2N7000")
      (footprint "eagle-import:TO92-DGS")
      (libsource (lib "eagle-import") (part "2N7000"))
    )
    (comp (ref "Q5")
      (value "2N7000")
      (footprint "eagle-import:TO92-DGS")
      (libsource (lib "eagle-import") (part "2N7000"))
    )
    (comp (ref "Q6")
      (value "2N7000")
      (footprint "eagle-import:TO92-DGS")
      (libsource (lib "eagle-import") (part "2N7000"))
    )
    (comp (ref "Q7")
      (value "2N7000")
      (footprint "eagle-import:TO92-DGS")
      (libsource (lib "eagle-import") (part "2N7000"))
    )
    (comp (ref "Q8")
      (value "2N7000")
      (footprint "eagle-import:TO92-DGS")
      (libsource (lib "eagle-import") (part "2N7000"))
    )
    (comp (ref "Q9")
      (value "2N7000")
      (footprint "eagle-import:TO92-DGS")
      (libsource (lib "eagle-import") (part "2N7000"))
    )
    (comp (ref "Q10")
      (value "2N7000")
      (footprint "eagle-import:TO92-DGS")
      (libsource (lib "eagle-import") (part "2N7000"))
    )
    (comp (ref "Q11")
      (value "2N7000")
      (footprint "eagle-import:TO92-DGS")
      (libsource (lib "eagle-import") (part "2N7000"))
    )
    (comp (ref "Q12")
      (value "2N7000")
      (footprint "eagle-import:TO92-DGS")
      (libsource (lib "eagle-import") (part "2N7000"))
    )
    (comp (ref "Q13")
      (value "2N7000")
      (footprint "eagle-import:TO92-DGS")
      (libsource (lib "eagle-import") (part "2N7000"))
    )
    (comp (ref "Q14")
      (value "2N7000")
      (footprint "eagle-import:TO92-DGS")
      (libsource (lib "eagle-import") (part "2N7000"))
    )
    (comp (ref "Q15")
      (value "2N7000")
      (footprint "eagle-import:TO92-DGS")
      (libsource (lib "eagle-import") (part "2N7000"))
    )
    (comp (ref "Q16")
      (value "2N7000")
      (footprint "eagle-import:TO92-DGS")
      (libsource (lib "eagle-import") (part "2N7000"))
    )
    (comp (ref "R1")
      (value "10k")
      (footprint "eagle-import:R_P2INCH")
      (libsource (lib "eagle-import") (part "R_P2INCH"))
    )
    (comp (ref "R2")
      (value "470")
      (footprint "eagle-import:R_P2INCH")
      (libsource (lib "eagle-import") (part "R_P2INCH"))
    )
    (comp (ref "R3")
      (value "10k")
      (footprint "eagle-import:R_P2INCH")
      (libsource (lib "eagle-import") (part "R_P2INCH"))
    )
    (comp (ref "R4")
      (value "470")
      (footprint "eagle-import:R_P2INCH")
      (libsource (lib "eagle-import") (part "R_P2INCH"))
    )
    (comp (ref "R5")
      (value "10k")
      (footprint "eagle-import:R_P2INCH")
      (libsource (lib "eagle-import") (part "R_P2INCH"))
    )
    (comp (ref "R6")
      (value "470")
      (footprint "eagle-import:R_P2INCH")
      (libsource (lib "eagle-import") (part "R_P2INCH"))
    )
    (comp (ref "R7")
      (value "10k")
      (footprint "eagle-import:R_P2INCH")
      (libsource (lib "eagle-import") (part "R_P2INCH"))
    )
    (comp (ref "R8")
      (value "470")
      (footprint "eagle-import:R_P2INCH")
      (libsource (lib "eagle-import") (part "R_P2INCH"))
    )
    (comp (ref "R9")
      (value "10k")
      (footprint "eagle-import:R_P2INCH")
      (libsource (lib "eagle-import") (part "R_P2INCH"))
    )
    (comp (ref "R10")
      (value "470")
      (footprint "eagle-import:R_P2INCH")
      (libsource (lib "eagle-import") (part "R_P2INCH"))
    )
    (comp (ref "R11")
      (value "10k")
      (footprint "eagle-import:R_P2INCH")
      (libsource (lib "eagle-import") (part "R_P2INCH"))
    )
    (comp (ref "R12")
      (value "470")
      (footprint "eagle-import:R_P2INCH")
      (libsource (lib "eagle-import") (part "R_P2INCH"))
    )
    (comp (ref "R13")
      (value "10k")
      (footprint "eagle-import:R_P2INCH")
      (libsource (lib "eagle-import") (part "R_P2INCH"))
    )
    (comp (ref "R14")
      (value "470")
      (footprint "eagle-import:R_P2INCH")
      (libsource (lib "eagle-import") (part "R_P2INCH"))
    )
    (comp (ref "R15")
      (value "10k")
      (footprint "eagle-import:R_P2INCH")
      (libsource (lib "eagle-import") (part "R_P2INCH"))
    )
    (comp (ref "R16")
      (value "470")
      (footprint "eagle-import:R_P2INCH")
      (libsource (lib "eagle-import") (part "R_P2INCH"))
    )
    (comp (ref "R17")
      (value "10k")
      (footprint "eagle-import:R_P2INCH")
      (libsource (lib "eagle-import") (part "R_P2INCH"))
    )
    (comp (ref "R18")
      (value "10k")
      (footprint "eagle-import:R_P2INCH")
      (libsource (lib "eagle-import") (part "R_P2INCH"))
    )
    (comp (ref "R19")
      (value "10k")
      (footprint "eagle-import:R_P2INCH")
      (libsource (lib "eagle-import") (part "R_P2INCH"))
    )
    (comp (ref "R20")
      (value "10k")
      (footprint "eagle-import:R_P2INCH")
      (libsource (lib "eagle-import") (part "R_P2INCH"))
    )
    (comp (ref "R21")
      (value "10k")
      (footprint "eagle-import:R_P2INCH")
      (libsource (lib "eagle-import") (part "R_P2INCH"))
    )
    (comp (ref "R22")
      (value "10k")
      (footprint "eagle-import:R_P2INCH")
      (libsource (lib "eagle-import") (part "R_P2INCH"))
    )
    (comp (ref "R23")
      (value "10k")
      (footprint "eagle-import:R_P2INCH")
      (libsource (lib "eagle-import") (part "R_P2INCH"))
    )
    (comp (ref "R24")
      (value "10k")
      (footprint "eagle-import:R_P2INCH")
      (libsource (lib "eagle-import") (part "R_P2INCH"))
    )
    (comp (ref "D9")
      (value "L-1334SRT")
      (footprint "eagle-import:LED3MM")
      (libsource (lib "eagle-import") (part "L-1334SRT"))
    )
    (comp (ref "D10")
      (value "L-1334SRT")
      (footprint "eagle-import:LED3MM")
      (libsource (lib "eagle-import") (part "L-1334SRT"))
    )
    (comp (ref "D11")
      (value "L-1334SRT")
      (footprint "eagle-import:LED3MM")
      (libsource (lib "eagle-import") (part "L-1334SRT"))
    )
    (comp (ref "D12")
      (value "L-1334SRT")
      (footprint "eagle-import:LED3MM")
      (libsource (lib "eagle-import") (part "L-1334SRT"))
    )
    (comp (ref "D13")
      (value "L-1334SRT")
      (footprint "eagle-import:LED3MM")
      (libsource (lib "eagle-import") (part "L-1334SRT"))
    )
    (comp (ref "D14")
      (value "L-1334SRT")
      (footprint "eagle-import:LED3MM")
      (libsource (lib "eagle-import") (part "L-1334SRT"))
    )
    (comp (ref "D15")
      (value "L-1334SRT")
      (footprint "eagle-import:LED3MM")
      (libsource (lib "eagle-import") (part "L-1334SRT"))
    )
    (comp (ref "D16")
      (value "L-1334SRT")
      (footprint "eagle-import:LED3MM")
      (libsource (lib "eagle-import") (part "L-1334SRT"))
    )
    (comp (ref "Q43")
      (value "2N7000")
      (footprint "eagle-import:TO92-DGS")
      (libsource (lib "eagle-import") (part "2N7000"))
    )
    (comp (ref "Q44")
      (value "2N7000")
      (footprint "eagle-import:TO92-DGS")
      (libsource (lib "eagle-import") (part "2N7000"))
    )
    (comp (ref "Q45")
      (value "2N7000")
      (footprint "eagle-import:TO92-DGS")
      (libsource (lib "eagle-import") (part "2N7000"))
    )
    (comp (ref "Q46")
      (value "2N7000")
      (footprint "eagle-import:TO92-DGS")
      (libsource (lib "eagle-import") (part "2N7000"))
    )
    (comp (ref "Q47")
      (value "2N7000")
      (footprint "eagle-import:TO92-DGS")
      (libsource (lib "eagle-import") (part "2N7000"))
    )
    (comp (ref "Q48")
      (value "2N7000")
      (footprint "eagle-import:TO92-DGS")
      (libsource (lib "eagle-import") (part "2N7000"))
    )
    (comp (ref "Q49")
      (value "2N7000")
      (footprint "eagle-import:TO92-DGS")
      (libsource (lib "eagle-import") (part "2N7000"))
    )
    (comp (ref "Q50")
      (value "2N7000")
      (footprint "eagle-import:TO92-DGS")
      (libsource (lib "eagle-import") (part "2N7000"))
    )
    (comp (ref "Q51")
      (value "2N7000")
      (footprint "eagle-import:TO92-DGS")
      (libsource (lib "eagle-import") (part "2N7000"))
    )
    (comp (ref "Q52")
      (value "2N7000")
      (footprint "eagle-import:TO92-DGS")
      (libsource (lib "eagle-import") (part "2N7000"))
    )
    (comp (ref "Q53")
      (value "2N7000")
      (footprint "eagle-import:TO92-DGS")
      (libsource (lib "eagle-import") (part "2N7000"))
    )
    (comp (ref "Q54")
      (value "2N7000")
      (footprint "eagle-import:TO92-DGS")
      (libsource (lib "eagle-import") (part "2N7000"))
    )
    (comp (ref "Q55")
      (value "2N7000")
      (footprint "eagle-import:TO92-DGS")
      (libsource (lib "eagle-import") (part "2N7000"))
    )
    (comp (ref "Q56")
      (value "2N7000")
      (footprint "eagle-import:TO92-DGS")
      (libsource (lib "eagle-import") (part "2N7000"))
    )
    (comp (ref "Q57")
      (value "2N7000")
      (footprint "eagle-import:TO92-DGS")
      (libsource (lib "eagle-import") (part "2N7000"))
    )
    (comp (ref "Q58")
      (value "2N7000")
      (footprint "eagle-import:TO92-DGS")
      (libsource (lib "eagle-import") (part "2N7000"))
    )
    (comp (ref "R51")
      (value "10k")
      (footprint "eagle-import:R_P2INCH")
      (libsource (lib "eagle-import") (part "R_P2INCH"))
    )
    (comp (ref "R52")
      (value "470")
      (footprint "eagle-import:R_P2INCH")
      (libsource (lib "eagle-import") (part "R_P2INCH"))
    )
    (comp (ref "R53")
      (value "10k")
      (footprint "eagle-import:R_P2INCH")
      (libsource (lib "eagle-import") (part "R_P2INCH"))
    )
    (comp (ref "R54")
      (value "470")
      (footprint "eagle-import:R_P2INCH")
      (libsource (lib "eagle-import") (part "R_P2INCH"))
    )
    (comp (ref "R55")
      (value "10k")
      (footprint "eagle-import:R_P2INCH")
      (libsource (lib "eagle-import") (part "R_P2INCH"))
    )
    (comp (ref "R56")
      (value "470")
      (footprint "eagle-import:R_P2INCH")
      (libsource (lib "eagle-import") (part "R_P2INCH"))
    )
    (comp (ref "R57")
      (value "10k")
      (footprint "eagle-import:R_P2INCH")
      (libsource (lib "eagle-import") (part "R_P2INCH"))
    )
    (comp (ref "R58")
      (value "470")
      (footprint "eagle-import:R_P2INCH")
      (libsource (lib "eagle-import") (part "R_P2INCH"))
    )
    (comp (ref "R59")
      (value "10k")
      (footprint "eagle-import:R_P2INCH")
      (libsource (lib "eagle-import") (part "R_P2INCH"))
    )
    (comp (ref "R60")
      (value "470")
      (footprint "eagle-import:R_P2INCH")
      (libsource (lib "eagle-import") (part "R_P2INCH"))
    )
    (comp (ref "R61")
      (value "10k")
      (footprint "eagle-import:R_P2INCH")
      (libsource (lib "eagle-import") (part "R_P2INCH"))
    )
    (comp (ref "R62")
      (value "470")
      (footprint "eagle-import:R_P2INCH")
      (libsource (lib "eagle-import") (part "R_P2INCH"))
    )
    (comp (ref "R63")
      (value "10k")
      (footprint "eagle-import:R_P2INCH")
      (libsource (lib "eagle-import") (part "R_P2INCH"))
    )
    (comp (ref "R64")
      (value "470")
      (footprint "eagle-import:R_P2INCH")
      (libsource (lib "eagle-import") (part "R_P2INCH"))
    )
    (comp (ref "R65")
      (value "10k")
      (footprint "eagle-import:R_P2INCH")
      (libsource (lib "eagle-import") (part "R_P2INCH"))
    )
    (comp (ref "R66")
      (value "470")
      (footprint "eagle-import:R_P2INCH")
      (libsource (lib "eagle-import") (part "R_P2INCH"))
    )
    (comp (ref "R67")
      (value "10k")
      (footprint "eagle-import:R_P2INCH")
      (libsource (lib "eagle-import") (part "R_P2INCH"))
    )
    (comp (ref "R68")
      (value "10k")
      (footprint "eagle-import:R_P2INCH")
      (libsource (lib "eagle-import") (part "R_P2INCH"))
    )
    (comp (ref "R69")
      (value "10k")
      (footprint "eagle-import:R_P2INCH")
      (libsource (lib "eagle-import") (part "R_P2INCH"))
    )
    (comp (ref "R70")
      (value "10k")
      (footprint "eagle-import:R_P2INCH")
      (libsource (lib "eagle-import") (part "R_P2INCH"))
    )
    (comp (ref "R71")
      (value "10k")
      (footprint "eagle-import:R_P2INCH")
      (libsource (lib "eagle-import") (part "R_P2INCH"))
    )
    (comp (ref "R72")
      (value "10k")
      (footprint "eagle-import:R_P2INCH")
      (libsource (lib "eagle-import") (part "R_P2INCH"))
    )
    (comp (ref "R73")
      (value "10k")
      (footprint "eagle-import:R_P2INCH")
      (libsource (lib "eagle-import") (part "R_P2INCH"))
    )
    (comp (ref "R74")
      (value "10k")
      (footprint "eagle-import:R_P2INCH")
      (libsource (lib "eagle-import") (part "R_P2INCH"))
    )
    (comp (ref "J5")
      (value "20_HDR_LOCKING_RA")
      (footprint "eagle-import:20_HDR_LOCKING_RA")
      (libsource (lib "eagle-import") (part "20_HDR_LOCKING_RA"))
    )
    (comp (ref "J6")
      (value "20_HDR_LOCKING_RA")
      (footprint "eagle-import:20_HDR_LOCKING_RA")
      (libsource (lib "eagle-import") (part "20_HDR_LOCKING_RA"))
    )
    (comp (ref "Q101")
      (value "2N7000")
      (footprint "eagle-import:TO92-DGS")
      (libsource (lib "eagle-import") (part "2N7000"))
    )
    (comp (ref "Q102")
      (value "2N7000")
      (footprint "eagle-import:TO92-DGS")
      (libsource (lib "eagle-import") (part "2N7000"))
    )
    (comp (ref "R125")
      (value "10k")
      (footprint "eagle-import:R_P2INCH")
      (libsource (lib "eagle-import") (part "R_P2INCH"))
    )
    (comp (ref "R126")
      (value "10k")
      (footprint "eagle-import:R_P2INCH")
      (libsource (lib "eagle-import") (part "R_P2INCH"))
    )
    (comp (ref "Q17")
      (value "2N7000")
      (footprint "eagle-import:TO92-DGS")
      (libsource (lib "eagle-import") (part "2N7000"))
    )
    (comp (ref "Q18")
      (value "2N7000")
      (footprint "eagle-import:TO92-DGS")
      (libsource (lib "eagle-import") (part "2N7000"))
    )
    (comp (ref "Q19")
      (value "2N7000")
      (footprint "eagle-import:TO92-DGS")
      (libsource (lib "eagle-import") (part "2N7000"))
    )
    (comp (ref "Q20")
      (value "2N7000")
      (footprint "eagle-import:TO92-DGS")
      (libsource (lib "eagle-import") (part "2N7000"))
    )
    (comp (ref "Q21")
      (value "2N7000")
      (footprint "eagle-import:TO92-DGS")
      (libsource (lib "eagle-import") (part "2N7000"))
    )
    (comp (ref "Q22")
      (value "2N7000")
      (footprint "eagle-import:TO92-DGS")
      (libsource (lib "eagle-import") (part "2N7000"))
    )
    (comp (ref "Q25")
      (value "2N7000")
      (footprint "eagle-import:TO92-DGS")
      (libsource (lib "eagle-import") (part "2N7000"))
    )
    (comp (ref "Q26")
      (value "2N7000")
      (footprint "eagle-import:TO92-DGS")
      (libsource (lib "eagle-import") (part "2N7000"))
    )
    (comp (ref "Q27")
      (value "2N7000")
      (footprint "eagle-import:TO92-DGS")
      (libsource (lib "eagle-import") (part "2N7000"))
    )
    (comp (ref "Q28")
      (value "2N7000")
      (footprint "eagle-import:TO92-DGS")
      (libsource (lib "eagle-import") (part "2N7000"))
    )
    (comp (ref "Q29")
      (value "2N7000")
      (footprint "eagle-import:TO92-DGS")
      (libsource (lib "eagle-import") (part "2N7000"))
    )
    (comp (ref "Q30")
      (value "2N7000")
      (footprint "eagle-import:TO92-DGS")
      (libsource (lib "eagle-import") (part "2N7000"))
    )
    (comp (ref "Q31")
      (value "2N7000")
      (footprint "eagle-import:TO92-DGS")
      (libsource (lib "eagle-import") (part "2N7000"))
    )
    (comp (ref "Q32")
      (value "2N7000")
      (footprint "eagle-import:TO92-DGS")
      (libsource (lib "eagle-import") (part "2N7000"))
    )
    (comp (ref "Q33")
      (value "2N7000")
      (footprint "eagle-import:TO92-DGS")
      (libsource (lib "eagle-import") (part "2N7000"))
    )
    (comp (ref "Q34")
      (value "2N7000")
      (footprint "eagle-import:TO92-DGS")
      (libsource (lib "eagle-import") (part "2N7000"))
    )
    (comp (ref "Q35")
      (value "2N7000")
      (footprint "eagle-import:TO92-DGS")
      (libsource (lib "eagle-import") (part "2N7000"))
    )
    (comp (ref "Q36")
      (value "2N7000")
      (footprint "eagle-import:TO92-DGS")
      (libsource (lib "eagle-import") (part "2N7000"))
    )
    (comp (ref "Q37")
      (value "2N7000")
      (footprint "eagle-import:TO92-DGS")
      (libsource (lib "eagle-import") (part "2N7000"))
    )
    (comp (ref "Q38")
      (value "2N7000")
      (footprint "eagle-import:TO92-DGS")
      (libsource (lib "eagle-import") (part "2N7000"))
    )
    (comp (ref "Q39")
      (value "2N7000")
      (footprint "eagle-import:TO92-DGS")
      (libsource (lib "eagle-import") (part "2N7000"))
    )
    (comp (ref "Q40")
      (value "2N7000")
      (footprint "eagle-import:TO92-DGS")
      (libsource (lib "eagle-import") (part "2N7000"))
    )
    (comp (ref "Q41")
      (value "2N7000")
      (footprint "eagle-import:TO92-DGS")
      (libsource (lib "eagle-import") (part "2N7000"))
    )
    (comp (ref "Q42")
      (value "2N7000")
      (footprint "eagle-import:TO92-DGS")
      (libsource (lib "eagle-import") (part "2N7000"))
    )
    (comp (ref "R25")
      (value "10k")
      (footprint "eagle-import:R_P2INCH")
      (libsource (lib "eagle-import") (part "R_P2INCH"))
    )
    (comp (ref "R26")
      (value "10k")
      (footprint "eagle-import:R_P2INCH")
      (libsource (lib "eagle-import") (part "R_P2INCH"))
    )
    (comp (ref "R27")
      (value "10k")
      (footprint "eagle-import:R_P2INCH")
      (libsource (lib "eagle-import") (part "R_P2INCH"))
    )
    (comp (ref "R28")
      (value "10k")
      (footprint "eagle-import:R_P2INCH")
      (libsource (lib "eagle-import") (part "R_P2INCH"))
    )
    (comp (ref "R29")
      (value "10k")
      (footprint "eagle-import:R_P2INCH")
      (libsource (lib "eagle-import") (part "R_P2INCH"))
    )
    (comp (ref "R30")
      (value "10k")
      (footprint "eagle-import:R_P2INCH")
      (libsource (lib "eagle-import") (part "R_P2INCH"))
    )
    (comp (ref "R33")
      (value "10k")
      (footprint "eagle-import:R_P2INCH")
      (libsource (lib "eagle-import") (part "R_P2INCH"))
    )
    (comp (ref "R34")
      (value "10k")
      (footprint "eagle-import:R_P2INCH")
      (libsource (lib "eagle-import") (part "R_P2INCH"))
    )
    (comp (ref "R35")
      (value "10k")
      (footprint "eagle-import:R_P2INCH")
      (libsource (lib "eagle-import") (part "R_P2INCH"))
    )
    (comp (ref "R36")
      (value "10k")
      (footprint "eagle-import:R_P2INCH")
      (libsource (lib "eagle-import") (part "R_P2INCH"))
    )
    (comp (ref "R37")
      (value "10k")
      (footprint "eagle-import:R_P2INCH")
      (libsource (lib "eagle-import") (part "R_P2INCH"))
    )
    (comp (ref "R38")
      (value "10k")
      (footprint "eagle-import:R_P2INCH")
      (libsource (lib "eagle-import") (part "R_P2INCH"))
    )
    (comp (ref "R39")
      (value "10k")
      (footprint "eagle-import:R_P2INCH")
      (libsource (lib "eagle-import") (part "R_P2INCH"))
    )
    (comp (ref "R40")
      (value "10k")
      (footprint "eagle-import:R_P2INCH")
      (libsource (lib "eagle-import") (part "R_P2INCH"))
    )
    (comp (ref "R41")
      (value "10k")
      (footprint "eagle-import:R_P2INCH")
      (libsource (lib "eagle-import") (part "R_P2INCH"))
    )
    (comp (ref "R42")
      (value "10k")
      (footprint "eagle-import:R_P2INCH")
      (libsource (lib "eagle-import") (part "R_P2INCH"))
    )
    (comp (ref "R43")
      (value "10k")
      (footprint "eagle-import:R_P2INCH")
      (libsource (lib "eagle-import") (part "R_P2INCH"))
    )
    (comp (ref "R44")
      (value "10k")
      (footprint "eagle-import:R_P2INCH")
      (libsource (lib "eagle-import") (part "R_P2INCH"))
    )
    (comp (ref "R45")
      (value "10k")
      (footprint "eagle-import:R_P2INCH")
      (libsource (lib "eagle-import") (part "R_P2INCH"))
    )
    (comp (ref "R46")
      (value "10k")
      (footprint "eagle-import:R_P2INCH")
      (libsource (lib "eagle-import") (part "R_P2INCH"))
    )
    (comp (ref "R47")
      (value "10k")
      (footprint "eagle-import:R_P2INCH")
      (libsource (lib "eagle-import") (part "R_P2INCH"))
    )
    (comp (ref "R48")
      (value "10k")
      (footprint "eagle-import:R_P2INCH")
      (libsource (lib "eagle-import") (part "R_P2INCH"))
    )
    (comp (ref "R49")
      (value "10k")
      (footprint "eagle-import:R_P2INCH")
      (libsource (lib "eagle-import") (part "R_P2INCH"))
    )
    (comp (ref "R50")
      (value "10k")
      (footprint "eagle-import:R_P2INCH")
      (libsource (lib "eagle-import") (part "R_P2INCH"))
    )
  )
  (nets
    (net (code "1") (name "+5V") (class "Default")
      (node (ref "C1") (pin "1") (pinfunction "1_1") (pintype "passive"))
      (node (ref "C2") (pin "1") (pinfunction "1_1") (pintype "passive"))
      (node (ref "C3") (pin "1") (pinfunction "1_1") (pintype "passive"))
      (node (ref "C4") (pin "1") (pinfunction "1_1") (pintype "passive"))
      (node (ref "C5") (pin "1") (pinfunction "1_1") (pintype "passive"))
      (node (ref "C6") (pin "1") (pinfunction "1_1") (pintype "passive"))
      (node (ref "C7") (pin "A") (pinfunction "A_A") (pintype "passive"))
      (node (ref "C8") (pin "1") (pinfunction "1_1") (pintype "passive"))
      (node (ref "D1") (pin "A") (pinfunction "A_A") (pintype "passive"))
      (node (ref "D10") (pin "A") (pinfunction "A_A") (pintype "passive"))
      (node (ref "D11") (pin "A") (pinfunction "A_A") (pintype "passive"))
      (node (ref "D12") (pin "A") (pinfunction "A_A") (pintype "passive"))
      (node (ref "D13") (pin "A") (pinfunction "A_A") (pintype "passive"))
      (node (ref "D14") (pin "A") (pinfunction "A_A") (pintype "passive"))
      (node (ref "D15") (pin "A") (pinfunction "A_A") (pintype "passive"))
      (node (ref "D16") (pin "A") (pinfunction "A_A") (pintype "passive"))
      (node (ref "D17") (pin "A") (pinfunction "A_A") (pintype "passive"))
      (node (ref "D18") (pin "A") (pinfunction "A_A") (pintype "passive"))
      (node (ref "D19") (pin "A") (pinfunction "A_A") (pintype "passive"))
      (node (ref "D2") (pin "A") (pinfunction "A_A") (pintype "passive"))
      (node (ref "D20") (pin "A") (pinfunction "A_A") (pintype "passive"))
      (node (ref "D21") (pin "A") (pinfunction "A_A") (pintype "passive"))
      (node (ref "D22") (pin "A") (pinfunction "A_A") (pintype "passive"))
      (node (ref "D23") (pin "A") (pinfunction "A_A") (pintype "passive"))
      (node (ref "D24") (pin "A") (pinfunction "A_A") (pintype "passive"))
      (node (ref "D25") (pin "A") (pinfunction "A_A") (pintype "passive"))
      (node (ref "D26") (pin "A") (pinfunction "A_A") (pintype "passive"))
      (node (ref "D27") (pin "A") (pinfunction "A_A") (pintype "passive"))
      (node (ref "D28") (pin "A") (pinfunction "A_A") (pintype "passive"))
      (node (ref "D29") (pin "A") (pinfunction "A_A") (pintype "passive"))
      (node (ref "D3") (pin "A") (pinfunction "A_A") (pintype "passive"))
      (node (ref "D30") (pin "A") (pinfunction "A_A") (pintype "passive"))
      (node (ref "D31") (pin "A") (pinfunction "A_A") (pintype "passive"))
      (node (ref "D32") (pin "A") (pinfunction "A_A") (pintype "passive"))
      (node (ref "D33") (pin "A") (pinfunction "A_A") (pintype "passive"))
      (node (ref "D34") (pin "A") (pinfunction "A_A") (pintype "passive"))
      (node (ref "D35") (pin "A") (pinfunction "A_A") (pintype "passive"))
      (node (ref "D36") (pin "A") (pinfunction "A_A") (pintype "passive"))
      (node (ref "D37") (pin "A") (pinfunction "A_A") (pintype "passive"))
      (node (ref "D38") (pin "A") (pinfunction "A_A") (pintype "passive"))
      (node (ref "D39") (pin "A") (pinfunction "A_A") (pintype "passive"))
      (node (ref "D4") (pin "A") (pinfunction "A_A") (pintype "passive"))
      (node (ref "D5") (pin "A") (pinfunction "A_A") (pintype "passive"))
      (node (ref "D6") (pin "A") (pinfunction "A_A") (pintype "passive"))
      (node (ref "D69") (pin "A") (pinfunction "A_A") (pintype "passive"))
      (node (ref "D7") (pin "A") (pinfunction "A_A") (pintype "passive"))
      (node (ref "D8") (pin "A") (pinfunction "A_A") (pintype "passive"))
      (node (ref "D9") (pin "A") (pinfunction "A_A") (pintype "passive"))
      (node (ref "R1") (pin "2") (pinfunction "2_2") (pintype "passive"))
      (node (ref "R100") (pin "2") (pinfunction "2_2") (pintype "passive"))
      (node (ref "R101") (pin "2") (pinfunction "2_2") (pintype "passive"))
      (node (ref "R103") (pin "2") (pinfunction "2_2") (pintype "passive"))
      (node (ref "R105") (pin "2") (pinfunction "2_2") (pintype "passive"))
      (node (ref "R107") (pin "2") (pinfunction "2_2") (pintype "passive"))
      (node (ref "R109") (pin "2") (pinfunction "2_2") (pintype "passive"))
      (node (ref "R11") (pin "2") (pinfunction "2_2") (pintype "passive"))
      (node (ref "R111") (pin "2") (pinfunction "2_2") (pintype "passive"))
      (node (ref "R113") (pin "2") (pinfunction "2_2") (pintype "passive"))
      (node (ref "R115") (pin "2") (pinfunction "2_2") (pintype "passive"))
      (node (ref "R117") (pin "2") (pinfunction "2_2") (pintype "passive"))
      (node (ref "R118") (pin "2") (pinfunction "2_2") (pintype "passive"))
      (node (ref "R119") (pin "2") (pinfunction "2_2") (pintype "passive"))
      (node (ref "R120") (pin "2") (pinfunction "2_2") (pintype "passive"))
      (node (ref "R121") (pin "2") (pinfunction "2_2") (pintype "passive"))
      (node (ref "R122") (pin "2") (pinfunction "2_2") (pintype "passive"))
      (node (ref "R123") (pin "2") (pinfunction "2_2") (pintype "passive"))
      (node (ref "R124") (pin "2") (pinfunction "2_2") (pintype "passive"))
      (node (ref "R125") (pin "2") (pinfunction "2_2") (pintype "passive"))
      (node (ref "R126") (pin "2") (pinfunction "2_2") (pintype "passive"))
      (node (ref "R127") (pin "2") (pinfunction "2_2") (pintype "passive"))
      (node (ref "R128") (pin "2") (pinfunction "2_2") (pintype "passive"))
      (node (ref "R129") (pin "2") (pinfunction "2_2") (pintype "passive"))
      (node (ref "R13") (pin "2") (pinfunction "2_2") (pintype "passive"))
      (node (ref "R130") (pin "2") (pinfunction "2_2") (pintype "passive"))
      (node (ref "R131") (pin "2") (pinfunction "2_2") (pintype "passive"))
      (node (ref "R132") (pin "2") (pinfunction "2_2") (pintype "passive"))
      (node (ref "R133") (pin "2") (pinfunction "2_2") (pintype "passive"))
      (node (ref "R134") (pin "2") (pinfunction "2_2") (pintype "passive"))
      (node (ref "R135") (pin "2") (pinfunction "2_2") (pintype "passive"))
      (node (ref "R136") (pin "2") (pinfunction "2_2") (pintype "passive"))
      (node (ref "R137") (pin "2") (pinfunction "2_2") (pintype "passive"))
      (node (ref "R138") (pin "2") (pinfunction "2_2") (pintype "passive"))
      (node (ref "R139") (pin "2") (pinfunction "2_2") (pintype "passive"))
      (node (ref "R140") (pin "2") (pinfunction "2_2") (pintype "passive"))
      (node (ref "R141") (pin "2") (pinfunction "2_2") (pintype "passive"))
      (node (ref "R142") (pin "2") (pinfunction "2_2") (pintype "passive"))
      (node (ref "R143") (pin "2") (pinfunction "2_2") (pintype "passive"))
      (node (ref "R144") (pin "2") (pinfunction "2_2") (pintype "passive"))
      (node (ref "R145") (pin "2") (pinfunction "2_2") (pintype "passive"))
      (node (ref "R146") (pin "2") (pinfunction "2_2") (pintype "passive"))
      (node (ref "R147") (pin "2") (pinfunction "2_2") (pintype "passive"))
      (node (ref "R148") (pin "2") (pinfunction "2_2") (pintype "passive"))
      (node (ref "R149") (pin "2") (pinfunction "2_2") (pintype "passive"))
      (node (ref "R15") (pin "2") (pinfunction "2_2") (pintype "passive"))
      (node (ref "R150") (pin "2") (pinfunction "2_2") (pintype "passive"))
      (node (ref "R151") (pin "2") (pinfunction "2_2") (pintype "passive"))
      (node (ref "R153") (pin "2") (pinfunction "2_2") (pintype "passive"))
      (node (ref "R155") (pin "2") (pinfunction "2_2") (pintype "passive"))
      (node (ref "R157") (pin "2") (pinfunction "2_2") (pintype "passive"))
      (node (ref "R159") (pin "2") (pinfunction "2_2") (pintype "passive"))
      (node (ref "R161") (pin "2") (pinfunction "2_2") (pintype "passive"))
      (node (ref "R163") (pin "2") (pinfunction "2_2") (pintype "passive"))
      (node (ref "R165") (pin "2") (pinfunction "2_2") (pintype "passive"))
      (node (ref "R167") (pin "2") (pinfunction "2_2") (pintype "passive"))
      (node (ref "R168") (pin "2") (pinfunction "2_2") (pintype "passive"))
      (node (ref "R169") (pin "2") (pinfunction "2_2") (pintype "passive"))
      (node (ref "R17") (pin "2") (pinfunction "2_2") (pintype "passive"))
      (node (ref "R170") (pin "2") (pinfunction "2_2") (pintype "passive"))
      (node (ref "R171") (pin "2") (pinfunction "2_2") (pintype "passive"))
      (node (ref "R172") (pin "2") (pinfunction "2_2") (pintype "passive"))
      (node (ref "R173") (pin "2") (pinfunction "2_2") (pintype "passive"))
      (node (ref "R174") (pin "2") (pinfunction "2_2") (pintype "passive"))
      (node (ref "R175") (pin "2") (pinfunction "2_2") (pintype "passive"))
      (node (ref "R176") (pin "2") (pinfunction "2_2") (pintype "passive"))
      (node (ref "R177") (pin "2") (pinfunction "2_2") (pintype "passive"))
      (node (ref "R178") (pin "2") (pinfunction "2_2") (pintype "passive"))
      (node (ref "R179") (pin "2") (pinfunction "2_2") (pintype "passive"))
      (node (ref "R18") (pin "2") (pinfunction "2_2") (pintype "passive"))
      (node (ref "R180") (pin "2") (pinfunction "2_2") (pintype "passive"))
      (node (ref "R181") (pin "2") (pinfunction "2_2") (pintype "passive"))
      (node (ref "R182") (pin "2") (pinfunction "2_2") (pintype "passive"))
      (node (ref "R183") (pin "2") (pinfunction "2_2") (pintype "passive"))
      (node (ref "R184") (pin "2") (pinfunction "2_2") (pintype "passive"))
      (node (ref "R185") (pin "2") (pinfunction "2_2") (pintype "passive"))
      (node (ref "R186") (pin "2") (pinfunction "2_2") (pintype "passive"))
      (node (ref "R187") (pin "2") (pinfunction "2_2") (pintype "passive"))
      (node (ref "R188") (pin "2") (pinfunction "2_2") (pintype "passive"))
      (node (ref "R189") (pin "2") (pinfunction "2_2") (pintype "passive"))
      (node (ref "R19") (pin "2") (pinfunction "2_2") (pintype "passive"))
      (node (ref "R190") (pin "2") (pinfunction "2_2") (pintype "passive"))
      (node (ref "R191") (pin "2") (pinfunction "2_2") (pintype "passive"))
      (node (ref "R192") (pin "2") (pinfunction "2_2") (pintype "passive"))
      (node (ref "R193") (pin "2") (pinfunction "2_2") (pintype "passive"))
      (node (ref "R194") (pin "2") (pinfunction "2_2") (pintype "passive"))
      (node (ref "R195") (pin "2") (pinfunction "2_2") (pintype "passive"))
      (node (ref "R196") (pin "2") (pinfunction "2_2") (pintype "passive"))
      (node (ref "R197") (pin "2") (pinfunction "2_2") (pintype "passive"))
      (node (ref "R198") (pin "2") (pinfunction "2_2") (pintype "passive"))
      (node (ref "R199") (pin "2") (pinfunction "2_2") (pintype "passive"))
      (node (ref "R20") (pin "2") (pinfunction "2_2") (pintype "passive"))
      (node (ref "R200") (pin "2") (pinfunction "2_2") (pintype "passive"))
      (node (ref "R201") (pin "2") (pinfunction "2_2") (pintype "passive"))
      (node (ref "R203") (pin "2") (pinfunction "2_2") (pintype "passive"))
      (node (ref "R205") (pin "2") (pinfunction "2_2") (pintype "passive"))
      (node (ref "R207") (pin "2") (pinfunction "2_2") (pintype "passive"))
      (node (ref "R209") (pin "2") (pinfunction "2_2") (pintype "passive"))
      (node (ref "R21") (pin "2") (pinfunction "2_2") (pintype "passive"))
      (node (ref "R211") (pin "2") (pinfunction "2_2") (pintype "passive"))
      (node (ref "R213") (pin "2") (pinfunction "2_2") (pintype "passive"))
      (node (ref "R215") (pin "2") (pinfunction "2_2") (pintype "passive"))
      (node (ref "R217") (pin "2") (pinfunction "2_2") (pintype "passive"))
      (node (ref "R218") (pin "2") (pinfunction "2_2") (pintype "passive"))
      (node (ref "R219") (pin "2") (pinfunction "2_2") (pintype "passive"))
      (node (ref "R22") (pin "2") (pinfunction "2_2") (pintype "passive"))
      (node (ref "R220") (pin "2") (pinfunction "2_2") (pintype "passive"))
      (node (ref "R221") (pin "2") (pinfunction "2_2") (pintype "passive"))
      (node (ref "R222") (pin "2") (pinfunction "2_2") (pintype "passive"))
      (node (ref "R223") (pin "2") (pinfunction "2_2") (pintype "passive"))
      (node (ref "R224") (pin "2") (pinfunction "2_2") (pintype "passive"))
      (node (ref "R225") (pin "2") (pinfunction "2_2") (pintype "passive"))
      (node (ref "R226") (pin "2") (pinfunction "2_2") (pintype "passive"))
      (node (ref "R227") (pin "2") (pinfunction "2_2") (pintype "passive"))
      (node (ref "R228") (pin "2") (pinfunction "2_2") (pintype "passive"))
      (node (ref "R229") (pin "2") (pinfunction "2_2") (pintype "passive"))
      (node (ref "R23") (pin "2") (pinfunction "2_2") (pintype "passive"))
      (node (ref "R230") (pin "2") (pinfunction "2_2") (pintype "passive"))
      (node (ref "R231") (pin "2") (pinfunction "2_2") (pintype "passive"))
      (node (ref "R232") (pin "2") (pinfunction "2_2") (pintype "passive"))
      (node (ref "R233") (pin "2") (pinfunction "2_2") (pintype "passive"))
      (node (ref "R234") (pin "2") (pinfunction "2_2") (pintype "passive"))
      (node (ref "R235") (pin "2") (pinfunction "2_2") (pintype "passive"))
      (node (ref "R236") (pin "2") (pinfunction "2_2") (pintype "passive"))
      (node (ref "R237") (pin "2") (pinfunction "2_2") (pintype "passive"))
      (node (ref "R238") (pin "2") (pinfunction "2_2") (pintype "passive"))
      (node (ref "R239") (pin "2") (pinfunction "2_2") (pintype "passive"))
      (node (ref "R24") (pin "2") (pinfunction "2_2") (pintype "passive"))
      (node (ref "R240") (pin "2") (pinfunction "2_2") (pintype "passive"))
      (node (ref "R241") (pin "2") (pinfunction "2_2") (pintype "passive"))
      (node (ref "R242") (pin "2") (pinfunction "2_2") (pintype "passive"))
      (node (ref "R243") (pin "2") (pinfunction "2_2") (pintype "passive"))
      (node (ref "R244") (pin "2") (pinfunction "2_2") (pintype "passive"))
      (node (ref "R245") (pin "2") (pinfunction "2_2") (pintype "passive"))
      (node (ref "R246") (pin "2") (pinfunction "2_2") (pintype "passive"))
      (node (ref "R247") (pin "2") (pinfunction "2_2") (pintype "passive"))
      (node (ref "R248") (pin "2") (pinfunction "2_2") (pintype "passive"))
      (node (ref "R249") (pin "2") (pinfunction "2_2") (pintype "passive"))
      (node (ref "R25") (pin "2") (pinfunction "2_2") (pintype "passive"))
      (node (ref "R250") (pin "2") (pinfunction "2_2") (pintype "passive"))
      (node (ref "R251") (pin "2") (pinfunction "2_2") (pintype "passive"))
      (node (ref "R252") (pin "2") (pinfunction "2_2") (pintype "passive"))
      (node (ref "R253") (pin "2") (pinfunction "2_2") (pintype "passive"))
      (node (ref "R254") (pin "2") (pinfunction "2_2") (pintype "passive"))
      (node (ref "R255") (pin "2") (pinfunction "2_2") (pintype "passive"))
      (node (ref "R256") (pin "2") (pinfunction "2_2") (pintype "passive"))
      (node (ref "R257") (pin "2") (pinfunction "2_2") (pintype "passive"))
      (node (ref "R258") (pin "2") (pinfunction "2_2") (pintype "passive"))
      (node (ref "R259") (pin "2") (pinfunction "2_2") (pintype "passive"))
      (node (ref "R26") (pin "2") (pinfunction "2_2") (pintype "passive"))
      (node (ref "R260") (pin "2") (pinfunction "2_2") (pintype "passive"))
      (node (ref "R27") (pin "2") (pinfunction "2_2") (pintype "passive"))
      (node (ref "R28") (pin "2") (pinfunction "2_2") (pintype "passive"))
      (node (ref "R29") (pin "2") (pinfunction "2_2") (pintype "passive"))
      (node (ref "R3") (pin "2") (pinfunction "2_2") (pintype "passive"))
      (node (ref "R30") (pin "2") (pinfunction "2_2") (pintype "passive"))
      (node (ref "R31") (pin "2") (pinfunction "2_2") (pintype "passive"))
      (node (ref "R32") (pin "2") (pinfunction "2_2") (pintype "passive"))
      (node (ref "R33") (pin "2") (pinfunction "2_2") (pintype "passive"))
      (node (ref "R34") (pin "2") (pinfunction "2_2") (pintype "passive"))
      (node (ref "R35") (pin "2") (pinfunction "2_2") (pintype "passive"))
      (node (ref "R36") (pin "2") (pinfunction "2_2") (pintype "passive"))
      (node (ref "R37") (pin "2") (pinfunction "2_2") (pintype "passive"))
      (node (ref "R38") (pin "2") (pinfunction "2_2") (pintype "passive"))
      (node (ref "R39") (pin "2") (pinfunction "2_2") (pintype "passive"))
      (node (ref "R40") (pin "2") (pinfunction "2_2") (pintype "passive"))
      (node (ref "R41") (pin "2") (pinfunction "2_2") (pintype "passive"))
      (node (ref "R42") (pin "2") (pinfunction "2_2") (pintype "passive"))
      (node (ref "R43") (pin "2") (pinfunction "2_2") (pintype "passive"))
      (node (ref "R44") (pin "2") (pinfunction "2_2") (pintype "passive"))
      (node (ref "R45") (pin "2") (pinfunction "2_2") (pintype "passive"))
      (node (ref "R46") (pin "2") (pinfunction "2_2") (pintype "passive"))
      (node (ref "R47") (pin "2") (pinfunction "2_2") (pintype "passive"))
      (node (ref "R48") (pin "2") (pinfunction "2_2") (pintype "passive"))
      (node (ref "R49") (pin "2") (pinfunction "2_2") (pintype "passive"))
      (node (ref "R5") (pin "2") (pinfunction "2_2") (pintype "passive"))
      (node (ref "R50") (pin "2") (pinfunction "2_2") (pintype "passive"))
      (node (ref "R51") (pin "2") (pinfunction "2_2") (pintype "passive"))
      (node (ref "R53") (pin "2") (pinfunction "2_2") (pintype "passive"))
      (node (ref "R55") (pin "2") (pinfunction "2_2") (pintype "passive"))
      (node (ref "R57") (pin "2") (pinfunction "2_2") (pintype "passive"))
      (node (ref "R59") (pin "2") (pinfunction "2_2") (pintype "passive"))
      (node (ref "R61") (pin "2") (pinfunction "2_2") (pintype "passive"))
      (node (ref "R63") (pin "2") (pinfunction "2_2") (pintype "passive"))
      (node (ref "R65") (pin "2") (pinfunction "2_2") (pintype "passive"))
      (node (ref "R67") (pin "2") (pinfunction "2_2") (pintype "passive"))
      (node (ref "R68") (pin "2") (pinfunction "2_2") (pintype "passive"))
      (node (ref "R69") (pin "2") (pinfunction "2_2") (pintype "passive"))
      (node (ref "R7") (pin "2") (pinfunction "2_2") (pintype "passive"))
      (node (ref "R70") (pin "2") (pinfunction "2_2") (pintype "passive"))
      (node (ref "R71") (pin "2") (pinfunction "2_2") (pintype "passive"))
      (node (ref "R72") (pin "2") (pinfunction "2_2") (pintype "passive"))
      (node (ref "R73") (pin "2") (pinfunction "2_2") (pintype "passive"))
      (node (ref "R74") (pin "2") (pinfunction "2_2") (pintype "passive"))
      (node (ref "R75") (pin "2") (pinfunction "2_2") (pintype "passive"))
      (node (ref "R76") (pin "2") (pinfunction "2_2") (pintype "passive"))
      (node (ref "R77") (pin "2") (pinfunction "2_2") (pintype "passive"))
      (node (ref "R78") (pin "2") (pinfunction "2_2") (pintype "passive"))
      (node (ref "R79") (pin "2") (pinfunction "2_2") (pintype "passive"))
      (node (ref "R80") (pin "2") (pinfunction "2_2") (pintype "passive"))
      (node (ref "R81") (pin "2") (pinfunction "2_2") (pintype "passive"))
      (node (ref "R82") (pin "2") (pinfunction "2_2") (pintype "passive"))
      (node (ref "R83") (pin "2") (pinfunction "2_2") (pintype "passive"))
      (node (ref "R84") (pin "2") (pinfunction "2_2") (pintype "passive"))
      (node (ref "R85") (pin "2") (pinfunction "2_2") (pintype "passive"))
      (node (ref "R86") (pin "2") (pinfunction "2_2") (pintype "passive"))
      (node (ref "R87") (pin "2") (pinfunction "2_2") (pintype "passive"))
      (node (ref "R88") (pin "2") (pinfunction "2_2") (pintype "passive"))
      (node (ref "R89") (pin "2") (pinfunction "2_2") (pintype "passive"))
      (node (ref "R9") (pin "2") (pinfunction "2_2") (pintype "passive"))
      (node (ref "R90") (pin "2") (pinfunction "2_2") (pintype "passive"))
      (node (ref "R91") (pin "2") (pinfunction "2_2") (pintype "passive"))
      (node (ref "R92") (pin "2") (pinfunction "2_2") (pintype "passive"))
      (node (ref "R93") (pin "2") (pinfunction "2_2") (pintype "passive"))
      (node (ref "R94") (pin "2") (pinfunction "2_2") (pintype "passive"))
      (node (ref "R95") (pin "2") (pinfunction "2_2") (pintype "passive"))
      (node (ref "R96") (pin "2") (pinfunction "2_2") (pintype "passive"))
      (node (ref "R97") (pin "2") (pinfunction "2_2") (pintype "passive"))
      (node (ref "R98") (pin "2") (pinfunction "2_2") (pintype "passive"))
      (node (ref "R99") (pin "2") (pinfunction "2_2") (pintype "passive"))
      (node (ref "TP5") (pin "1") (pinfunction "P$1_1") (pintype "bidirectional"))
    )
    (net (code "2") (name "A0") (class "Default")
      (node (ref "J10") (pin "5") (pinfunction "5_5") (pintype "bidirectional"))
      (node (ref "Q217") (pin "G") (pinfunction "G_G") (pintype "passive"))
    )
    (net (code "3") (name "A0_N") (class "Default")
      (node (ref "J12") (pin "1") (pinfunction "1_1") (pintype "passive"))
      (node (ref "Q111") (pin "G") (pinfunction "G_G") (pintype "passive"))
      (node (ref "Q153") (pin "G") (pinfunction "G_G") (pintype "passive"))
      (node (ref "Q17") (pin "G") (pinfunction "G_G") (pintype "passive"))
      (node (ref "Q217") (pin "D") (pinfunction "D_D") (pintype "passive"))
      (node (ref "Q69") (pin "G") (pinfunction "G_G") (pintype "passive"))
      (node (ref "R225") (pin "1") (pinfunction "1_1") (pintype "passive"))
    )
    (net (code "4") (name "A1") (class "Default")
      (node (ref "J10") (pin "6") (pinfunction "6_6") (pintype "bidirectional"))
      (node (ref "Q218") (pin "G") (pinfunction "G_G") (pintype "passive"))
    )
    (net (code "5") (name "A1_N") (class "Default")
      (node (ref "J12") (pin "2") (pinfunction "2_2") (pintype "passive"))
      (node (ref "Q112") (pin "G") (pinfunction "G_G") (pintype "passive"))
      (node (ref "Q154") (pin "G") (pinfunction "G_G") (pintype "passive"))
      (node (ref "Q18") (pin "G") (pinfunction "G_G") (pintype "passive"))
      (node (ref "Q218") (pin "D") (pinfunction "D_D") (pintype "passive"))
      (node (ref "Q70") (pin "G") (pinfunction "G_G") (pintype "passive"))
      (node (ref "R226") (pin "1") (pinfunction "1_1") (pintype "passive"))
    )
    (net (code "6") (name "A2") (class "Default")
      (node (ref "J10") (pin "7") (pinfunction "7_7") (pintype "bidirectional"))
      (node (ref "Q219") (pin "G") (pinfunction "G_G") (pintype "passive"))
    )
    (net (code "7") (name "A2_N") (class "Default")
      (node (ref "J12") (pin "3") (pinfunction "3_3") (pintype "passive"))
      (node (ref "Q113") (pin "G") (pinfunction "G_G") (pintype "passive"))
      (node (ref "Q155") (pin "G") (pinfunction "G_G") (pintype "passive"))
      (node (ref "Q19") (pin "G") (pinfunction "G_G") (pintype "passive"))
      (node (ref "Q219") (pin "D") (pinfunction "D_D") (pintype "passive"))
      (node (ref "Q71") (pin "G") (pinfunction "G_G") (pintype "passive"))
      (node (ref "R227") (pin "1") (pinfunction "1_1") (pintype "passive"))
    )
    (net (code "8") (name "A3") (class "Default")
      (node (ref "J10") (pin "8") (pinfunction "8_8") (pintype "bidirectional"))
      (node (ref "Q220") (pin "G") (pinfunction "G_G") (pintype "passive"))
    )
    (net (code "9") (name "A3_N") (class "Default")
      (node (ref "J12") (pin "4") (pinfunction "4_4") (pintype "passive"))
      (node (ref "Q114") (pin "G") (pinfunction "G_G") (pintype "passive"))
      (node (ref "Q156") (pin "G") (pinfunction "G_G") (pintype "passive"))
      (node (ref "Q20") (pin "G") (pinfunction "G_G") (pintype "passive"))
      (node (ref "Q220") (pin "D") (pinfunction "D_D") (pintype "passive"))
      (node (ref "Q72") (pin "G") (pinfunction "G_G") (pintype "passive"))
      (node (ref "R228") (pin "1") (pinfunction "1_1") (pintype "passive"))
    )
    (net (code "10") (name "A4") (class "Default")
      (node (ref "J10") (pin "9") (pinfunction "9_9") (pintype "bidirectional"))
      (node (ref "Q221") (pin "G") (pinfunction "G_G") (pintype "passive"))
    )
    (net (code "11") (name "A4_N") (class "Default")
      (node (ref "J12") (pin "5") (pinfunction "5_5") (pintype "passive"))
      (node (ref "Q115") (pin "G") (pinfunction "G_G") (pintype "passive"))
      (node (ref "Q157") (pin "G") (pinfunction "G_G") (pintype "passive"))
      (node (ref "Q21") (pin "G") (pinfunction "G_G") (pintype "passive"))
      (node (ref "Q221") (pin "D") (pinfunction "D_D") (pintype "passive"))
      (node (ref "Q73") (pin "G") (pinfunction "G_G") (pintype "passive"))
      (node (ref "R229") (pin "1") (pinfunction "1_1") (pintype "passive"))
    )
    (net (code "12") (name "A5") (class "Default")
      (node (ref "J10") (pin "10") (pinfunction "10_10") (pintype "bidirectional"))
      (node (ref "Q222") (pin "G") (pinfunction "G_G") (pintype "passive"))
    )
    (net (code "13") (name "A5_N") (class "Default")
      (node (ref "J12") (pin "6") (pinfunction "6_6") (pintype "passive"))
      (node (ref "Q116") (pin "G") (pinfunction "G_G") (pintype "passive"))
      (node (ref "Q158") (pin "G") (pinfunction "G_G") (pintype "passive"))
      (node (ref "Q22") (pin "G") (pinfunction "G_G") (pintype "passive"))
      (node (ref "Q222") (pin "D") (pinfunction "D_D") (pintype "passive"))
      (node (ref "Q74") (pin "G") (pinfunction "G_G") (pintype "passive"))
      (node (ref "R230") (pin "1") (pinfunction "1_1") (pintype "passive"))
    )
    (net (code "14") (name "A6") (class "Default")
      (node (ref "J10") (pin "11") (pinfunction "11_11") (pintype "bidirectional"))
      (node (ref "Q223") (pin "G") (pinfunction "G_G") (pintype "passive"))
    )
    (net (code "15") (name "A6_N") (class "Default")
      (node (ref "J12") (pin "7") (pinfunction "7_7") (pintype "passive"))
      (node (ref "Q117") (pin "G") (pinfunction "G_G") (pintype "passive"))
      (node (ref "Q159") (pin "G") (pinfunction "G_G") (pintype "passive"))
      (node (ref "Q223") (pin "D") (pinfunction "D_D") (pintype "passive"))
      (node (ref "Q33") (pin "G") (pinfunction "G_G") (pintype "passive"))
      (node (ref "Q75") (pin "G") (pinfunction "G_G") (pintype "passive"))
      (node (ref "R231") (pin "1") (pinfunction "1_1") (pintype "passive"))
    )
    (net (code "16") (name "A7") (class "Default")
      (node (ref "J10") (pin "12") (pinfunction "12_12") (pintype "bidirectional"))
      (node (ref "Q224") (pin "G") (pinfunction "G_G") (pintype "passive"))
    )
    (net (code "17") (name "A7_N") (class "Default")
      (node (ref "J12") (pin "8") (pinfunction "8_8") (pintype "passive"))
      (node (ref "Q118") (pin "G") (pinfunction "G_G") (pintype "passive"))
      (node (ref "Q160") (pin "G") (pinfunction "G_G") (pintype "passive"))
      (node (ref "Q224") (pin "D") (pinfunction "D_D") (pintype "passive"))
      (node (ref "Q34") (pin "G") (pinfunction "G_G") (pintype "passive"))
      (node (ref "Q76") (pin "G") (pinfunction "G_G") (pintype "passive"))
      (node (ref "R232") (pin "1") (pinfunction "1_1") (pintype "passive"))
    )
    (net (code "18") (name "A8") (class "Default")
      (node (ref "J10") (pin "13") (pinfunction "13_13") (pintype "bidirectional"))
      (node (ref "Q225") (pin "G") (pinfunction "G_G") (pintype "passive"))
    )
    (net (code "19") (name "A8_N") (class "Default")
      (node (ref "J12") (pin "9") (pinfunction "9_9") (pintype "passive"))
      (node (ref "Q119") (pin "G") (pinfunction "G_G") (pintype "passive"))
      (node (ref "Q161") (pin "G") (pinfunction "G_G") (pintype "passive"))
      (node (ref "Q225") (pin "D") (pinfunction "D_D") (pintype "passive"))
      (node (ref "Q35") (pin "G") (pinfunction "G_G") (pintype "passive"))
      (node (ref "Q77") (pin "G") (pinfunction "G_G") (pintype "passive"))
      (node (ref "R233") (pin "1") (pinfunction "1_1") (pintype "passive"))
    )
    (net (code "20") (name "A9") (class "Default")
      (node (ref "J10") (pin "14") (pinfunction "14_14") (pintype "bidirectional"))
      (node (ref "Q226") (pin "G") (pinfunction "G_G") (pintype "passive"))
    )
    (net (code "21") (name "A9_N") (class "Default")
      (node (ref "J12") (pin "10") (pinfunction "10_10") (pintype "passive"))
      (node (ref "Q120") (pin "G") (pinfunction "G_G") (pintype "passive"))
      (node (ref "Q162") (pin "G") (pinfunction "G_G") (pintype "passive"))
      (node (ref "Q226") (pin "D") (pinfunction "D_D") (pintype "passive"))
      (node (ref "Q36") (pin "G") (pinfunction "G_G") (pintype "passive"))
      (node (ref "Q78") (pin "G") (pinfunction "G_G") (pintype "passive"))
      (node (ref "R234") (pin "1") (pinfunction "1_1") (pintype "passive"))
    )
    (net (code "22") (name "A10") (class "Default")
      (node (ref "J10") (pin "15") (pinfunction "15_15") (pintype "bidirectional"))
      (node (ref "Q227") (pin "G") (pinfunction "G_G") (pintype "passive"))
    )
    (net (code "23") (name "A10_N") (class "Default")
      (node (ref "J12") (pin "11") (pinfunction "11_11") (pintype "passive"))
      (node (ref "Q121") (pin "G") (pinfunction "G_G") (pintype "passive"))
      (node (ref "Q163") (pin "G") (pinfunction "G_G") (pintype "passive"))
      (node (ref "Q227") (pin "D") (pinfunction "D_D") (pintype "passive"))
      (node (ref "Q37") (pin "G") (pinfunction "G_G") (pintype "passive"))
      (node (ref "Q79") (pin "G") (pinfunction "G_G") (pintype "passive"))
      (node (ref "R235") (pin "1") (pinfunction "1_1") (pintype "passive"))
    )
    (net (code "24") (name "A11") (class "Default")
      (node (ref "J10") (pin "16") (pinfunction "16_16") (pintype "bidirectional"))
      (node (ref "Q228") (pin "G") (pinfunction "G_G") (pintype "passive"))
    )
    (net (code "25") (name "A11_N") (class "Default")
      (node (ref "J12") (pin "12") (pinfunction "12_12") (pintype "passive"))
      (node (ref "Q122") (pin "G") (pinfunction "G_G") (pintype "passive"))
      (node (ref "Q164") (pin "G") (pinfunction "G_G") (pintype "passive"))
      (node (ref "Q228") (pin "D") (pinfunction "D_D") (pintype "passive"))
      (node (ref "Q38") (pin "G") (pinfunction "G_G") (pintype "passive"))
      (node (ref "Q80") (pin "G") (pinfunction "G_G") (pintype "passive"))
      (node (ref "R236") (pin "1") (pinfunction "1_1") (pintype "passive"))
    )
    (net (code "26") (name "A12") (class "Default")
      (node (ref "J10") (pin "17") (pinfunction "17_17") (pintype "bidirectional"))
      (node (ref "Q229") (pin "G") (pinfunction "G_G") (pintype "passive"))
    )
    (net (code "27") (name "A12_N") (class "Default")
      (node (ref "J12") (pin "13") (pinfunction "13_13") (pintype "passive"))
      (node (ref "Q123") (pin "G") (pinfunction "G_G") (pintype "passive"))
      (node (ref "Q165") (pin "G") (pinfunction "G_G") (pintype "passive"))
      (node (ref "Q229") (pin "D") (pinfunction "D_D") (pintype "passive"))
      (node (ref "Q39") (pin "G") (pinfunction "G_G") (pintype "passive"))
      (node (ref "Q81") (pin "G") (pinfunction "G_G") (pintype "passive"))
      (node (ref "R237") (pin "1") (pinfunction "1_1") (pintype "passive"))
    )
    (net (code "28") (name "A13") (class "Default")
      (node (ref "J10") (pin "18") (pinfunction "18_18") (pintype "bidirectional"))
      (node (ref "Q230") (pin "G") (pinfunction "G_G") (pintype "passive"))
    )
    (net (code "29") (name "A13_N") (class "Default")
      (node (ref "J12") (pin "14") (pinfunction "14_14") (pintype "passive"))
      (node (ref "Q124") (pin "G") (pinfunction "G_G") (pintype "passive"))
      (node (ref "Q166") (pin "G") (pinfunction "G_G") (pintype "passive"))
      (node (ref "Q230") (pin "D") (pinfunction "D_D") (pintype "passive"))
      (node (ref "Q40") (pin "G") (pinfunction "G_G") (pintype "passive"))
      (node (ref "Q82") (pin "G") (pinfunction "G_G") (pintype "passive"))
      (node (ref "R238") (pin "1") (pinfunction "1_1") (pintype "passive"))
    )
    (net (code "30") (name "A14") (class "Default")
      (node (ref "J10") (pin "19") (pinfunction "19_19") (pintype "bidirectional"))
      (node (ref "Q231") (pin "G") (pinfunction "G_G") (pintype "passive"))
    )
    (net (code "31") (name "A14_N") (class "Default")
      (node (ref "J12") (pin "15") (pinfunction "15_15") (pintype "passive"))
      (node (ref "Q125") (pin "G") (pinfunction "G_G") (pintype "passive"))
      (node (ref "Q167") (pin "G") (pinfunction "G_G") (pintype "passive"))
      (node (ref "Q231") (pin "D") (pinfunction "D_D") (pintype "passive"))
      (node (ref "Q41") (pin "G") (pinfunction "G_G") (pintype "passive"))
      (node (ref "Q83") (pin "G") (pinfunction "G_G") (pintype "passive"))
      (node (ref "R239") (pin "1") (pinfunction "1_1") (pintype "passive"))
    )
    (net (code "32") (name "A15") (class "Default")
      (node (ref "J10") (pin "20") (pinfunction "20_20") (pintype "bidirectional"))
      (node (ref "Q232") (pin "G") (pinfunction "G_G") (pintype "passive"))
    )
    (net (code "33") (name "A15_N") (class "Default")
      (node (ref "J12") (pin "16") (pinfunction "16_16") (pintype "passive"))
      (node (ref "Q126") (pin "G") (pinfunction "G_G") (pintype "passive"))
      (node (ref "Q168") (pin "G") (pinfunction "G_G") (pintype "passive"))
      (node (ref "Q232") (pin "D") (pinfunction "D_D") (pintype "passive"))
      (node (ref "Q42") (pin "G") (pinfunction "G_G") (pintype "passive"))
      (node (ref "Q84") (pin "G") (pinfunction "G_G") (pintype "passive"))
      (node (ref "R240") (pin "1") (pinfunction "1_1") (pintype "passive"))
    )
    (net (code "34") (name "CS") (class "Default")
      (node (ref "Q235") (pin "D") (pinfunction "D_D") (pintype "passive"))
      (node (ref "Q239") (pin "G") (pinfunction "G_G") (pintype "passive"))
      (node (ref "Q243") (pin "G") (pinfunction "G_G") (pintype "passive"))
      (node (ref "Q247") (pin "G") (pinfunction "G_G") (pintype "passive"))
      (node (ref "Q251") (pin "G") (pinfunction "G_G") (pintype "passive"))
      (node (ref "R243") (pin "1") (pinfunction "1_1") (pintype "passive"))
    )
    (net (code "35") (name "CS_0_N") (class "Default")
      (node (ref "Q10") (pin "S") (pinfunction "S_S") (pintype "passive"))
      (node (ref "Q12") (pin "S") (pinfunction "S_S") (pintype "passive"))
      (node (ref "Q14") (pin "S") (pinfunction "S_S") (pintype "passive"))
      (node (ref "Q16") (pin "S") (pinfunction "S_S") (pintype "passive"))
      (node (ref "Q2") (pin "S") (pinfunction "S_S") (pintype "passive"))
      (node (ref "Q237") (pin "D") (pinfunction "D_D") (pintype "passive"))
      (node (ref "Q240") (pin "G") (pinfunction "G_G") (pintype "passive"))
      (node (ref "Q4") (pin "S") (pinfunction "S_S") (pintype "passive"))
      (node (ref "Q6") (pin "S") (pinfunction "S_S") (pintype "passive"))
      (node (ref "Q8") (pin "S") (pinfunction "S_S") (pintype "passive"))
      (node (ref "R245") (pin "1") (pinfunction "1_1") (pintype "passive"))
    )
    (net (code "36") (name "CS_1_N") (class "Default")
      (node (ref "Q241") (pin "D") (pinfunction "D_D") (pintype "passive"))
      (node (ref "Q244") (pin "G") (pinfunction "G_G") (pintype "passive"))
      (node (ref "Q44") (pin "S") (pinfunction "S_S") (pintype "passive"))
      (node (ref "Q46") (pin "S") (pinfunction "S_S") (pintype "passive"))
      (node (ref "Q48") (pin "S") (pinfunction "S_S") (pintype "passive"))
      (node (ref "Q50") (pin "S") (pinfunction "S_S") (pintype "passive"))
      (node (ref "Q52") (pin "S") (pinfunction "S_S") (pintype "passive"))
      (node (ref "Q54") (pin "S") (pinfunction "S_S") (pintype "passive"))
      (node (ref "Q56") (pin "S") (pinfunction "S_S") (pintype "passive"))
      (node (ref "Q58") (pin "S") (pinfunction "S_S") (pintype "passive"))
      (node (ref "R247") (pin "1") (pinfunction "1_1") (pintype "passive"))
    )
    (net (code "37") (name "CS_2_N") (class "Default")
      (node (ref "Q100") (pin "S") (pinfunction "S_S") (pintype "passive"))
      (node (ref "Q245") (pin "D") (pinfunction "D_D") (pintype "passive"))
      (node (ref "Q248") (pin "G") (pinfunction "G_G") (pintype "passive"))
      (node (ref "Q86") (pin "S") (pinfunction "S_S") (pintype "passive"))
      (node (ref "Q88") (pin "S") (pinfunction "S_S") (pintype "passive"))
      (node (ref "Q90") (pin "S") (pinfunction "S_S") (pintype "passive"))
      (node (ref "Q92") (pin "S") (pinfunction "S_S") (pintype "passive"))
      (node (ref "Q94") (pin "S") (pinfunction "S_S") (pintype "passive"))
      (node (ref "Q96") (pin "S") (pinfunction "S_S") (pintype "passive"))
      (node (ref "Q98") (pin "S") (pinfunction "S_S") (pintype "passive"))
      (node (ref "R249") (pin "1") (pinfunction "1_1") (pintype "passive"))
    )
    (net (code "38") (name "CS_3_N") (class "Default")
      (node (ref "Q128") (pin "S") (pinfunction "S_S") (pintype "passive"))
      (node (ref "Q130") (pin "S") (pinfunction "S_S") (pintype "passive"))
      (node (ref "Q132") (pin "S") (pinfunction "S_S") (pintype "passive"))
      (node (ref "Q134") (pin "S") (pinfunction "S_S") (pintype "passive"))
      (node (ref "Q136") (pin "S") (pinfunction "S_S") (pintype "passive"))
      (node (ref "Q138") (pin "S") (pinfunction "S_S") (pintype "passive"))
      (node (ref "Q140") (pin "S") (pinfunction "S_S") (pintype "passive"))
      (node (ref "Q142") (pin "S") (pinfunction "S_S") (pintype "passive"))
      (node (ref "Q249") (pin "D") (pinfunction "D_D") (pintype "passive"))
      (node (ref "Q252") (pin "G") (pinfunction "G_G") (pintype "passive"))
      (node (ref "R251") (pin "1") (pinfunction "1_1") (pintype "passive"))
    )
    (net (code "39") (name "CS_N") (class "Default")
      (node (ref "J10") (pin "1") (pinfunction "1_1") (pintype "bidirectional"))
      (node (ref "Q235") (pin "G") (pinfunction "G_G") (pintype "passive"))
    )
    (net (code "40") (name "GND") (class "Default")
      (node (ref "C1") (pin "2") (pinfunction "2_2") (pintype "passive"))
      (node (ref "C2") (pin "2") (pinfunction "2_2") (pintype "passive"))
      (node (ref "C3") (pin "2") (pinfunction "2_2") (pintype "passive"))
      (node (ref "C4") (pin "2") (pinfunction "2_2") (pintype "passive"))
      (node (ref "C5") (pin "2") (pinfunction "2_2") (pintype "passive"))
      (node (ref "C6") (pin "2") (pinfunction "2_2") (pintype "passive"))
      (node (ref "C7") (pin "K") (pinfunction "K_K") (pintype "passive"))
      (node (ref "C8") (pin "2") (pinfunction "2_2") (pintype "passive"))
      (node (ref "J1") (pin "1") (pinfunction "1_1") (pintype "bidirectional"))
      (node (ref "J1") (pin "10") (pinfunction "10_10") (pintype "bidirectional"))
      (node (ref "J1") (pin "11") (pinfunction "11_11") (pintype "bidirectional"))
      (node (ref "J1") (pin "20") (pinfunction "20_20") (pintype "bidirectional"))
      (node (ref "J10") (pin "2") (pinfunction "2_2") (pintype "bidirectional"))
      (node (ref "J10") (pin "4") (pinfunction "4_4") (pintype "bidirectional"))
      (node (ref "J2") (pin "2") (pinfunction "2_2") (pintype "bidirectional"))
      (node (ref "J2") (pin "4") (pinfunction "4_4") (pintype "bidirectional"))
      (node (ref "J3") (pin "1") (pinfunction "1_1") (pintype "bidirectional"))
      (node (ref "J3") (pin "10") (pinfunction "10_10") (pintype "bidirectional"))
      (node (ref "J3") (pin "11") (pinfunction "11_11") (pintype "bidirectional"))
      (node (ref "J3") (pin "20") (pinfunction "20_20") (pintype "bidirectional"))
      (node (ref "J4") (pin "2") (pinfunction "2_2") (pintype "bidirectional"))
      (node (ref "J4") (pin "4") (pinfunction "4_4") (pintype "bidirectional"))
      (node (ref "J5") (pin "1") (pinfunction "1_1") (pintype "bidirectional"))
      (node (ref "J5") (pin "10") (pinfunction "10_10") (pintype "bidirectional"))
      (node (ref "J5") (pin "11") (pinfunction "11_11") (pintype "bidirectional"))
      (node (ref "J5") (pin "20") (pinfunction "20_20") (pintype "bidirectional"))
      (node (ref "J6") (pin "2") (pinfunction "2_2") (pintype "bidirectional"))
      (node (ref "J6") (pin "4") (pinfunction "4_4") (pintype "bidirectional"))
      (node (ref "J7") (pin "1") (pinfunction "1_1") (pintype "bidirectional"))
      (node (ref "J7") (pin "10") (pinfunction "10_10") (pintype "bidirectional"))
      (node (ref "J7") (pin "11") (pinfunction "11_11") (pintype "bidirectional"))
      (node (ref "J7") (pin "20") (pinfunction "20_20") (pintype "bidirectional"))
      (node (ref "J8") (pin "2") (pinfunction "2_2") (pintype "bidirectional"))
      (node (ref "J8") (pin "4") (pinfunction "4_4") (pintype "bidirectional"))
      (node (ref "J9") (pin "1") (pinfunction "1_1") (pintype "bidirectional"))
      (node (ref "J9") (pin "10") (pinfunction "10_10") (pintype "bidirectional"))
      (node (ref "J9") (pin "11") (pinfunction "11_11") (pintype "bidirectional"))
      (node (ref "J9") (pin "20") (pinfunction "20_20") (pintype "bidirectional"))
      (node (ref "Q1") (pin "S") (pinfunction "S_S") (pintype "passive"))
      (node (ref "Q101") (pin "S") (pinfunction "S_S") (pintype "passive"))
      (node (ref "Q102") (pin "S") (pinfunction "S_S") (pintype "passive"))
      (node (ref "Q103") (pin "S") (pinfunction "S_S") (pintype "passive"))
      (node (ref "Q104") (pin "S") (pinfunction "S_S") (pintype "passive"))
      (node (ref "Q105") (pin "S") (pinfunction "S_S") (pintype "passive"))
      (node (ref "Q106") (pin "S") (pinfunction "S_S") (pintype "passive"))
      (node (ref "Q107") (pin "S") (pinfunction "S_S") (pintype "passive"))
      (node (ref "Q108") (pin "S") (pinfunction "S_S") (pintype "passive"))
      (node (ref "Q109") (pin "S") (pinfunction "S_S") (pintype "passive"))
      (node (ref "Q11") (pin "S") (pinfunction "S_S") (pintype "passive"))
      (node (ref "Q110") (pin "S") (pinfunction "S_S") (pintype "passive"))
      (node (ref "Q111") (pin "S") (pinfunction "S_S") (pintype "passive"))
      (node (ref "Q112") (pin "S") (pinfunction "S_S") (pintype "passive"))
      (node (ref "Q113") (pin "S") (pinfunction "S_S") (pintype "passive"))
      (node (ref "Q114") (pin "S") (pinfunction "S_S") (pintype "passive"))
      (node (ref "Q115") (pin "S") (pinfunction "S_S") (pintype "passive"))
      (node (ref "Q116") (pin "S") (pinfunction "S_S") (pintype "passive"))
      (node (ref "Q117") (pin "S") (pinfunction "S_S") (pintype "passive"))
      (node (ref "Q118") (pin "S") (pinfunction "S_S") (pintype "passive"))
      (node (ref "Q119") (pin "S") (pinfunction "S_S") (pintype "passive"))
      (node (ref "Q120") (pin "S") (pinfunction "S_S") (pintype "passive"))
      (node (ref "Q121") (pin "S") (pinfunction "S_S") (pintype "passive"))
      (node (ref "Q122") (pin "S") (pinfunction "S_S") (pintype "passive"))
      (node (ref "Q123") (pin "S") (pinfunction "S_S") (pintype "passive"))
      (node (ref "Q124") (pin "S") (pinfunction "S_S") (pintype "passive"))
      (node (ref "Q125") (pin "S") (pinfunction "S_S") (pintype "passive"))
      (node (ref "Q126") (pin "S") (pinfunction "S_S") (pintype "passive"))
      (node (ref "Q127") (pin "S") (pinfunction "S_S") (pintype "passive"))
      (node (ref "Q129") (pin "S") (pinfunction "S_S") (pintype "passive"))
      (node (ref "Q13") (pin "S") (pinfunction "S_S") (pintype "passive"))
      (node (ref "Q131") (pin "S") (pinfunction "S_S") (pintype "passive"))
      (node (ref "Q133") (pin "S") (pinfunction "S_S") (pintype "passive"))
      (node (ref "Q135") (pin "S") (pinfunction "S_S") (pintype "passive"))
      (node (ref "Q137") (pin "S") (pinfunction "S_S") (pintype "passive"))
      (node (ref "Q139") (pin "S") (pinfunction "S_S") (pintype "passive"))
      (node (ref "Q141") (pin "S") (pinfunction "S_S") (pintype "passive"))
      (node (ref "Q143") (pin "S") (pinfunction "S_S") (pintype "passive"))
      (node (ref "Q144") (pin "S") (pinfunction "S_S") (pintype "passive"))
      (node (ref "Q145") (pin "S") (pinfunction "S_S") (pintype "passive"))
      (node (ref "Q146") (pin "S") (pinfunction "S_S") (pintype "passive"))
      (node (ref "Q147") (pin "S") (pinfunction "S_S") (pintype "passive"))
      (node (ref "Q148") (pin "S") (pinfunction "S_S") (pintype "passive"))
      (node (ref "Q149") (pin "S") (pinfunction "S_S") (pintype "passive"))
      (node (ref "Q15") (pin "S") (pinfunction "S_S") (pintype "passive"))
      (node (ref "Q150") (pin "S") (pinfunction "S_S") (pintype "passive"))
      (node (ref "Q151") (pin "S") (pinfunction "S_S") (pintype "passive"))
      (node (ref "Q152") (pin "S") (pinfunction "S_S") (pintype "passive"))
      (node (ref "Q153") (pin "S") (pinfunction "S_S") (pintype "passive"))
      (node (ref "Q154") (pin "S") (pinfunction "S_S") (pintype "passive"))
      (node (ref "Q155") (pin "S") (pinfunction "S_S") (pintype "passive"))
      (node (ref "Q156") (pin "S") (pinfunction "S_S") (pintype "passive"))
      (node (ref "Q157") (pin "S") (pinfunction "S_S") (pintype "passive"))
      (node (ref "Q158") (pin "S") (pinfunction "S_S") (pintype "passive"))
      (node (ref "Q159") (pin "S") (pinfunction "S_S") (pintype "passive"))
      (node (ref "Q160") (pin "S") (pinfunction "S_S") (pintype "passive"))
      (node (ref "Q161") (pin "S") (pinfunction "S_S") (pintype "passive"))
      (node (ref "Q162") (pin "S") (pinfunction "S_S") (pintype "passive"))
      (node (ref "Q163") (pin "S") (pinfunction "S_S") (pintype "passive"))
      (node (ref "Q164") (pin "S") (pinfunction "S_S") (pintype "passive"))
      (node (ref "Q165") (pin "S") (pinfunction "S_S") (pintype "passive"))
      (node (ref "Q166") (pin "S") (pinfunction "S_S") (pintype "passive"))
      (node (ref "Q167") (pin "S") (pinfunction "S_S") (pintype "passive"))
      (node (ref "Q168") (pin "S") (pinfunction "S_S") (pintype "passive"))
      (node (ref "Q17") (pin "S") (pinfunction "S_S") (pintype "passive"))
      (node (ref "Q170") (pin "S") (pinfunction "S_S") (pintype "passive"))
      (node (ref "Q173") (pin "S") (pinfunction "S_S") (pintype "passive"))
      (node (ref "Q175") (pin "S") (pinfunction "S_S") (pintype "passive"))
      (node (ref "Q178") (pin "S") (pinfunction "S_S") (pintype "passive"))
      (node (ref "Q18") (pin "S") (pinfunction "S_S") (pintype "passive"))
      (node (ref "Q180") (pin "S") (pinfunction "S_S") (pintype "passive"))
      (node (ref "Q183") (pin "S") (pinfunction "S_S") (pintype "passive"))
      (node (ref "Q185") (pin "S") (pinfunction "S_S") (pintype "passive"))
      (node (ref "Q188") (pin "S") (pinfunction "S_S") (pintype "passive"))
      (node (ref "Q19") (pin "S") (pinfunction "S_S") (pintype "passive"))
      (node (ref "Q190") (pin "S") (pinfunction "S_S") (pintype "passive"))
      (node (ref "Q193") (pin "S") (pinfunction "S_S") (pintype "passive"))
      (node (ref "Q195") (pin "S") (pinfunction "S_S") (pintype "passive"))
      (node (ref "Q198") (pin "S") (pinfunction "S_S") (pintype "passive"))
      (node (ref "Q20") (pin "S") (pinfunction "S_S") (pintype "passive"))
      (node (ref "Q200") (pin "S") (pinfunction "S_S") (pintype "passive"))
      (node (ref "Q203") (pin "S") (pinfunction "S_S") (pintype "passive"))
      (node (ref "Q205") (pin "S") (pinfunction "S_S") (pintype "passive"))
      (node (ref "Q208") (pin "S") (pinfunction "S_S") (pintype "passive"))
      (node (ref "Q209") (pin "S") (pinfunction "S_S") (pintype "passive"))
      (node (ref "Q21") (pin "S") (pinfunction "S_S") (pintype "passive"))
      (node (ref "Q210") (pin "S") (pinfunction "S_S") (pintype "passive"))
      (node (ref "Q211") (pin "S") (pinfunction "S_S") (pintype "passive"))
      (node (ref "Q212") (pin "S") (pinfunction "S_S") (pintype "passive"))
      (node (ref "Q213") (pin "S") (pinfunction "S_S") (pintype "passive"))
      (node (ref "Q214") (pin "S") (pinfunction "S_S") (pintype "passive"))
      (node (ref "Q215") (pin "S") (pinfunction "S_S") (pintype "passive"))
      (node (ref "Q216") (pin "S") (pinfunction "S_S") (pintype "passive"))
      (node (ref "Q217") (pin "S") (pinfunction "S_S") (pintype "passive"))
      (node (ref "Q218") (pin "S") (pinfunction "S_S") (pintype "passive"))
      (node (ref "Q219") (pin "S") (pinfunction "S_S") (pintype "passive"))
      (node (ref "Q22") (pin "S") (pinfunction "S_S") (pintype "passive"))
      (node (ref "Q220") (pin "S") (pinfunction "S_S") (pintype "passive"))
      (node (ref "Q221") (pin "S") (pinfunction "S_S") (pintype "passive"))
      (node (ref "Q222") (pin "S") (pinfunction "S_S") (pintype "passive"))
      (node (ref "Q223") (pin "S") (pinfunction "S_S") (pintype "passive"))
      (node (ref "Q224") (pin "S") (pinfunction "S_S") (pintype "passive"))
      (node (ref "Q225") (pin "S") (pinfunction "S_S") (pintype "passive"))
      (node (ref "Q226") (pin "S") (pinfunction "S_S") (pintype "passive"))
      (node (ref "Q227") (pin "S") (pinfunction "S_S") (pintype "passive"))
      (node (ref "Q228") (pin "S") (pinfunction "S_S") (pintype "passive"))
      (node (ref "Q229") (pin "S") (pinfunction "S_S") (pintype "passive"))
      (node (ref "Q23") (pin "S") (pinfunction "S_S") (pintype "passive"))
      (node (ref "Q230") (pin "S") (pinfunction "S_S") (pintype "passive"))
      (node (ref "Q231") (pin "S") (pinfunction "S_S") (pintype "passive"))
      (node (ref "Q232") (pin "S") (pinfunction "S_S") (pintype "passive"))
      (node (ref "Q233") (pin "S") (pinfunction "S_S") (pintype "passive"))
      (node (ref "Q234") (pin "S") (pinfunction "S_S") (pintype "passive"))
      (node (ref "Q235") (pin "S") (pinfunction "S_S") (pintype "passive"))
      (node (ref "Q236") (pin "S") (pinfunction "S_S") (pintype "passive"))
      (node (ref "Q239") (pin "S") (pinfunction "S_S") (pintype "passive"))
      (node (ref "Q24") (pin "S") (pinfunction "S_S") (pintype "passive"))
      (node (ref "Q240") (pin "S") (pinfunction "S_S") (pintype "passive"))
      (node (ref "Q243") (pin "S") (pinfunction "S_S") (pintype "passive"))
      (node (ref "Q244") (pin "S") (pinfunction "S_S") (pintype "passive"))
      (node (ref "Q247") (pin "S") (pinfunction "S_S") (pintype "passive"))
      (node (ref "Q248") (pin "S") (pinfunction "S_S") (pintype "passive"))
      (node (ref "Q25") (pin "S") (pinfunction "S_S") (pintype "passive"))
      (node (ref "Q251") (pin "S") (pinfunction "S_S") (pintype "passive"))
      (node (ref "Q252") (pin "S") (pinfunction "S_S") (pintype "passive"))
      (node (ref "Q26") (pin "S") (pinfunction "S_S") (pintype "passive"))
      (node (ref "Q27") (pin "S") (pinfunction "S_S") (pintype "passive"))
      (node (ref "Q28") (pin "S") (pinfunction "S_S") (pintype "passive"))
      (node (ref "Q29") (pin "S") (pinfunction "S_S") (pintype "passive"))
      (node (ref "Q3") (pin "S") (pinfunction "S_S") (pintype "passive"))
      (node (ref "Q30") (pin "S") (pinfunction "S_S") (pintype "passive"))
      (node (ref "Q31") (pin "S") (pinfunction "S_S") (pintype "passive"))
      (node (ref "Q32") (pin "S") (pinfunction "S_S") (pintype "passive"))
      (node (ref "Q33") (pin "S") (pinfunction "S_S") (pintype "passive"))
      (node (ref "Q34") (pin "S") (pinfunction "S_S") (pintype "passive"))
      (node (ref "Q35") (pin "S") (pinfunction "S_S") (pintype "passive"))
      (node (ref "Q36") (pin "S") (pinfunction "S_S") (pintype "passive"))
      (node (ref "Q37") (pin "S") (pinfunction "S_S") (pintype "passive"))
      (node (ref "Q38") (pin "S") (pinfunction "S_S") (pintype "passive"))
      (node (ref "Q39") (pin "S") (pinfunction "S_S") (pintype "passive"))
      (node (ref "Q40") (pin "S") (pinfunction "S_S") (pintype "passive"))
      (node (ref "Q41") (pin "S") (pinfunction "S_S") (pintype "passive"))
      (node (ref "Q42") (pin "S") (pinfunction "S_S") (pintype "passive"))
      (node (ref "Q43") (pin "S") (pinfunction "S_S") (pintype "passive"))
      (node (ref "Q45") (pin "S") (pinfunction "S_S") (pintype "passive"))
      (node (ref "Q47") (pin "S") (pinfunction "S_S") (pintype "passive"))
      (node (ref "Q49") (pin "S") (pinfunction "S_S") (pintype "passive"))
      (node (ref "Q5") (pin "S") (pinfunction "S_S") (pintype "passive"))
      (node (ref "Q51") (pin "S") (pinfunction "S_S") (pintype "passive"))
      (node (ref "Q53") (pin "S") (pinfunction "S_S") (pintype "passive"))
      (node (ref "Q55") (pin "S") (pinfunction "S_S") (pintype "passive"))
      (node (ref "Q57") (pin "S") (pinfunction "S_S") (pintype "passive"))
      (node (ref "Q59") (pin "S") (pinfunction "S_S") (pintype "passive"))
      (node (ref "Q60") (pin "S") (pinfunction "S_S") (pintype "passive"))
      (node (ref "Q61") (pin "S") (pinfunction "S_S") (pintype "passive"))
      (node (ref "Q62") (pin "S") (pinfunction "S_S") (pintype "passive"))
      (node (ref "Q63") (pin "S") (pinfunction "S_S") (pintype "passive"))
      (node (ref "Q64") (pin "S") (pinfunction "S_S") (pintype "passive"))
      (node (ref "Q65") (pin "S") (pinfunction "S_S") (pintype "passive"))
      (node (ref "Q66") (pin "S") (pinfunction "S_S") (pintype "passive"))
      (node (ref "Q67") (pin "S") (pinfunction "S_S") (pintype "passive"))
      (node (ref "Q68") (pin "S") (pinfunction "S_S") (pintype "passive"))
      (node (ref "Q69") (pin "S") (pinfunction "S_S") (pintype "passive"))
      (node (ref "Q7") (pin "S") (pinfunction "S_S") (pintype "passive"))
      (node (ref "Q70") (pin "S") (pinfunction "S_S") (pintype "passive"))
      (node (ref "Q71") (pin "S") (pinfunction "S_S") (pintype "passive"))
      (node (ref "Q72") (pin "S") (pinfunction "S_S") (pintype "passive"))
      (node (ref "Q73") (pin "S") (pinfunction "S_S") (pintype "passive"))
      (node (ref "Q74") (pin "S") (pinfunction "S_S") (pintype "passive"))
      (node (ref "Q75") (pin "S") (pinfunction "S_S") (pintype "passive"))
      (node (ref "Q76") (pin "S") (pinfunction "S_S") (pintype "passive"))
      (node (ref "Q77") (pin "S") (pinfunction "S_S") (pintype "passive"))
      (node (ref "Q78") (pin "S") (pinfunction "S_S") (pintype "passive"))
      (node (ref "Q79") (pin "S") (pinfunction "S_S") (pintype "passive"))
      (node (ref "Q80") (pin "S") (pinfunction "S_S") (pintype "passive"))
      (node (ref "Q81") (pin "S") (pinfunction "S_S") (pintype "passive"))
      (node (ref "Q82") (pin "S") (pinfunction "S_S") (pintype "passive"))
      (node (ref "Q83") (pin "S") (pinfunction "S_S") (pintype "passive"))
      (node (ref "Q84") (pin "S") (pinfunction "S_S") (pintype "passive"))
      (node (ref "Q85") (pin "S") (pinfunction "S_S") (pintype "passive"))
      (node (ref "Q87") (pin "S") (pinfunction "S_S") (pintype "passive"))
      (node (ref "Q89") (pin "S") (pinfunction "S_S") (pintype "passive"))
      (node (ref "Q9") (pin "S") (pinfunction "S_S") (pintype "passive"))
      (node (ref "Q91") (pin "S") (pinfunction "S_S") (pintype "passive"))
      (node (ref "Q93") (pin "S") (pinfunction "S_S") (pintype "passive"))
      (node (ref "Q95") (pin "S") (pinfunction "S_S") (pintype "passive"))
      (node (ref "Q97") (pin "S") (pinfunction "S_S") (pintype "passive"))
      (node (ref "Q99") (pin "S") (pinfunction "S_S") (pintype "passive"))
      (node (ref "TP6") (pin "1") (pinfunction "P$1_1") (pintype "bidirectional"))
    )
    (net (code "41") (name "Net-(D1-C)") (class "Default")
      (node (ref "D1") (pin "K") (pinfunction "C_K") (pintype "passive"))
      (node (ref "R2") (pin "2") (pinfunction "2_2") (pintype "passive"))
    )
    (net (code "42") (name "Net-(D2-C)") (class "Default")
      (node (ref "D2") (pin "K") (pinfunction "C_K") (pintype "passive"))
      (node (ref "R4") (pin "2") (pinfunction "2_2") (pintype "passive"))
    )
    (net (code "43") (name "Net-(D3-C)") (class "Default")
      (node (ref "D3") (pin "K") (pinfunction "C_K") (pintype "passive"))
      (node (ref "R6") (pin "2") (pinfunction "2_2") (pintype "passive"))
    )
    (net (code "44") (name "Net-(D4-C)") (class "Default")
      (node (ref "D4") (pin "K") (pinfunction "C_K") (pintype "passive"))
      (node (ref "R8") (pin "2") (pinfunction "2_2") (pintype "passive"))
    )
    (net (code "45") (name "Net-(D5-C)") (class "Default")
      (node (ref "D5") (pin "K") (pinfunction "C_K") (pintype "passive"))
      (node (ref "R10") (pin "2") (pinfunction "2_2") (pintype "passive"))
    )
    (net (code "46") (name "Net-(D6-C)") (class "Default")
      (node (ref "D6") (pin "K") (pinfunction "C_K") (pintype "passive"))
      (node (ref "R12") (pin "2") (pinfunction "2_2") (pintype "passive"))
    )
    (net (code "47") (name "Net-(D7-C)") (class "Default")
      (node (ref "D7") (pin "K") (pinfunction "C_K") (pintype "passive"))
      (node (ref "R14") (pin "2") (pinfunction "2_2") (pintype "passive"))
    )
    (net (code "48") (name "Net-(D8-C)") (class "Default")
      (node (ref "D8") (pin "K") (pinfunction "C_K") (pintype "passive"))
      (node (ref "R16") (pin "2") (pinfunction "2_2") (pintype "passive"))
    )
    (net (code "49") (name "Net-(D9-C)") (class "Default")
      (node (ref "D9") (pin "K") (pinfunction "C_K") (pintype "passive"))
      (node (ref "R52") (pin "2") (pinfunction "2_2") (pintype "passive"))
    )
    (net (code "50") (name "Net-(D10-C)") (class "Default")
      (node (ref "D10") (pin "K") (pinfunction "C_K") (pintype "passive"))
      (node (ref "R54") (pin "2") (pinfunction "2_2") (pintype "passive"))
    )
    (net (code "51") (name "Net-(D11-C)") (class "Default")
      (node (ref "D11") (pin "K") (pinfunction "C_K") (pintype "passive"))
      (node (ref "R56") (pin "2") (pinfunction "2_2") (pintype "passive"))
    )
    (net (code "52") (name "Net-(D12-C)") (class "Default")
      (node (ref "D12") (pin "K") (pinfunction "C_K") (pintype "passive"))
      (node (ref "R58") (pin "2") (pinfunction "2_2") (pintype "passive"))
    )
    (net (code "53") (name "Net-(D13-C)") (class "Default")
      (node (ref "D13") (pin "K") (pinfunction "C_K") (pintype "passive"))
      (node (ref "R60") (pin "2") (pinfunction "2_2") (pintype "passive"))
    )
    (net (code "54") (name "Net-(D14-C)") (class "Default")
      (node (ref "D14") (pin "K") (pinfunction "C_K") (pintype "passive"))
      (node (ref "R62") (pin "2") (pinfunction "2_2") (pintype "passive"))
    )
    (net (code "55") (name "Net-(D15-C)") (class "Default")
      (node (ref "D15") (pin "K") (pinfunction "C_K") (pintype "passive"))
      (node (ref "R64") (pin "2") (pinfunction "2_2") (pintype "passive"))
    )
    (net (code "56") (name "Net-(D16-C)") (class "Default")
      (node (ref "D16") (pin "K") (pinfunction "C_K") (pintype "passive"))
      (node (ref "R66") (pin "2") (pinfunction "2_2") (pintype "passive"))
    )
    (net (code "57") (name "Net-(D17-C)") (class "Default")
      (node (ref "D17") (pin "K") (pinfunction "C_K") (pintype "passive"))
      (node (ref "R102") (pin "2") (pinfunction "2_2") (pintype "passive"))
    )
    (net (code "58") (name "Net-(D18-C)") (class "Default")
      (node (ref "D18") (pin "K") (pinfunction "C_K") (pintype "passive"))
      (node (ref "R104") (pin "2") (pinfunction "2_2") (pintype "passive"))
    )
    (net (code "59") (name "Net-(D19-C)") (class "Default")
      (node (ref "D19") (pin "K") (pinfunction "C_K") (pintype "passive"))
      (node (ref "R106") (pin "2") (pinfunction "2_2") (pintype "passive"))
    )
    (net (code "60") (name "Net-(D20-C)") (class "Default")
      (node (ref "D20") (pin "K") (pinfunction "C_K") (pintype "passive"))
      (node (ref "R108") (pin "2") (pinfunction "2_2") (pintype "passive"))
    )
    (net (code "61") (name "Net-(D21-C)") (class "Default")
      (node (ref "D21") (pin "K") (pinfunction "C_K") (pintype "passive"))
      (node (ref "R110") (pin "2") (pinfunction "2_2") (pintype "passive"))
    )
    (net (code "62") (name "Net-(D22-C)") (class "Default")
      (node (ref "D22") (pin "K") (pinfunction "C_K") (pintype "passive"))
      (node (ref "R112") (pin "2") (pinfunction "2_2") (pintype "passive"))
    )
    (net (code "63") (name "Net-(D23-C)") (class "Default")
      (node (ref "D23") (pin "K") (pinfunction "C_K") (pintype "passive"))
      (node (ref "R114") (pin "2") (pinfunction "2_2") (pintype "passive"))
    )
    (net (code "64") (name "Net-(D24-C)") (class "Default")
      (node (ref "D24") (pin "K") (pinfunction "C_K") (pintype "passive"))
      (node (ref "R116") (pin "2") (pinfunction "2_2") (pintype "passive"))
    )
    (net (code "65") (name "Net-(D25-C)") (class "Default")
      (node (ref "D25") (pin "K") (pinfunction "C_K") (pintype "passive"))
      (node (ref "R152") (pin "2") (pinfunction "2_2") (pintype "passive"))
    )
    (net (code "66") (name "Net-(D26-C)") (class "Default")
      (node (ref "D26") (pin "K") (pinfunction "C_K") (pintype "passive"))
      (node (ref "R154") (pin "2") (pinfunction "2_2") (pintype "passive"))
    )
    (net (code "67") (name "Net-(D27-C)") (class "Default")
      (node (ref "D27") (pin "K") (pinfunction "C_K") (pintype "passive"))
      (node (ref "R156") (pin "2") (pinfunction "2_2") (pintype "passive"))
    )
    (net (code "68") (name "Net-(D28-C)") (class "Default")
      (node (ref "D28") (pin "K") (pinfunction "C_K") (pintype "passive"))
      (node (ref "R158") (pin "2") (pinfunction "2_2") (pintype "passive"))
    )
    (net (code "69") (name "Net-(D29-C)") (class "Default")
      (node (ref "D29") (pin "K") (pinfunction "C_K") (pintype "passive"))
      (node (ref "R160") (pin "2") (pinfunction "2_2") (pintype "passive"))
    )
    (net (code "70") (name "Net-(D30-C)") (class "Default")
      (node (ref "D30") (pin "K") (pinfunction "C_K") (pintype "passive"))
      (node (ref "R162") (pin "2") (pinfunction "2_2") (pintype "passive"))
    )
    (net (code "71") (name "Net-(D31-C)") (class "Default")
      (node (ref "D31") (pin "K") (pinfunction "C_K") (pintype "passive"))
      (node (ref "R164") (pin "2") (pinfunction "2_2") (pintype "passive"))
    )
    (net (code "72") (name "Net-(D32-C)") (class "Default")
      (node (ref "D32") (pin "K") (pinfunction "C_K") (pintype "passive"))
      (node (ref "R166") (pin "2") (pinfunction "2_2") (pintype "passive"))
    )
    (net (code "73") (name "Net-(D33-C)") (class "Default")
      (node (ref "D33") (pin "K") (pinfunction "C_K") (pintype "passive"))
      (node (ref "R204") (pin "2") (pinfunction "2_2") (pintype "passive"))
    )
    (net (code "74") (name "Net-(D34-C)") (class "Default")
      (node (ref "D34") (pin "K") (pinfunction "C_K") (pintype "passive"))
      (node (ref "R206") (pin "2") (pinfunction "2_2") (pintype "passive"))
    )
    (net (code "75") (name "Net-(D35-C)") (class "Default")
      (node (ref "D35") (pin "K") (pinfunction "C_K") (pintype "passive"))
      (node (ref "R208") (pin "2") (pinfunction "2_2") (pintype "passive"))
    )
    (net (code "76") (name "Net-(D36-C)") (class "Default")
      (node (ref "D36") (pin "K") (pinfunction "C_K") (pintype "passive"))
      (node (ref "R210") (pin "2") (pinfunction "2_2") (pintype "passive"))
    )
    (net (code "77") (name "Net-(D37-C)") (class "Default")
      (node (ref "D37") (pin "K") (pinfunction "C_K") (pintype "passive"))
      (node (ref "R212") (pin "2") (pinfunction "2_2") (pintype "passive"))
    )
    (net (code "78") (name "Net-(D38-C)") (class "Default")
      (node (ref "D38") (pin "K") (pinfunction "C_K") (pintype "passive"))
      (node (ref "R214") (pin "2") (pinfunction "2_2") (pintype "passive"))
    )
    (net (code "79") (name "Net-(D39-C)") (class "Default")
      (node (ref "D39") (pin "K") (pinfunction "C_K") (pintype "passive"))
      (node (ref "R216") (pin "2") (pinfunction "2_2") (pintype "passive"))
    )
    (net (code "80") (name "Net-(D69-C)") (class "Default")
      (node (ref "D69") (pin "K") (pinfunction "C_K") (pintype "passive"))
      (node (ref "R202") (pin "2") (pinfunction "2_2") (pintype "passive"))
    )
    (net (code "81") (name "Net-(Q1-PadD)") (class "Default")
      (node (ref "Q1") (pin "D") (pinfunction "D_D") (pintype "passive"))
      (node (ref "Q2") (pin "G") (pinfunction "G_G") (pintype "passive"))
      (node (ref "R1") (pin "1") (pinfunction "1_1") (pintype "passive"))
      (node (ref "R2") (pin "1") (pinfunction "1_1") (pintype "passive"))
    )
    (net (code "82") (name "Net-(Q3-PadD)") (class "Default")
      (node (ref "Q3") (pin "D") (pinfunction "D_D") (pintype "passive"))
      (node (ref "Q4") (pin "G") (pinfunction "G_G") (pintype "passive"))
      (node (ref "R3") (pin "1") (pinfunction "1_1") (pintype "passive"))
      (node (ref "R4") (pin "1") (pinfunction "1_1") (pintype "passive"))
    )
    (net (code "83") (name "Net-(Q5-PadD)") (class "Default")
      (node (ref "Q5") (pin "D") (pinfunction "D_D") (pintype "passive"))
      (node (ref "Q6") (pin "G") (pinfunction "G_G") (pintype "passive"))
      (node (ref "R5") (pin "1") (pinfunction "1_1") (pintype "passive"))
      (node (ref "R6") (pin "1") (pinfunction "1_1") (pintype "passive"))
    )
    (net (code "84") (name "Net-(Q7-PadD)") (class "Default")
      (node (ref "Q7") (pin "D") (pinfunction "D_D") (pintype "passive"))
      (node (ref "Q8") (pin "G") (pinfunction "G_G") (pintype "passive"))
      (node (ref "R7") (pin "1") (pinfunction "1_1") (pintype "passive"))
      (node (ref "R8") (pin "1") (pinfunction "1_1") (pintype "passive"))
    )
    (net (code "85") (name "Net-(Q10-PadG)") (class "Default")
      (node (ref "Q10") (pin "G") (pinfunction "G_G") (pintype "passive"))
      (node (ref "Q9") (pin "D") (pinfunction "D_D") (pintype "passive"))
      (node (ref "R10") (pin "1") (pinfunction "1_1") (pintype "passive"))
      (node (ref "R9") (pin "1") (pinfunction "1_1") (pintype "passive"))
    )
    (net (code "86") (name "Net-(Q11-PadD)") (class "Default")
      (node (ref "Q11") (pin "D") (pinfunction "D_D") (pintype "passive"))
      (node (ref "Q12") (pin "G") (pinfunction "G_G") (pintype "passive"))
      (node (ref "R11") (pin "1") (pinfunction "1_1") (pintype "passive"))
      (node (ref "R12") (pin "1") (pinfunction "1_1") (pintype "passive"))
    )
    (net (code "87") (name "Net-(Q13-PadD)") (class "Default")
      (node (ref "Q13") (pin "D") (pinfunction "D_D") (pintype "passive"))
      (node (ref "Q14") (pin "G") (pinfunction "G_G") (pintype "passive"))
      (node (ref "R13") (pin "1") (pinfunction "1_1") (pintype "passive"))
      (node (ref "R14") (pin "1") (pinfunction "1_1") (pintype "passive"))
    )
    (net (code "88") (name "Net-(Q15-PadD)") (class "Default")
      (node (ref "Q15") (pin "D") (pinfunction "D_D") (pintype "passive"))
      (node (ref "Q16") (pin "G") (pinfunction "G_G") (pintype "passive"))
      (node (ref "R15") (pin "1") (pinfunction "1_1") (pintype "passive"))
      (node (ref "R16") (pin "1") (pinfunction "1_1") (pintype "passive"))
    )
    (net (code "89") (name "Net-(Q43-PadD)") (class "Default")
      (node (ref "Q43") (pin "D") (pinfunction "D_D") (pintype "passive"))
      (node (ref "Q44") (pin "G") (pinfunction "G_G") (pintype "passive"))
      (node (ref "R51") (pin "1") (pinfunction "1_1") (pintype "passive"))
      (node (ref "R52") (pin "1") (pinfunction "1_1") (pintype "passive"))
    )
    (net (code "90") (name "Net-(Q45-PadD)") (class "Default")
      (node (ref "Q45") (pin "D") (pinfunction "D_D") (pintype "passive"))
      (node (ref "Q46") (pin "G") (pinfunction "G_G") (pintype "passive"))
      (node (ref "R53") (pin "1") (pinfunction "1_1") (pintype "passive"))
      (node (ref "R54") (pin "1") (pinfunction "1_1") (pintype "passive"))
    )
    (net (code "91") (name "Net-(Q47-PadD)") (class "Default")
      (node (ref "Q47") (pin "D") (pinfunction "D_D") (pintype "passive"))
      (node (ref "Q48") (pin "G") (pinfunction "G_G") (pintype "passive"))
      (node (ref "R55") (pin "1") (pinfunction "1_1") (pintype "passive"))
      (node (ref "R56") (pin "1") (pinfunction "1_1") (pintype "passive"))
    )
    (net (code "92") (name "Net-(Q49-PadD)") (class "Default")
      (node (ref "Q49") (pin "D") (pinfunction "D_D") (pintype "passive"))
      (node (ref "Q50") (pin "G") (pinfunction "G_G") (pintype "passive"))
      (node (ref "R57") (pin "1") (pinfunction "1_1") (pintype "passive"))
      (node (ref "R58") (pin "1") (pinfunction "1_1") (pintype "passive"))
    )
    (net (code "93") (name "Net-(Q51-PadD)") (class "Default")
      (node (ref "Q51") (pin "D") (pinfunction "D_D") (pintype "passive"))
      (node (ref "Q52") (pin "G") (pinfunction "G_G") (pintype "passive"))
      (node (ref "R59") (pin "1") (pinfunction "1_1") (pintype "passive"))
      (node (ref "R60") (pin "1") (pinfunction "1_1") (pintype "passive"))
    )
    (net (code "94") (name "Net-(Q53-PadD)") (class "Default")
      (node (ref "Q53") (pin "D") (pinfunction "D_D") (pintype "passive"))
      (node (ref "Q54") (pin "G") (pinfunction "G_G") (pintype "passive"))
      (node (ref "R61") (pin "1") (pinfunction "1_1") (pintype "passive"))
      (node (ref "R62") (pin "1") (pinfunction "1_1") (pintype "passive"))
    )
    (net (code "95") (name "Net-(Q55-PadD)") (class "Default")
      (node (ref "Q55") (pin "D") (pinfunction "D_D") (pintype "passive"))
      (node (ref "Q56") (pin "G") (pinfunction "G_G") (pintype "passive"))
      (node (ref "R63") (pin "1") (pinfunction "1_1") (pintype "passive"))
      (node (ref "R64") (pin "1") (pinfunction "1_1") (pintype "passive"))
    )
    (net (code "96") (name "Net-(Q57-PadD)") (class "Default")
      (node (ref "Q57") (pin "D") (pinfunction "D_D") (pintype "passive"))
      (node (ref "Q58") (pin "G") (pinfunction "G_G") (pintype "passive"))
      (node (ref "R65") (pin "1") (pinfunction "1_1") (pintype "passive"))
      (node (ref "R66") (pin "1") (pinfunction "1_1") (pintype "passive"))
    )
    (net (code "97") (name "Net-(Q85-PadD)") (class "Default")
      (node (ref "Q85") (pin "D") (pinfunction "D_D") (pintype "passive"))
      (node (ref "Q86") (pin "G") (pinfunction "G_G") (pintype "passive"))
      (node (ref "R101") (pin "1") (pinfunction "1_1") (pintype "passive"))
      (node (ref "R102") (pin "1") (pinfunction "1_1") (pintype "passive"))
    )
    (net (code "98") (name "Net-(Q87-PadD)") (class "Default")
      (node (ref "Q87") (pin "D") (pinfunction "D_D") (pintype "passive"))
      (node (ref "Q88") (pin "G") (pinfunction "G_G") (pintype "passive"))
      (node (ref "R103") (pin "1") (pinfunction "1_1") (pintype "passive"))
      (node (ref "R104") (pin "1") (pinfunction "1_1") (pintype "passive"))
    )
    (net (code "99") (name "Net-(Q89-PadD)") (class "Default")
      (node (ref "Q89") (pin "D") (pinfunction "D_D") (pintype "passive"))
      (node (ref "Q90") (pin "G") (pinfunction "G_G") (pintype "passive"))
      (node (ref "R105") (pin "1") (pinfunction "1_1") (pintype "passive"))
      (node (ref "R106") (pin "1") (pinfunction "1_1") (pintype "passive"))
    )
    (net (code "100") (name "Net-(Q91-PadD)") (class "Default")
      (node (ref "Q91") (pin "D") (pinfunction "D_D") (pintype "passive"))
      (node (ref "Q92") (pin "G") (pinfunction "G_G") (pintype "passive"))
      (node (ref "R107") (pin "1") (pinfunction "1_1") (pintype "passive"))
      (node (ref "R108") (pin "1") (pinfunction "1_1") (pintype "passive"))
    )
    (net (code "101") (name "Net-(Q93-PadD)") (class "Default")
      (node (ref "Q93") (pin "D") (pinfunction "D_D") (pintype "passive"))
      (node (ref "Q94") (pin "G") (pinfunction "G_G") (pintype "passive"))
      (node (ref "R109") (pin "1") (pinfunction "1_1") (pintype "passive"))
      (node (ref "R110") (pin "1") (pinfunction "1_1") (pintype "passive"))
    )
    (net (code "102") (name "Net-(Q95-PadD)") (class "Default")
      (node (ref "Q95") (pin "D") (pinfunction "D_D") (pintype "passive"))
      (node (ref "Q96") (pin "G") (pinfunction "G_G") (pintype "passive"))
      (node (ref "R111") (pin "1") (pinfunction "1_1") (pintype "passive"))
      (node (ref "R112") (pin "1") (pinfunction "1_1") (pintype "passive"))
    )
    (net (code "103") (name "Net-(Q97-PadD)") (class "Default")
      (node (ref "Q97") (pin "D") (pinfunction "D_D") (pintype "passive"))
      (node (ref "Q98") (pin "G") (pinfunction "G_G") (pintype "passive"))
      (node (ref "R113") (pin "1") (pinfunction "1_1") (pintype "passive"))
      (node (ref "R114") (pin "1") (pinfunction "1_1") (pintype "passive"))
    )
    (net (code "104") (name "Net-(Q100-PadG)") (class "Default")
      (node (ref "Q100") (pin "G") (pinfunction "G_G") (pintype "passive"))
      (node (ref "Q99") (pin "D") (pinfunction "D_D") (pintype "passive"))
      (node (ref "R115") (pin "1") (pinfunction "1_1") (pintype "passive"))
      (node (ref "R116") (pin "1") (pinfunction "1_1") (pintype "passive"))
    )
    (net (code "105") (name "Net-(Q127-PadD)") (class "Default")
      (node (ref "Q127") (pin "D") (pinfunction "D_D") (pintype "passive"))
      (node (ref "Q128") (pin "G") (pinfunction "G_G") (pintype "passive"))
      (node (ref "R151") (pin "1") (pinfunction "1_1") (pintype "passive"))
      (node (ref "R152") (pin "1") (pinfunction "1_1") (pintype "passive"))
    )
    (net (code "106") (name "Net-(Q129-PadD)") (class "Default")
      (node (ref "Q129") (pin "D") (pinfunction "D_D") (pintype "passive"))
      (node (ref "Q130") (pin "G") (pinfunction "G_G") (pintype "passive"))
      (node (ref "R153") (pin "1") (pinfunction "1_1") (pintype "passive"))
      (node (ref "R154") (pin "1") (pinfunction "1_1") (pintype "passive"))
    )
    (net (code "107") (name "Net-(Q131-PadD)") (class "Default")
      (node (ref "Q131") (pin "D") (pinfunction "D_D") (pintype "passive"))
      (node (ref "Q132") (pin "G") (pinfunction "G_G") (pintype "passive"))
      (node (ref "R155") (pin "1") (pinfunction "1_1") (pintype "passive"))
      (node (ref "R156") (pin "1") (pinfunction "1_1") (pintype "passive"))
    )
    (net (code "108") (name "Net-(Q133-PadD)") (class "Default")
      (node (ref "Q133") (pin "D") (pinfunction "D_D") (pintype "passive"))
      (node (ref "Q134") (pin "G") (pinfunction "G_G") (pintype "passive"))
      (node (ref "R157") (pin "1") (pinfunction "1_1") (pintype "passive"))
      (node (ref "R158") (pin "1") (pinfunction "1_1") (pintype "passive"))
    )
    (net (code "109") (name "Net-(Q135-PadD)") (class "Default")
      (node (ref "Q135") (pin "D") (pinfunction "D_D") (pintype "passive"))
      (node (ref "Q136") (pin "G") (pinfunction "G_G") (pintype "passive"))
      (node (ref "R159") (pin "1") (pinfunction "1_1") (pintype "passive"))
      (node (ref "R160") (pin "1") (pinfunction "1_1") (pintype "passive"))
    )
    (net (code "110") (name "Net-(Q137-PadD)") (class "Default")
      (node (ref "Q137") (pin "D") (pinfunction "D_D") (pintype "passive"))
      (node (ref "Q138") (pin "G") (pinfunction "G_G") (pintype "passive"))
      (node (ref "R161") (pin "1") (pinfunction "1_1") (pintype "passive"))
      (node (ref "R162") (pin "1") (pinfunction "1_1") (pintype "passive"))
    )
    (net (code "111") (name "Net-(Q139-PadD)") (class "Default")
      (node (ref "Q139") (pin "D") (pinfunction "D_D") (pintype "passive"))
      (node (ref "Q140") (pin "G") (pinfunction "G_G") (pintype "passive"))
      (node (ref "R163") (pin "1") (pinfunction "1_1") (pintype "passive"))
      (node (ref "R164") (pin "1") (pinfunction "1_1") (pintype "passive"))
    )
    (net (code "112") (name "Net-(Q141-PadD)") (class "Default")
      (node (ref "Q141") (pin "D") (pinfunction "D_D") (pintype "passive"))
      (node (ref "Q142") (pin "G") (pinfunction "G_G") (pintype "passive"))
      (node (ref "R165") (pin "1") (pinfunction "1_1") (pintype "passive"))
      (node (ref "R166") (pin "1") (pinfunction "1_1") (pintype "passive"))
    )
    (net (code "113") (name "Net-(Q169-PadD)") (class "Default")
      (node (ref "Q169") (pin "D") (pinfunction "D_D") (pintype "passive"))
      (node (ref "Q170") (pin "G") (pinfunction "G_G") (pintype "passive"))
      (node (ref "R201") (pin "1") (pinfunction "1_1") (pintype "passive"))
      (node (ref "R202") (pin "1") (pinfunction "1_1") (pintype "passive"))
    )
    (net (code "114") (name "Net-(Q169-PadS)") (class "Default")
      (node (ref "Q169") (pin "S") (pinfunction "S_S") (pintype "passive"))
      (node (ref "Q171") (pin "D") (pinfunction "D_D") (pintype "passive"))
    )
    (net (code "115") (name "Net-(Q171-PadS)") (class "Default")
      (node (ref "Q171") (pin "S") (pinfunction "S_S") (pintype "passive"))
      (node (ref "Q172") (pin "D") (pinfunction "D_D") (pintype "passive"))
    )
    (net (code "116") (name "Net-(Q172-PadS)") (class "Default")
      (node (ref "Q172") (pin "S") (pinfunction "S_S") (pintype "passive"))
      (node (ref "Q173") (pin "D") (pinfunction "D_D") (pintype "passive"))
    )
    (net (code "117") (name "Net-(Q174-PadD)") (class "Default")
      (node (ref "Q174") (pin "D") (pinfunction "D_D") (pintype "passive"))
      (node (ref "Q175") (pin "G") (pinfunction "G_G") (pintype "passive"))
      (node (ref "R203") (pin "1") (pinfunction "1_1") (pintype "passive"))
      (node (ref "R204") (pin "1") (pinfunction "1_1") (pintype "passive"))
    )
    (net (code "118") (name "Net-(Q174-PadS)") (class "Default")
      (node (ref "Q174") (pin "S") (pinfunction "S_S") (pintype "passive"))
      (node (ref "Q176") (pin "D") (pinfunction "D_D") (pintype "passive"))
    )
    (net (code "119") (name "Net-(Q176-PadS)") (class "Default")
      (node (ref "Q176") (pin "S") (pinfunction "S_S") (pintype "passive"))
      (node (ref "Q177") (pin "D") (pinfunction "D_D") (pintype "passive"))
    )
    (net (code "120") (name "Net-(Q177-PadS)") (class "Default")
      (node (ref "Q177") (pin "S") (pinfunction "S_S") (pintype "passive"))
      (node (ref "Q178") (pin "D") (pinfunction "D_D") (pintype "passive"))
    )
    (net (code "121") (name "Net-(Q179-PadD)") (class "Default")
      (node (ref "Q179") (pin "D") (pinfunction "D_D") (pintype "passive"))
      (node (ref "Q180") (pin "G") (pinfunction "G_G") (pintype "passive"))
      (node (ref "R205") (pin "1") (pinfunction "1_1") (pintype "passive"))
      (node (ref "R206") (pin "1") (pinfunction "1_1") (pintype "passive"))
    )
    (net (code "122") (name "Net-(Q179-PadS)") (class "Default")
      (node (ref "Q179") (pin "S") (pinfunction "S_S") (pintype "passive"))
      (node (ref "Q181") (pin "D") (pinfunction "D_D") (pintype "passive"))
    )
    (net (code "123") (name "Net-(Q181-PadS)") (class "Default")
      (node (ref "Q181") (pin "S") (pinfunction "S_S") (pintype "passive"))
      (node (ref "Q182") (pin "D") (pinfunction "D_D") (pintype "passive"))
    )
    (net (code "124") (name "Net-(Q182-PadS)") (class "Default")
      (node (ref "Q182") (pin "S") (pinfunction "S_S") (pintype "passive"))
      (node (ref "Q183") (pin "D") (pinfunction "D_D") (pintype "passive"))
    )
    (net (code "125") (name "Net-(Q184-PadD)") (class "Default")
      (node (ref "Q184") (pin "D") (pinfunction "D_D") (pintype "passive"))
      (node (ref "Q185") (pin "G") (pinfunction "G_G") (pintype "passive"))
      (node (ref "R207") (pin "1") (pinfunction "1_1") (pintype "passive"))
      (node (ref "R208") (pin "1") (pinfunction "1_1") (pintype "passive"))
    )
    (net (code "126") (name "Net-(Q184-PadS)") (class "Default")
      (node (ref "Q184") (pin "S") (pinfunction "S_S") (pintype "passive"))
      (node (ref "Q186") (pin "D") (pinfunction "D_D") (pintype "passive"))
    )
    (net (code "127") (name "Net-(Q186-PadS)") (class "Default")
      (node (ref "Q186") (pin "S") (pinfunction "S_S") (pintype "passive"))
      (node (ref "Q187") (pin "D") (pinfunction "D_D") (pintype "passive"))
    )
    (net (code "128") (name "Net-(Q187-PadS)") (class "Default")
      (node (ref "Q187") (pin "S") (pinfunction "S_S") (pintype "passive"))
      (node (ref "Q188") (pin "D") (pinfunction "D_D") (pintype "passive"))
    )
    (net (code "129") (name "Net-(Q189-PadD)") (class "Default")
      (node (ref "Q189") (pin "D") (pinfunction "D_D") (pintype "passive"))
      (node (ref "Q190") (pin "G") (pinfunction "G_G") (pintype "passive"))
      (node (ref "R209") (pin "1") (pinfunction "1_1") (pintype "passive"))
      (node (ref "R210") (pin "1") (pinfunction "1_1") (pintype "passive"))
    )
    (net (code "130") (name "Net-(Q189-PadS)") (class "Default")
      (node (ref "Q189") (pin "S") (pinfunction "S_S") (pintype "passive"))
      (node (ref "Q191") (pin "D") (pinfunction "D_D") (pintype "passive"))
    )
    (net (code "131") (name "Net-(Q191-PadS)") (class "Default")
      (node (ref "Q191") (pin "S") (pinfunction "S_S") (pintype "passive"))
      (node (ref "Q192") (pin "D") (pinfunction "D_D") (pintype "passive"))
    )
    (net (code "132") (name "Net-(Q192-PadS)") (class "Default")
      (node (ref "Q192") (pin "S") (pinfunction "S_S") (pintype "passive"))
      (node (ref "Q193") (pin "D") (pinfunction "D_D") (pintype "passive"))
    )
    (net (code "133") (name "Net-(Q194-PadD)") (class "Default")
      (node (ref "Q194") (pin "D") (pinfunction "D_D") (pintype "passive"))
      (node (ref "Q195") (pin "G") (pinfunction "G_G") (pintype "passive"))
      (node (ref "R211") (pin "1") (pinfunction "1_1") (pintype "passive"))
      (node (ref "R212") (pin "1") (pinfunction "1_1") (pintype "passive"))
    )
    (net (code "134") (name "Net-(Q194-PadS)") (class "Default")
      (node (ref "Q194") (pin "S") (pinfunction "S_S") (pintype "passive"))
      (node (ref "Q196") (pin "D") (pinfunction "D_D") (pintype "passive"))
    )
    (net (code "135") (name "Net-(Q196-PadS)") (class "Default")
      (node (ref "Q196") (pin "S") (pinfunction "S_S") (pintype "passive"))
      (node (ref "Q197") (pin "D") (pinfunction "D_D") (pintype "passive"))
    )
    (net (code "136") (name "Net-(Q197-PadS)") (class "Default")
      (node (ref "Q197") (pin "S") (pinfunction "S_S") (pintype "passive"))
      (node (ref "Q198") (pin "D") (pinfunction "D_D") (pintype "passive"))
    )
    (net (code "137") (name "Net-(Q199-PadD)") (class "Default")
      (node (ref "Q199") (pin "D") (pinfunction "D_D") (pintype "passive"))
      (node (ref "Q200") (pin "G") (pinfunction "G_G") (pintype "passive"))
      (node (ref "R213") (pin "1") (pinfunction "1_1") (pintype "passive"))
      (node (ref "R214") (pin "1") (pinfunction "1_1") (pintype "passive"))
    )
    (net (code "138") (name "Net-(Q199-PadS)") (class "Default")
      (node (ref "Q199") (pin "S") (pinfunction "S_S") (pintype "passive"))
      (node (ref "Q201") (pin "D") (pinfunction "D_D") (pintype "passive"))
    )
    (net (code "139") (name "Net-(Q201-PadS)") (class "Default")
      (node (ref "Q201") (pin "S") (pinfunction "S_S") (pintype "passive"))
      (node (ref "Q202") (pin "D") (pinfunction "D_D") (pintype "passive"))
    )
    (net (code "140") (name "Net-(Q202-PadS)") (class "Default")
      (node (ref "Q202") (pin "S") (pinfunction "S_S") (pintype "passive"))
      (node (ref "Q203") (pin "D") (pinfunction "D_D") (pintype "passive"))
    )
    (net (code "141") (name "Net-(Q204-PadD)") (class "Default")
      (node (ref "Q204") (pin "D") (pinfunction "D_D") (pintype "passive"))
      (node (ref "Q205") (pin "G") (pinfunction "G_G") (pintype "passive"))
      (node (ref "R215") (pin "1") (pinfunction "1_1") (pintype "passive"))
      (node (ref "R216") (pin "1") (pinfunction "1_1") (pintype "passive"))
    )
    (net (code "142") (name "Net-(Q204-PadS)") (class "Default")
      (node (ref "Q204") (pin "S") (pinfunction "S_S") (pintype "passive"))
      (node (ref "Q206") (pin "D") (pinfunction "D_D") (pintype "passive"))
    )
    (net (code "143") (name "Net-(Q206-PadS)") (class "Default")
      (node (ref "Q206") (pin "S") (pinfunction "S_S") (pintype "passive"))
      (node (ref "Q207") (pin "D") (pinfunction "D_D") (pintype "passive"))
    )
    (net (code "144") (name "Net-(Q207-PadS)") (class "Default")
      (node (ref "Q207") (pin "S") (pinfunction "S_S") (pintype "passive"))
      (node (ref "Q208") (pin "D") (pinfunction "D_D") (pintype "passive"))
    )
    (net (code "145") (name "Net-(Q237-PadS)") (class "Default")
      (node (ref "Q237") (pin "S") (pinfunction "S_S") (pintype "passive"))
      (node (ref "Q238") (pin "D") (pinfunction "D_D") (pintype "passive"))
    )
    (net (code "146") (name "Net-(Q238-PadS)") (class "Default")
      (node (ref "Q238") (pin "S") (pinfunction "S_S") (pintype "passive"))
      (node (ref "Q239") (pin "D") (pinfunction "D_D") (pintype "passive"))
    )
    (net (code "147") (name "Net-(Q241-PadS)") (class "Default")
      (node (ref "Q241") (pin "S") (pinfunction "S_S") (pintype "passive"))
      (node (ref "Q242") (pin "D") (pinfunction "D_D") (pintype "passive"))
    )
    (net (code "148") (name "Net-(Q242-PadS)") (class "Default")
      (node (ref "Q242") (pin "S") (pinfunction "S_S") (pintype "passive"))
      (node (ref "Q243") (pin "D") (pinfunction "D_D") (pintype "passive"))
    )
    (net (code "149") (name "Net-(Q245-PadS)") (class "Default")
      (node (ref "Q245") (pin "S") (pinfunction "S_S") (pintype "passive"))
      (node (ref "Q246") (pin "D") (pinfunction "D_D") (pintype "passive"))
    )
    (net (code "150") (name "Net-(Q246-PadS)") (class "Default")
      (node (ref "Q246") (pin "S") (pinfunction "S_S") (pintype "passive"))
      (node (ref "Q247") (pin "D") (pinfunction "D_D") (pintype "passive"))
    )
    (net (code "151") (name "Net-(Q249-PadS)") (class "Default")
      (node (ref "Q249") (pin "S") (pinfunction "S_S") (pintype "passive"))
      (node (ref "Q250") (pin "D") (pinfunction "D_D") (pintype "passive"))
    )
    (net (code "152") (name "Net-(Q250-PadS)") (class "Default")
      (node (ref "Q250") (pin "S") (pinfunction "S_S") (pintype "passive"))
      (node (ref "Q251") (pin "D") (pinfunction "D_D") (pintype "passive"))
    )
    (net (code "153") (name "P0_A0") (class "Default")
      (node (ref "J2") (pin "5") (pinfunction "5_5") (pintype "bidirectional"))
      (node (ref "Q17") (pin "D") (pinfunction "D_D") (pintype "passive"))
      (node (ref "R25") (pin "1") (pinfunction "1_1") (pintype "passive"))
    )
    (net (code "154") (name "P0_A1") (class "Default")
      (node (ref "J2") (pin "6") (pinfunction "6_6") (pintype "bidirectional"))
      (node (ref "Q18") (pin "D") (pinfunction "D_D") (pintype "passive"))
      (node (ref "R26") (pin "1") (pinfunction "1_1") (pintype "passive"))
    )
    (net (code "155") (name "P0_A2") (class "Default")
      (node (ref "J2") (pin "7") (pinfunction "7_7") (pintype "bidirectional"))
      (node (ref "Q19") (pin "D") (pinfunction "D_D") (pintype "passive"))
      (node (ref "R27") (pin "1") (pinfunction "1_1") (pintype "passive"))
    )
    (net (code "156") (name "P0_A3") (class "Default")
      (node (ref "J2") (pin "8") (pinfunction "8_8") (pintype "bidirectional"))
      (node (ref "Q20") (pin "D") (pinfunction "D_D") (pintype "passive"))
      (node (ref "R28") (pin "1") (pinfunction "1_1") (pintype "passive"))
    )
    (net (code "157") (name "P0_A4") (class "Default")
      (node (ref "J2") (pin "9") (pinfunction "9_9") (pintype "bidirectional"))
      (node (ref "Q21") (pin "D") (pinfunction "D_D") (pintype "passive"))
      (node (ref "R29") (pin "1") (pinfunction "1_1") (pintype "passive"))
    )
    (net (code "158") (name "P0_A5") (class "Default")
      (node (ref "J2") (pin "10") (pinfunction "10_10") (pintype "bidirectional"))
      (node (ref "Q22") (pin "D") (pinfunction "D_D") (pintype "passive"))
      (node (ref "R30") (pin "1") (pinfunction "1_1") (pintype "passive"))
    )
    (net (code "159") (name "P0_A6") (class "Default")
      (node (ref "J2") (pin "11") (pinfunction "11_11") (pintype "bidirectional"))
      (node (ref "Q33") (pin "D") (pinfunction "D_D") (pintype "passive"))
      (node (ref "R41") (pin "1") (pinfunction "1_1") (pintype "passive"))
    )
    (net (code "160") (name "P0_A7") (class "Default")
      (node (ref "J2") (pin "12") (pinfunction "12_12") (pintype "bidirectional"))
      (node (ref "Q34") (pin "D") (pinfunction "D_D") (pintype "passive"))
      (node (ref "R42") (pin "1") (pinfunction "1_1") (pintype "passive"))
    )
    (net (code "161") (name "P0_A8") (class "Default")
      (node (ref "J2") (pin "13") (pinfunction "13_13") (pintype "bidirectional"))
      (node (ref "Q35") (pin "D") (pinfunction "D_D") (pintype "passive"))
      (node (ref "R43") (pin "1") (pinfunction "1_1") (pintype "passive"))
    )
    (net (code "162") (name "P0_A9") (class "Default")
      (node (ref "J2") (pin "14") (pinfunction "14_14") (pintype "bidirectional"))
      (node (ref "Q36") (pin "D") (pinfunction "D_D") (pintype "passive"))
      (node (ref "R44") (pin "1") (pinfunction "1_1") (pintype "passive"))
    )
    (net (code "163") (name "P0_A10") (class "Default")
      (node (ref "J2") (pin "15") (pinfunction "15_15") (pintype "bidirectional"))
      (node (ref "Q37") (pin "D") (pinfunction "D_D") (pintype "passive"))
      (node (ref "R45") (pin "1") (pinfunction "1_1") (pintype "passive"))
    )
    (net (code "164") (name "P0_A11") (class "Default")
      (node (ref "J2") (pin "16") (pinfunction "16_16") (pintype "bidirectional"))
      (node (ref "Q38") (pin "D") (pinfunction "D_D") (pintype "passive"))
      (node (ref "R46") (pin "1") (pinfunction "1_1") (pintype "passive"))
    )
    (net (code "165") (name "P0_A12") (class "Default")
      (node (ref "J2") (pin "17") (pinfunction "17_17") (pintype "bidirectional"))
      (node (ref "Q39") (pin "D") (pinfunction "D_D") (pintype "passive"))
      (node (ref "R47") (pin "1") (pinfunction "1_1") (pintype "passive"))
    )
    (net (code "166") (name "P0_A13") (class "Default")
      (node (ref "J2") (pin "18") (pinfunction "18_18") (pintype "bidirectional"))
      (node (ref "Q40") (pin "D") (pinfunction "D_D") (pintype "passive"))
      (node (ref "R48") (pin "1") (pinfunction "1_1") (pintype "passive"))
    )
    (net (code "167") (name "P0_A14") (class "Default")
      (node (ref "J2") (pin "19") (pinfunction "19_19") (pintype "bidirectional"))
      (node (ref "Q41") (pin "D") (pinfunction "D_D") (pintype "passive"))
      (node (ref "R49") (pin "1") (pinfunction "1_1") (pintype "passive"))
    )
    (net (code "168") (name "P0_A15") (class "Default")
      (node (ref "J2") (pin "20") (pinfunction "20_20") (pintype "bidirectional"))
      (node (ref "Q42") (pin "D") (pinfunction "D_D") (pintype "passive"))
      (node (ref "R50") (pin "1") (pinfunction "1_1") (pintype "passive"))
    )
    (net (code "169") (name "P0_CS") (class "Default")
      (node (ref "Q23") (pin "G") (pinfunction "G_G") (pintype "passive"))
      (node (ref "Q240") (pin "D") (pinfunction "D_D") (pintype "passive"))
      (node (ref "R246") (pin "1") (pinfunction "1_1") (pintype "passive"))
    )
    (net (code "170") (name "P0_CS_N") (class "Default")
      (node (ref "J2") (pin "1") (pinfunction "1_1") (pintype "bidirectional"))
      (node (ref "Q23") (pin "D") (pinfunction "D_D") (pintype "passive"))
      (node (ref "R31") (pin "1") (pinfunction "1_1") (pintype "passive"))
    )
    (net (code "171") (name "P0_RD0") (class "Default")
      (node (ref "J1") (pin "2") (pinfunction "2_2") (pintype "bidirectional"))
      (node (ref "Q1") (pin "G") (pinfunction "G_G") (pintype "passive"))
    )
    (net (code "172") (name "P0_RD0_B") (class "Default")
      (node (ref "Q169") (pin "G") (pinfunction "G_G") (pintype "passive"))
      (node (ref "Q2") (pin "D") (pinfunction "D_D") (pintype "passive"))
      (node (ref "R17") (pin "1") (pinfunction "1_1") (pintype "passive"))
    )
    (net (code "173") (name "P0_RD1") (class "Default")
      (node (ref "J1") (pin "3") (pinfunction "3_3") (pintype "bidirectional"))
      (node (ref "Q3") (pin "G") (pinfunction "G_G") (pintype "passive"))
    )
    (net (code "174") (name "P0_RD1_B") (class "Default")
      (node (ref "Q174") (pin "G") (pinfunction "G_G") (pintype "passive"))
      (node (ref "Q4") (pin "D") (pinfunction "D_D") (pintype "passive"))
      (node (ref "R18") (pin "1") (pinfunction "1_1") (pintype "passive"))
    )
    (net (code "175") (name "P0_RD2") (class "Default")
      (node (ref "J1") (pin "4") (pinfunction "4_4") (pintype "bidirectional"))
      (node (ref "Q5") (pin "G") (pinfunction "G_G") (pintype "passive"))
    )
    (net (code "176") (name "P0_RD2_B") (class "Default")
      (node (ref "Q179") (pin "G") (pinfunction "G_G") (pintype "passive"))
      (node (ref "Q6") (pin "D") (pinfunction "D_D") (pintype "passive"))
      (node (ref "R19") (pin "1") (pinfunction "1_1") (pintype "passive"))
    )
    (net (code "177") (name "P0_RD3") (class "Default")
      (node (ref "J1") (pin "5") (pinfunction "5_5") (pintype "bidirectional"))
      (node (ref "Q7") (pin "G") (pinfunction "G_G") (pintype "passive"))
    )
    (net (code "178") (name "P0_RD3_B") (class "Default")
      (node (ref "Q184") (pin "G") (pinfunction "G_G") (pintype "passive"))
      (node (ref "Q8") (pin "D") (pinfunction "D_D") (pintype "passive"))
      (node (ref "R20") (pin "1") (pinfunction "1_1") (pintype "passive"))
    )
    (net (code "179") (name "P0_RD4") (class "Default")
      (node (ref "J1") (pin "6") (pinfunction "6_6") (pintype "bidirectional"))
      (node (ref "Q9") (pin "G") (pinfunction "G_G") (pintype "passive"))
    )
    (net (code "180") (name "P0_RD4_B") (class "Default")
      (node (ref "Q10") (pin "D") (pinfunction "D_D") (pintype "passive"))
      (node (ref "Q189") (pin "G") (pinfunction "G_G") (pintype "passive"))
      (node (ref "R21") (pin "1") (pinfunction "1_1") (pintype "passive"))
    )
    (net (code "181") (name "P0_RD5") (class "Default")
      (node (ref "J1") (pin "7") (pinfunction "7_7") (pintype "bidirectional"))
      (node (ref "Q11") (pin "G") (pinfunction "G_G") (pintype "passive"))
    )
    (net (code "182") (name "P0_RD5_B") (class "Default")
      (node (ref "Q12") (pin "D") (pinfunction "D_D") (pintype "passive"))
      (node (ref "Q194") (pin "G") (pinfunction "G_G") (pintype "passive"))
      (node (ref "R22") (pin "1") (pinfunction "1_1") (pintype "passive"))
    )
    (net (code "183") (name "P0_RD6") (class "Default")
      (node (ref "J1") (pin "8") (pinfunction "8_8") (pintype "bidirectional"))
      (node (ref "Q13") (pin "G") (pinfunction "G_G") (pintype "passive"))
    )
    (net (code "184") (name "P0_RD6_B") (class "Default")
      (node (ref "Q14") (pin "D") (pinfunction "D_D") (pintype "passive"))
      (node (ref "Q199") (pin "G") (pinfunction "G_G") (pintype "passive"))
      (node (ref "R23") (pin "1") (pinfunction "1_1") (pintype "passive"))
    )
    (net (code "185") (name "P0_RD7") (class "Default")
      (node (ref "J1") (pin "9") (pinfunction "9_9") (pintype "bidirectional"))
      (node (ref "Q15") (pin "G") (pinfunction "G_G") (pintype "passive"))
    )
    (net (code "186") (name "P0_RD7_B") (class "Default")
      (node (ref "Q16") (pin "D") (pinfunction "D_D") (pintype "passive"))
      (node (ref "Q204") (pin "G") (pinfunction "G_G") (pintype "passive"))
      (node (ref "R24") (pin "1") (pinfunction "1_1") (pintype "passive"))
    )
    (net (code "187") (name "P0_WD0") (class "Default")
      (node (ref "J1") (pin "12") (pinfunction "12_12") (pintype "bidirectional"))
      (node (ref "Q25") (pin "D") (pinfunction "D_D") (pintype "passive"))
      (node (ref "R33") (pin "1") (pinfunction "1_1") (pintype "passive"))
    )
    (net (code "188") (name "P0_WD1") (class "Default")
      (node (ref "J1") (pin "13") (pinfunction "13_13") (pintype "bidirectional"))
      (node (ref "Q26") (pin "D") (pinfunction "D_D") (pintype "passive"))
      (node (ref "R34") (pin "1") (pinfunction "1_1") (pintype "passive"))
    )
    (net (code "189") (name "P0_WD2") (class "Default")
      (node (ref "J1") (pin "14") (pinfunction "14_14") (pintype "bidirectional"))
      (node (ref "Q27") (pin "D") (pinfunction "D_D") (pintype "passive"))
      (node (ref "R35") (pin "1") (pinfunction "1_1") (pintype "passive"))
    )
    (net (code "190") (name "P0_WD3") (class "Default")
      (node (ref "J1") (pin "15") (pinfunction "15_15") (pintype "bidirectional"))
      (node (ref "Q28") (pin "D") (pinfunction "D_D") (pintype "passive"))
      (node (ref "R36") (pin "1") (pinfunction "1_1") (pintype "passive"))
    )
    (net (code "191") (name "P0_WD4") (class "Default")
      (node (ref "J1") (pin "16") (pinfunction "16_16") (pintype "bidirectional"))
      (node (ref "Q29") (pin "D") (pinfunction "D_D") (pintype "passive"))
      (node (ref "R37") (pin "1") (pinfunction "1_1") (pintype "passive"))
    )
    (net (code "192") (name "P0_WD5") (class "Default")
      (node (ref "J1") (pin "17") (pinfunction "17_17") (pintype "bidirectional"))
      (node (ref "Q30") (pin "D") (pinfunction "D_D") (pintype "passive"))
      (node (ref "R38") (pin "1") (pinfunction "1_1") (pintype "passive"))
    )
    (net (code "193") (name "P0_WD6") (class "Default")
      (node (ref "J1") (pin "18") (pinfunction "18_18") (pintype "bidirectional"))
      (node (ref "Q31") (pin "D") (pinfunction "D_D") (pintype "passive"))
      (node (ref "R39") (pin "1") (pinfunction "1_1") (pintype "passive"))
    )
    (net (code "194") (name "P0_WD7") (class "Default")
      (node (ref "J1") (pin "19") (pinfunction "19_19") (pintype "bidirectional"))
      (node (ref "Q32") (pin "D") (pinfunction "D_D") (pintype "passive"))
      (node (ref "R40") (pin "1") (pinfunction "1_1") (pintype "passive"))
    )
    (net (code "195") (name "P0_WE_N") (class "Default")
      (node (ref "J2") (pin "3") (pinfunction "3_3") (pintype "bidirectional"))
      (node (ref "Q24") (pin "D") (pinfunction "D_D") (pintype "passive"))
      (node (ref "R32") (pin "1") (pinfunction "1_1") (pintype "passive"))
    )
    (net (code "196") (name "P1_A0") (class "Default")
      (node (ref "J4") (pin "5") (pinfunction "5_5") (pintype "bidirectional"))
      (node (ref "Q69") (pin "D") (pinfunction "D_D") (pintype "passive"))
      (node (ref "R85") (pin "1") (pinfunction "1_1") (pintype "passive"))
    )
    (net (code "197") (name "P1_A1") (class "Default")
      (node (ref "J4") (pin "6") (pinfunction "6_6") (pintype "bidirectional"))
      (node (ref "Q70") (pin "D") (pinfunction "D_D") (pintype "passive"))
      (node (ref "R86") (pin "1") (pinfunction "1_1") (pintype "passive"))
    )
    (net (code "198") (name "P1_A2") (class "Default")
      (node (ref "J4") (pin "7") (pinfunction "7_7") (pintype "bidirectional"))
      (node (ref "Q71") (pin "D") (pinfunction "D_D") (pintype "passive"))
      (node (ref "R87") (pin "1") (pinfunction "1_1") (pintype "passive"))
    )
    (net (code "199") (name "P1_A3") (class "Default")
      (node (ref "J4") (pin "8") (pinfunction "8_8") (pintype "bidirectional"))
      (node (ref "Q72") (pin "D") (pinfunction "D_D") (pintype "passive"))
      (node (ref "R88") (pin "1") (pinfunction "1_1") (pintype "passive"))
    )
    (net (code "200") (name "P1_A4") (class "Default")
      (node (ref "J4") (pin "9") (pinfunction "9_9") (pintype "bidirectional"))
      (node (ref "Q73") (pin "D") (pinfunction "D_D") (pintype "passive"))
      (node (ref "R89") (pin "1") (pinfunction "1_1") (pintype "passive"))
    )
    (net (code "201") (name "P1_A5") (class "Default")
      (node (ref "J4") (pin "10") (pinfunction "10_10") (pintype "bidirectional"))
      (node (ref "Q74") (pin "D") (pinfunction "D_D") (pintype "passive"))
      (node (ref "R90") (pin "1") (pinfunction "1_1") (pintype "passive"))
    )
    (net (code "202") (name "P1_A6") (class "Default")
      (node (ref "J4") (pin "11") (pinfunction "11_11") (pintype "bidirectional"))
      (node (ref "Q75") (pin "D") (pinfunction "D_D") (pintype "passive"))
      (node (ref "R91") (pin "1") (pinfunction "1_1") (pintype "passive"))
    )
    (net (code "203") (name "P1_A7") (class "Default")
      (node (ref "J4") (pin "12") (pinfunction "12_12") (pintype "bidirectional"))
      (node (ref "Q76") (pin "D") (pinfunction "D_D") (pintype "passive"))
      (node (ref "R92") (pin "1") (pinfunction "1_1") (pintype "passive"))
    )
    (net (code "204") (name "P1_A8") (class "Default")
      (node (ref "J4") (pin "13") (pinfunction "13_13") (pintype "bidirectional"))
      (node (ref "Q77") (pin "D") (pinfunction "D_D") (pintype "passive"))
      (node (ref "R93") (pin "1") (pinfunction "1_1") (pintype "passive"))
    )
    (net (code "205") (name "P1_A9") (class "Default")
      (node (ref "J4") (pin "14") (pinfunction "14_14") (pintype "bidirectional"))
      (node (ref "Q78") (pin "D") (pinfunction "D_D") (pintype "passive"))
      (node (ref "R94") (pin "1") (pinfunction "1_1") (pintype "passive"))
    )
    (net (code "206") (name "P1_A10") (class "Default")
      (node (ref "J4") (pin "15") (pinfunction "15_15") (pintype "bidirectional"))
      (node (ref "Q79") (pin "D") (pinfunction "D_D") (pintype "passive"))
      (node (ref "R95") (pin "1") (pinfunction "1_1") (pintype "passive"))
    )
    (net (code "207") (name "P1_A11") (class "Default")
      (node (ref "J4") (pin "16") (pinfunction "16_16") (pintype "bidirectional"))
      (node (ref "Q80") (pin "D") (pinfunction "D_D") (pintype "passive"))
      (node (ref "R96") (pin "1") (pinfunction "1_1") (pintype "passive"))
    )
    (net (code "208") (name "P1_A12") (class "Default")
      (node (ref "J4") (pin "17") (pinfunction "17_17") (pintype "bidirectional"))
      (node (ref "Q81") (pin "D") (pinfunction "D_D") (pintype "passive"))
      (node (ref "R97") (pin "1") (pinfunction "1_1") (pintype "passive"))
    )
    (net (code "209") (name "P1_A13") (class "Default")
      (node (ref "J4") (pin "18") (pinfunction "18_18") (pintype "bidirectional"))
      (node (ref "Q82") (pin "D") (pinfunction "D_D") (pintype "passive"))
      (node (ref "R98") (pin "1") (pinfunction "1_1") (pintype "passive"))
    )
    (net (code "210") (name "P1_A14") (class "Default")
      (node (ref "J4") (pin "19") (pinfunction "19_19") (pintype "bidirectional"))
      (node (ref "Q83") (pin "D") (pinfunction "D_D") (pintype "passive"))
      (node (ref "R99") (pin "1") (pinfunction "1_1") (pintype "passive"))
    )
    (net (code "211") (name "P1_A15") (class "Default")
      (node (ref "J4") (pin "20") (pinfunction "20_20") (pintype "bidirectional"))
      (node (ref "Q84") (pin "D") (pinfunction "D_D") (pintype "passive"))
      (node (ref "R100") (pin "1") (pinfunction "1_1") (pintype "passive"))
    )
    (net (code "212") (name "P1_CS") (class "Default")
      (node (ref "Q244") (pin "D") (pinfunction "D_D") (pintype "passive"))
      (node (ref "Q59") (pin "G") (pinfunction "G_G") (pintype "passive"))
      (node (ref "R248") (pin "1") (pinfunction "1_1") (pintype "passive"))
    )
    (net (code "213") (name "P1_CS_N") (class "Default")
      (node (ref "J4") (pin "1") (pinfunction "1_1") (pintype "bidirectional"))
      (node (ref "Q59") (pin "D") (pinfunction "D_D") (pintype "passive"))
      (node (ref "R75") (pin "1") (pinfunction "1_1") (pintype "passive"))
    )
    (net (code "214") (name "P1_RD0") (class "Default")
      (node (ref "J3") (pin "2") (pinfunction "2_2") (pintype "bidirectional"))
      (node (ref "Q43") (pin "G") (pinfunction "G_G") (pintype "passive"))
    )
    (net (code "215") (name "P1_RD0_B") (class "Default")
      (node (ref "Q171") (pin "G") (pinfunction "G_G") (pintype "passive"))
      (node (ref "Q44") (pin "D") (pinfunction "D_D") (pintype "passive"))
      (node (ref "R67") (pin "1") (pinfunction "1_1") (pintype "passive"))
    )
    (net (code "216") (name "P1_RD1") (class "Default")
      (node (ref "J3") (pin "3") (pinfunction "3_3") (pintype "bidirectional"))
      (node (ref "Q45") (pin "G") (pinfunction "G_G") (pintype "passive"))
    )
    (net (code "217") (name "P1_RD1_B") (class "Default")
      (node (ref "Q176") (pin "G") (pinfunction "G_G") (pintype "passive"))
      (node (ref "Q46") (pin "D") (pinfunction "D_D") (pintype "passive"))
      (node (ref "R68") (pin "1") (pinfunction "1_1") (pintype "passive"))
    )
    (net (code "218") (name "P1_RD2") (class "Default")
      (node (ref "J3") (pin "4") (pinfunction "4_4") (pintype "bidirectional"))
      (node (ref "Q47") (pin "G") (pinfunction "G_G") (pintype "passive"))
    )
    (net (code "219") (name "P1_RD2_B") (class "Default")
      (node (ref "Q181") (pin "G") (pinfunction "G_G") (pintype "passive"))
      (node (ref "Q48") (pin "D") (pinfunction "D_D") (pintype "passive"))
      (node (ref "R69") (pin "1") (pinfunction "1_1") (pintype "passive"))
    )
    (net (code "220") (name "P1_RD3") (class "Default")
      (node (ref "J3") (pin "5") (pinfunction "5_5") (pintype "bidirectional"))
      (node (ref "Q49") (pin "G") (pinfunction "G_G") (pintype "passive"))
    )
    (net (code "221") (name "P1_RD3_B") (class "Default")
      (node (ref "Q186") (pin "G") (pinfunction "G_G") (pintype "passive"))
      (node (ref "Q50") (pin "D") (pinfunction "D_D") (pintype "passive"))
      (node (ref "R70") (pin "1") (pinfunction "1_1") (pintype "passive"))
    )
    (net (code "222") (name "P1_RD4") (class "Default")
      (node (ref "J3") (pin "6") (pinfunction "6_6") (pintype "bidirectional"))
      (node (ref "Q51") (pin "G") (pinfunction "G_G") (pintype "passive"))
    )
    (net (code "223") (name "P1_RD4_B") (class "Default")
      (node (ref "Q191") (pin "G") (pinfunction "G_G") (pintype "passive"))
      (node (ref "Q52") (pin "D") (pinfunction "D_D") (pintype "passive"))
      (node (ref "R71") (pin "1") (pinfunction "1_1") (pintype "passive"))
    )
    (net (code "224") (name "P1_RD5") (class "Default")
      (node (ref "J3") (pin "7") (pinfunction "7_7") (pintype "bidirectional"))
      (node (ref "Q53") (pin "G") (pinfunction "G_G") (pintype "passive"))
    )
    (net (code "225") (name "P1_RD5_B") (class "Default")
      (node (ref "Q196") (pin "G") (pinfunction "G_G") (pintype "passive"))
      (node (ref "Q54") (pin "D") (pinfunction "D_D") (pintype "passive"))
      (node (ref "R72") (pin "1") (pinfunction "1_1") (pintype "passive"))
    )
    (net (code "226") (name "P1_RD6") (class "Default")
      (node (ref "J3") (pin "8") (pinfunction "8_8") (pintype "bidirectional"))
      (node (ref "Q55") (pin "G") (pinfunction "G_G") (pintype "passive"))
    )
    (net (code "227") (name "P1_RD6_B") (class "Default")
      (node (ref "Q201") (pin "G") (pinfunction "G_G") (pintype "passive"))
      (node (ref "Q56") (pin "D") (pinfunction "D_D") (pintype "passive"))
      (node (ref "R73") (pin "1") (pinfunction "1_1") (pintype "passive"))
    )
    (net (code "228") (name "P1_RD7") (class "Default")
      (node (ref "J3") (pin "9") (pinfunction "9_9") (pintype "bidirectional"))
      (node (ref "Q57") (pin "G") (pinfunction "G_G") (pintype "passive"))
    )
    (net (code "229") (name "P1_RD7_B") (class "Default")
      (node (ref "Q206") (pin "G") (pinfunction "G_G") (pintype "passive"))
      (node (ref "Q58") (pin "D") (pinfunction "D_D") (pintype "passive"))
      (node (ref "R74") (pin "1") (pinfunction "1_1") (pintype "passive"))
    )
    (net (code "230") (name "P1_WD0") (class "Default")
      (node (ref "J3") (pin "12") (pinfunction "12_12") (pintype "bidirectional"))
      (node (ref "Q61") (pin "D") (pinfunction "D_D") (pintype "passive"))
      (node (ref "R77") (pin "1") (pinfunction "1_1") (pintype "passive"))
    )
    (net (code "231") (name "P1_WD1") (class "Default")
      (node (ref "J3") (pin "13") (pinfunction "13_13") (pintype "bidirectional"))
      (node (ref "Q62") (pin "D") (pinfunction "D_D") (pintype "passive"))
      (node (ref "R78") (pin "1") (pinfunction "1_1") (pintype "passive"))
    )
    (net (code "232") (name "P1_WD2") (class "Default")
      (node (ref "J3") (pin "14") (pinfunction "14_14") (pintype "bidirectional"))
      (node (ref "Q63") (pin "D") (pinfunction "D_D") (pintype "passive"))
      (node (ref "R79") (pin "1") (pinfunction "1_1") (pintype "passive"))
    )
    (net (code "233") (name "P1_WD3") (class "Default")
      (node (ref "J3") (pin "15") (pinfunction "15_15") (pintype "bidirectional"))
      (node (ref "Q64") (pin "D") (pinfunction "D_D") (pintype "passive"))
      (node (ref "R80") (pin "1") (pinfunction "1_1") (pintype "passive"))
    )
    (net (code "234") (name "P1_WD4") (class "Default")
      (node (ref "J3") (pin "16") (pinfunction "16_16") (pintype "bidirectional"))
      (node (ref "Q65") (pin "D") (pinfunction "D_D") (pintype "passive"))
      (node (ref "R81") (pin "1") (pinfunction "1_1") (pintype "passive"))
    )
    (net (code "235") (name "P1_WD5") (class "Default")
      (node (ref "J3") (pin "17") (pinfunction "17_17") (pintype "bidirectional"))
      (node (ref "Q66") (pin "D") (pinfunction "D_D") (pintype "passive"))
      (node (ref "R82") (pin "1") (pinfunction "1_1") (pintype "passive"))
    )
    (net (code "236") (name "P1_WD6") (class "Default")
      (node (ref "J3") (pin "18") (pinfunction "18_18") (pintype "bidirectional"))
      (node (ref "Q67") (pin "D") (pinfunction "D_D") (pintype "passive"))
      (node (ref "R83") (pin "1") (pinfunction "1_1") (pintype "passive"))
    )
    (net (code "237") (name "P1_WD7") (class "Default")
      (node (ref "J3") (pin "19") (pinfunction "19_19") (pintype "bidirectional"))
      (node (ref "Q68") (pin "D") (pinfunction "D_D") (pintype "passive"))
      (node (ref "R84") (pin "1") (pinfunction "1_1") (pintype "passive"))
    )
    (net (code "238") (name "P1_WE_N") (class "Default")
      (node (ref "J4") (pin "3") (pinfunction "3_3") (pintype "bidirectional"))
      (node (ref "Q60") (pin "D") (pinfunction "D_D") (pintype "passive"))
      (node (ref "R76") (pin "1") (pinfunction "1_1") (pintype "passive"))
    )
    (net (code "239") (name "P2_A0") (class "Default")
      (node (ref "J6") (pin "5") (pinfunction "5_5") (pintype "bidirectional"))
      (node (ref "Q111") (pin "D") (pinfunction "D_D") (pintype "passive"))
      (node (ref "R135") (pin "1") (pinfunction "1_1") (pintype "passive"))
    )
    (net (code "240") (name "P2_A1") (class "Default")
      (node (ref "J6") (pin "6") (pinfunction "6_6") (pintype "bidirectional"))
      (node (ref "Q112") (pin "D") (pinfunction "D_D") (pintype "passive"))
      (node (ref "R136") (pin "1") (pinfunction "1_1") (pintype "passive"))
    )
    (net (code "241") (name "P2_A2") (class "Default")
      (node (ref "J6") (pin "7") (pinfunction "7_7") (pintype "bidirectional"))
      (node (ref "Q113") (pin "D") (pinfunction "D_D") (pintype "passive"))
      (node (ref "R137") (pin "1") (pinfunction "1_1") (pintype "passive"))
    )
    (net (code "242") (name "P2_A3") (class "Default")
      (node (ref "J6") (pin "8") (pinfunction "8_8") (pintype "bidirectional"))
      (node (ref "Q114") (pin "D") (pinfunction "D_D") (pintype "passive"))
      (node (ref "R138") (pin "1") (pinfunction "1_1") (pintype "passive"))
    )
    (net (code "243") (name "P2_A4") (class "Default")
      (node (ref "J6") (pin "9") (pinfunction "9_9") (pintype "bidirectional"))
      (node (ref "Q115") (pin "D") (pinfunction "D_D") (pintype "passive"))
      (node (ref "R139") (pin "1") (pinfunction "1_1") (pintype "passive"))
    )
    (net (code "244") (name "P2_A5") (class "Default")
      (node (ref "J6") (pin "10") (pinfunction "10_10") (pintype "bidirectional"))
      (node (ref "Q116") (pin "D") (pinfunction "D_D") (pintype "passive"))
      (node (ref "R140") (pin "1") (pinfunction "1_1") (pintype "passive"))
    )
    (net (code "245") (name "P2_A6") (class "Default")
      (node (ref "J6") (pin "11") (pinfunction "11_11") (pintype "bidirectional"))
      (node (ref "Q117") (pin "D") (pinfunction "D_D") (pintype "passive"))
      (node (ref "R141") (pin "1") (pinfunction "1_1") (pintype "passive"))
    )
    (net (code "246") (name "P2_A7") (class "Default")
      (node (ref "J6") (pin "12") (pinfunction "12_12") (pintype "bidirectional"))
      (node (ref "Q118") (pin "D") (pinfunction "D_D") (pintype "passive"))
      (node (ref "R142") (pin "1") (pinfunction "1_1") (pintype "passive"))
    )
    (net (code "247") (name "P2_A8") (class "Default")
      (node (ref "J6") (pin "13") (pinfunction "13_13") (pintype "bidirectional"))
      (node (ref "Q119") (pin "D") (pinfunction "D_D") (pintype "passive"))
      (node (ref "R143") (pin "1") (pinfunction "1_1") (pintype "passive"))
    )
    (net (code "248") (name "P2_A9") (class "Default")
      (node (ref "J6") (pin "14") (pinfunction "14_14") (pintype "bidirectional"))
      (node (ref "Q120") (pin "D") (pinfunction "D_D") (pintype "passive"))
      (node (ref "R144") (pin "1") (pinfunction "1_1") (pintype "passive"))
    )
    (net (code "249") (name "P2_A10") (class "Default")
      (node (ref "J6") (pin "15") (pinfunction "15_15") (pintype "bidirectional"))
      (node (ref "Q121") (pin "D") (pinfunction "D_D") (pintype "passive"))
      (node (ref "R145") (pin "1") (pinfunction "1_1") (pintype "passive"))
    )
    (net (code "250") (name "P2_A11") (class "Default")
      (node (ref "J6") (pin "16") (pinfunction "16_16") (pintype "bidirectional"))
      (node (ref "Q122") (pin "D") (pinfunction "D_D") (pintype "passive"))
      (node (ref "R146") (pin "1") (pinfunction "1_1") (pintype "passive"))
    )
    (net (code "251") (name "P2_A12") (class "Default")
      (node (ref "J6") (pin "17") (pinfunction "17_17") (pintype "bidirectional"))
      (node (ref "Q123") (pin "D") (pinfunction "D_D") (pintype "passive"))
      (node (ref "R147") (pin "1") (pinfunction "1_1") (pintype "passive"))
    )
    (net (code "252") (name "P2_A13") (class "Default")
      (node (ref "J6") (pin "18") (pinfunction "18_18") (pintype "bidirectional"))
      (node (ref "Q124") (pin "D") (pinfunction "D_D") (pintype "passive"))
      (node (ref "R148") (pin "1") (pinfunction "1_1") (pintype "passive"))
    )
    (net (code "253") (name "P2_A14") (class "Default")
      (node (ref "J6") (pin "19") (pinfunction "19_19") (pintype "bidirectional"))
      (node (ref "Q125") (pin "D") (pinfunction "D_D") (pintype "passive"))
      (node (ref "R149") (pin "1") (pinfunction "1_1") (pintype "passive"))
    )
    (net (code "254") (name "P2_A15") (class "Default")
      (node (ref "J6") (pin "20") (pinfunction "20_20") (pintype "bidirectional"))
      (node (ref "Q126") (pin "D") (pinfunction "D_D") (pintype "passive"))
      (node (ref "R150") (pin "1") (pinfunction "1_1") (pintype "passive"))
    )
    (net (code "255") (name "P2_CS") (class "Default")
      (node (ref "Q101") (pin "G") (pinfunction "G_G") (pintype "passive"))
      (node (ref "Q248") (pin "D") (pinfunction "D_D") (pintype "passive"))
      (node (ref "R250") (pin "1") (pinfunction "1_1") (pintype "passive"))
    )
    (net (code "256") (name "P2_CS_N") (class "Default")
      (node (ref "J6") (pin "1") (pinfunction "1_1") (pintype "bidirectional"))
      (node (ref "Q101") (pin "D") (pinfunction "D_D") (pintype "passive"))
      (node (ref "R125") (pin "1") (pinfunction "1_1") (pintype "passive"))
    )
    (net (code "257") (name "P2_RD0") (class "Default")
      (node (ref "J5") (pin "2") (pinfunction "2_2") (pintype "bidirectional"))
      (node (ref "Q85") (pin "G") (pinfunction "G_G") (pintype "passive"))
    )
    (net (code "258") (name "P2_RD0_B") (class "Default")
      (node (ref "Q172") (pin "G") (pinfunction "G_G") (pintype "passive"))
      (node (ref "Q86") (pin "D") (pinfunction "D_D") (pintype "passive"))
      (node (ref "R117") (pin "1") (pinfunction "1_1") (pintype "passive"))
    )
    (net (code "259") (name "P2_RD1") (class "Default")
      (node (ref "J5") (pin "3") (pinfunction "3_3") (pintype "bidirectional"))
      (node (ref "Q87") (pin "G") (pinfunction "G_G") (pintype "passive"))
    )
    (net (code "260") (name "P2_RD1_B") (class "Default")
      (node (ref "Q177") (pin "G") (pinfunction "G_G") (pintype "passive"))
      (node (ref "Q88") (pin "D") (pinfunction "D_D") (pintype "passive"))
      (node (ref "R118") (pin "1") (pinfunction "1_1") (pintype "passive"))
    )
    (net (code "261") (name "P2_RD2") (class "Default")
      (node (ref "J5") (pin "4") (pinfunction "4_4") (pintype "bidirectional"))
      (node (ref "Q89") (pin "G") (pinfunction "G_G") (pintype "passive"))
    )
    (net (code "262") (name "P2_RD2_B") (class "Default")
      (node (ref "Q182") (pin "G") (pinfunction "G_G") (pintype "passive"))
      (node (ref "Q90") (pin "D") (pinfunction "D_D") (pintype "passive"))
      (node (ref "R119") (pin "1") (pinfunction "1_1") (pintype "passive"))
    )
    (net (code "263") (name "P2_RD3") (class "Default")
      (node (ref "J5") (pin "5") (pinfunction "5_5") (pintype "bidirectional"))
      (node (ref "Q91") (pin "G") (pinfunction "G_G") (pintype "passive"))
    )
    (net (code "264") (name "P2_RD3_B") (class "Default")
      (node (ref "Q187") (pin "G") (pinfunction "G_G") (pintype "passive"))
      (node (ref "Q92") (pin "D") (pinfunction "D_D") (pintype "passive"))
      (node (ref "R120") (pin "1") (pinfunction "1_1") (pintype "passive"))
    )
    (net (code "265") (name "P2_RD4") (class "Default")
      (node (ref "J5") (pin "6") (pinfunction "6_6") (pintype "bidirectional"))
      (node (ref "Q93") (pin "G") (pinfunction "G_G") (pintype "passive"))
    )
    (net (code "266") (name "P2_RD4_B") (class "Default")
      (node (ref "Q192") (pin "G") (pinfunction "G_G") (pintype "passive"))
      (node (ref "Q94") (pin "D") (pinfunction "D_D") (pintype "passive"))
      (node (ref "R121") (pin "1") (pinfunction "1_1") (pintype "passive"))
    )
    (net (code "267") (name "P2_RD5") (class "Default")
      (node (ref "J5") (pin "7") (pinfunction "7_7") (pintype "bidirectional"))
      (node (ref "Q95") (pin "G") (pinfunction "G_G") (pintype "passive"))
    )
    (net (code "268") (name "P2_RD5_B") (class "Default")
      (node (ref "Q197") (pin "G") (pinfunction "G_G") (pintype "passive"))
      (node (ref "Q96") (pin "D") (pinfunction "D_D") (pintype "passive"))
      (node (ref "R122") (pin "1") (pinfunction "1_1") (pintype "passive"))
    )
    (net (code "269") (name "P2_RD6") (class "Default")
      (node (ref "J5") (pin "8") (pinfunction "8_8") (pintype "bidirectional"))
      (node (ref "Q97") (pin "G") (pinfunction "G_G") (pintype "passive"))
    )
    (net (code "270") (name "P2_RD6_B") (class "Default")
      (node (ref "Q202") (pin "G") (pinfunction "G_G") (pintype "passive"))
      (node (ref "Q98") (pin "D") (pinfunction "D_D") (pintype "passive"))
      (node (ref "R123") (pin "1") (pinfunction "1_1") (pintype "passive"))
    )
    (net (code "271") (name "P2_RD7") (class "Default")
      (node (ref "J5") (pin "9") (pinfunction "9_9") (pintype "bidirectional"))
      (node (ref "Q99") (pin "G") (pinfunction "G_G") (pintype "passive"))
    )
    (net (code "272") (name "P2_RD7_B") (class "Default")
      (node (ref "Q100") (pin "D") (pinfunction "D_D") (pintype "passive"))
      (node (ref "Q207") (pin "G") (pinfunction "G_G") (pintype "passive"))
      (node (ref "R124") (pin "1") (pinfunction "1_1") (pintype "passive"))
    )
    (net (code "273") (name "P2_WD0") (class "Default")
      (node (ref "J5") (pin "12") (pinfunction "12_12") (pintype "bidirectional"))
      (node (ref "Q103") (pin "D") (pinfunction "D_D") (pintype "passive"))
      (node (ref "R127") (pin "1") (pinfunction "1_1") (pintype "passive"))
    )
    (net (code "274") (name "P2_WD1") (class "Default")
      (node (ref "J5") (pin "13") (pinfunction "13_13") (pintype "bidirectional"))
      (node (ref "Q104") (pin "D") (pinfunction "D_D") (pintype "passive"))
      (node (ref "R128") (pin "1") (pinfunction "1_1") (pintype "passive"))
    )
    (net (code "275") (name "P2_WD2") (class "Default")
      (node (ref "J5") (pin "14") (pinfunction "14_14") (pintype "bidirectional"))
      (node (ref "Q105") (pin "D") (pinfunction "D_D") (pintype "passive"))
      (node (ref "R129") (pin "1") (pinfunction "1_1") (pintype "passive"))
    )
    (net (code "276") (name "P2_WD3") (class "Default")
      (node (ref "J5") (pin "15") (pinfunction "15_15") (pintype "bidirectional"))
      (node (ref "Q106") (pin "D") (pinfunction "D_D") (pintype "passive"))
      (node (ref "R130") (pin "1") (pinfunction "1_1") (pintype "passive"))
    )
    (net (code "277") (name "P2_WD4") (class "Default")
      (node (ref "J5") (pin "16") (pinfunction "16_16") (pintype "bidirectional"))
      (node (ref "Q107") (pin "D") (pinfunction "D_D") (pintype "passive"))
      (node (ref "R131") (pin "1") (pinfunction "1_1") (pintype "passive"))
    )
    (net (code "278") (name "P2_WD5") (class "Default")
      (node (ref "J5") (pin "17") (pinfunction "17_17") (pintype "bidirectional"))
      (node (ref "Q108") (pin "D") (pinfunction "D_D") (pintype "passive"))
      (node (ref "R132") (pin "1") (pinfunction "1_1") (pintype "passive"))
    )
    (net (code "279") (name "P2_WD6") (class "Default")
      (node (ref "J5") (pin "18") (pinfunction "18_18") (pintype "bidirectional"))
      (node (ref "Q109") (pin "D") (pinfunction "D_D") (pintype "passive"))
      (node (ref "R133") (pin "1") (pinfunction "1_1") (pintype "passive"))
    )
    (net (code "280") (name "P2_WD7") (class "Default")
      (node (ref "J5") (pin "19") (pinfunction "19_19") (pintype "bidirectional"))
      (node (ref "Q110") (pin "D") (pinfunction "D_D") (pintype "passive"))
      (node (ref "R134") (pin "1") (pinfunction "1_1") (pintype "passive"))
    )
    (net (code "281") (name "P2_WE_N") (class "Default")
      (node (ref "J6") (pin "3") (pinfunction "3_3") (pintype "bidirectional"))
      (node (ref "Q102") (pin "D") (pinfunction "D_D") (pintype "passive"))
      (node (ref "R126") (pin "1") (pinfunction "1_1") (pintype "passive"))
    )
    (net (code "282") (name "P3_A0") (class "Default")
      (node (ref "J8") (pin "5") (pinfunction "5_5") (pintype "bidirectional"))
      (node (ref "Q153") (pin "D") (pinfunction "D_D") (pintype "passive"))
      (node (ref "R185") (pin "1") (pinfunction "1_1") (pintype "passive"))
    )
    (net (code "283") (name "P3_A1") (class "Default")
      (node (ref "J8") (pin "6") (pinfunction "6_6") (pintype "bidirectional"))
      (node (ref "Q154") (pin "D") (pinfunction "D_D") (pintype "passive"))
      (node (ref "R186") (pin "1") (pinfunction "1_1") (pintype "passive"))
    )
    (net (code "284") (name "P3_A2") (class "Default")
      (node (ref "J8") (pin "7") (pinfunction "7_7") (pintype "bidirectional"))
      (node (ref "Q155") (pin "D") (pinfunction "D_D") (pintype "passive"))
      (node (ref "R187") (pin "1") (pinfunction "1_1") (pintype "passive"))
    )
    (net (code "285") (name "P3_A3") (class "Default")
      (node (ref "J8") (pin "8") (pinfunction "8_8") (pintype "bidirectional"))
      (node (ref "Q156") (pin "D") (pinfunction "D_D") (pintype "passive"))
      (node (ref "R188") (pin "1") (pinfunction "1_1") (pintype "passive"))
    )
    (net (code "286") (name "P3_A4") (class "Default")
      (node (ref "J8") (pin "9") (pinfunction "9_9") (pintype "bidirectional"))
      (node (ref "Q157") (pin "D") (pinfunction "D_D") (pintype "passive"))
      (node (ref "R189") (pin "1") (pinfunction "1_1") (pintype "passive"))
    )
    (net (code "287") (name "P3_A5") (class "Default")
      (node (ref "J8") (pin "10") (pinfunction "10_10") (pintype "bidirectional"))
      (node (ref "Q158") (pin "D") (pinfunction "D_D") (pintype "passive"))
      (node (ref "R190") (pin "1") (pinfunction "1_1") (pintype "passive"))
    )
    (net (code "288") (name "P3_A6") (class "Default")
      (node (ref "J8") (pin "11") (pinfunction "11_11") (pintype "bidirectional"))
      (node (ref "Q159") (pin "D") (pinfunction "D_D") (pintype "passive"))
      (node (ref "R191") (pin "1") (pinfunction "1_1") (pintype "passive"))
    )
    (net (code "289") (name "P3_A7") (class "Default")
      (node (ref "J8") (pin "12") (pinfunction "12_12") (pintype "bidirectional"))
      (node (ref "Q160") (pin "D") (pinfunction "D_D") (pintype "passive"))
      (node (ref "R192") (pin "1") (pinfunction "1_1") (pintype "passive"))
    )
    (net (code "290") (name "P3_A8") (class "Default")
      (node (ref "J8") (pin "13") (pinfunction "13_13") (pintype "bidirectional"))
      (node (ref "Q161") (pin "D") (pinfunction "D_D") (pintype "passive"))
      (node (ref "R193") (pin "1") (pinfunction "1_1") (pintype "passive"))
    )
    (net (code "291") (name "P3_A9") (class "Default")
      (node (ref "J8") (pin "14") (pinfunction "14_14") (pintype "bidirectional"))
      (node (ref "Q162") (pin "D") (pinfunction "D_D") (pintype "passive"))
      (node (ref "R194") (pin "1") (pinfunction "1_1") (pintype "passive"))
    )
    (net (code "292") (name "P3_A10") (class "Default")
      (node (ref "J8") (pin "15") (pinfunction "15_15") (pintype "bidirectional"))
      (node (ref "Q163") (pin "D") (pinfunction "D_D") (pintype "passive"))
      (node (ref "R195") (pin "1") (pinfunction "1_1") (pintype "passive"))
    )
    (net (code "293") (name "P3_A11") (class "Default")
      (node (ref "J8") (pin "16") (pinfunction "16_16") (pintype "bidirectional"))
      (node (ref "Q164") (pin "D") (pinfunction "D_D") (pintype "passive"))
      (node (ref "R196") (pin "1") (pinfunction "1_1") (pintype "passive"))
    )
    (net (code "294") (name "P3_A12") (class "Default")
      (node (ref "J8") (pin "17") (pinfunction "17_17") (pintype "bidirectional"))
      (node (ref "Q165") (pin "D") (pinfunction "D_D") (pintype "passive"))
      (node (ref "R197") (pin "1") (pinfunction "1_1") (pintype "passive"))
    )
    (net (code "295") (name "P3_A13") (class "Default")
      (node (ref "J8") (pin "18") (pinfunction "18_18") (pintype "bidirectional"))
      (node (ref "Q166") (pin "D") (pinfunction "D_D") (pintype "passive"))
      (node (ref "R198") (pin "1") (pinfunction "1_1") (pintype "passive"))
    )
    (net (code "296") (name "P3_A14") (class "Default")
      (node (ref "J8") (pin "19") (pinfunction "19_19") (pintype "bidirectional"))
      (node (ref "Q167") (pin "D") (pinfunction "D_D") (pintype "passive"))
      (node (ref "R199") (pin "1") (pinfunction "1_1") (pintype "passive"))
    )
    (net (code "297") (name "P3_A15") (class "Default")
      (node (ref "J8") (pin "20") (pinfunction "20_20") (pintype "bidirectional"))
      (node (ref "Q168") (pin "D") (pinfunction "D_D") (pintype "passive"))
      (node (ref "R200") (pin "1") (pinfunction "1_1") (pintype "passive"))
    )
    (net (code "298") (name "P3_CS") (class "Default")
      (node (ref "Q143") (pin "G") (pinfunction "G_G") (pintype "passive"))
      (node (ref "Q252") (pin "D") (pinfunction "D_D") (pintype "passive"))
      (node (ref "R252") (pin "1") (pinfunction "1_1") (pintype "passive"))
    )
    (net (code "299") (name "P3_CS_N") (class "Default")
      (node (ref "J8") (pin "1") (pinfunction "1_1") (pintype "bidirectional"))
      (node (ref "Q143") (pin "D") (pinfunction "D_D") (pintype "passive"))
      (node (ref "R175") (pin "1") (pinfunction "1_1") (pintype "passive"))
    )
    (net (code "300") (name "P3_RD0") (class "Default")
      (node (ref "J7") (pin "2") (pinfunction "2_2") (pintype "bidirectional"))
      (node (ref "Q127") (pin "G") (pinfunction "G_G") (pintype "passive"))
    )
    (net (code "301") (name "P3_RD0_B") (class "Default")
      (node (ref "Q128") (pin "D") (pinfunction "D_D") (pintype "passive"))
      (node (ref "Q173") (pin "G") (pinfunction "G_G") (pintype "passive"))
      (node (ref "R167") (pin "1") (pinfunction "1_1") (pintype "passive"))
    )
    (net (code "302") (name "P3_RD1") (class "Default")
      (node (ref "J7") (pin "3") (pinfunction "3_3") (pintype "bidirectional"))
      (node (ref "Q129") (pin "G") (pinfunction "G_G") (pintype "passive"))
    )
    (net (code "303") (name "P3_RD1_B") (class "Default")
      (node (ref "Q130") (pin "D") (pinfunction "D_D") (pintype "passive"))
      (node (ref "Q178") (pin "G") (pinfunction "G_G") (pintype "passive"))
      (node (ref "R168") (pin "1") (pinfunction "1_1") (pintype "passive"))
    )
    (net (code "304") (name "P3_RD2") (class "Default")
      (node (ref "J7") (pin "4") (pinfunction "4_4") (pintype "bidirectional"))
      (node (ref "Q131") (pin "G") (pinfunction "G_G") (pintype "passive"))
    )
    (net (code "305") (name "P3_RD2_B") (class "Default")
      (node (ref "Q132") (pin "D") (pinfunction "D_D") (pintype "passive"))
      (node (ref "Q183") (pin "G") (pinfunction "G_G") (pintype "passive"))
      (node (ref "R169") (pin "1") (pinfunction "1_1") (pintype "passive"))
    )
    (net (code "306") (name "P3_RD3") (class "Default")
      (node (ref "J7") (pin "5") (pinfunction "5_5") (pintype "bidirectional"))
      (node (ref "Q133") (pin "G") (pinfunction "G_G") (pintype "passive"))
    )
    (net (code "307") (name "P3_RD3_B") (class "Default")
      (node (ref "Q134") (pin "D") (pinfunction "D_D") (pintype "passive"))
      (node (ref "Q188") (pin "G") (pinfunction "G_G") (pintype "passive"))
      (node (ref "R170") (pin "1") (pinfunction "1_1") (pintype "passive"))
    )
    (net (code "308") (name "P3_RD4") (class "Default")
      (node (ref "J7") (pin "6") (pinfunction "6_6") (pintype "bidirectional"))
      (node (ref "Q135") (pin "G") (pinfunction "G_G") (pintype "passive"))
    )
    (net (code "309") (name "P3_RD4_B") (class "Default")
      (node (ref "Q136") (pin "D") (pinfunction "D_D") (pintype "passive"))
      (node (ref "Q193") (pin "G") (pinfunction "G_G") (pintype "passive"))
      (node (ref "R171") (pin "1") (pinfunction "1_1") (pintype "passive"))
    )
    (net (code "310") (name "P3_RD5") (class "Default")
      (node (ref "J7") (pin "7") (pinfunction "7_7") (pintype "bidirectional"))
      (node (ref "Q137") (pin "G") (pinfunction "G_G") (pintype "passive"))
    )
    (net (code "311") (name "P3_RD5_B") (class "Default")
      (node (ref "Q138") (pin "D") (pinfunction "D_D") (pintype "passive"))
      (node (ref "Q198") (pin "G") (pinfunction "G_G") (pintype "passive"))
      (node (ref "R172") (pin "1") (pinfunction "1_1") (pintype "passive"))
    )
    (net (code "312") (name "P3_RD6") (class "Default")
      (node (ref "J7") (pin "8") (pinfunction "8_8") (pintype "bidirectional"))
      (node (ref "Q139") (pin "G") (pinfunction "G_G") (pintype "passive"))
    )
    (net (code "313") (name "P3_RD6_B") (class "Default")
      (node (ref "Q140") (pin "D") (pinfunction "D_D") (pintype "passive"))
      (node (ref "Q203") (pin "G") (pinfunction "G_G") (pintype "passive"))
      (node (ref "R173") (pin "1") (pinfunction "1_1") (pintype "passive"))
    )
    (net (code "314") (name "P3_RD7") (class "Default")
      (node (ref "J7") (pin "9") (pinfunction "9_9") (pintype "bidirectional"))
      (node (ref "Q141") (pin "G") (pinfunction "G_G") (pintype "passive"))
    )
    (net (code "315") (name "P3_RD7_B") (class "Default")
      (node (ref "Q142") (pin "D") (pinfunction "D_D") (pintype "passive"))
      (node (ref "Q208") (pin "G") (pinfunction "G_G") (pintype "passive"))
      (node (ref "R174") (pin "1") (pinfunction "1_1") (pintype "passive"))
    )
    (net (code "316") (name "P3_WD0") (class "Default")
      (node (ref "J7") (pin "12") (pinfunction "12_12") (pintype "bidirectional"))
      (node (ref "Q145") (pin "D") (pinfunction "D_D") (pintype "passive"))
      (node (ref "R177") (pin "1") (pinfunction "1_1") (pintype "passive"))
    )
    (net (code "317") (name "P3_WD1") (class "Default")
      (node (ref "J7") (pin "13") (pinfunction "13_13") (pintype "bidirectional"))
      (node (ref "Q146") (pin "D") (pinfunction "D_D") (pintype "passive"))
      (node (ref "R178") (pin "1") (pinfunction "1_1") (pintype "passive"))
    )
    (net (code "318") (name "P3_WD2") (class "Default")
      (node (ref "J7") (pin "14") (pinfunction "14_14") (pintype "bidirectional"))
      (node (ref "Q147") (pin "D") (pinfunction "D_D") (pintype "passive"))
      (node (ref "R179") (pin "1") (pinfunction "1_1") (pintype "passive"))
    )
    (net (code "319") (name "P3_WD3") (class "Default")
      (node (ref "J7") (pin "15") (pinfunction "15_15") (pintype "bidirectional"))
      (node (ref "Q148") (pin "D") (pinfunction "D_D") (pintype "passive"))
      (node (ref "R180") (pin "1") (pinfunction "1_1") (pintype "passive"))
    )
    (net (code "320") (name "P3_WD4") (class "Default")
      (node (ref "J7") (pin "16") (pinfunction "16_16") (pintype "bidirectional"))
      (node (ref "Q149") (pin "D") (pinfunction "D_D") (pintype "passive"))
      (node (ref "R181") (pin "1") (pinfunction "1_1") (pintype "passive"))
    )
    (net (code "321") (name "P3_WD5") (class "Default")
      (node (ref "J7") (pin "17") (pinfunction "17_17") (pintype "bidirectional"))
      (node (ref "Q150") (pin "D") (pinfunction "D_D") (pintype "passive"))
      (node (ref "R182") (pin "1") (pinfunction "1_1") (pintype "passive"))
    )
    (net (code "322") (name "P3_WD6") (class "Default")
      (node (ref "J7") (pin "18") (pinfunction "18_18") (pintype "bidirectional"))
      (node (ref "Q151") (pin "D") (pinfunction "D_D") (pintype "passive"))
      (node (ref "R183") (pin "1") (pinfunction "1_1") (pintype "passive"))
    )
    (net (code "323") (name "P3_WD7") (class "Default")
      (node (ref "J7") (pin "19") (pinfunction "19_19") (pintype "bidirectional"))
      (node (ref "Q152") (pin "D") (pinfunction "D_D") (pintype "passive"))
      (node (ref "R184") (pin "1") (pinfunction "1_1") (pintype "passive"))
    )
    (net (code "324") (name "P3_WE_N") (class "Default")
      (node (ref "J8") (pin "3") (pinfunction "3_3") (pintype "bidirectional"))
      (node (ref "Q144") (pin "D") (pinfunction "D_D") (pintype "passive"))
      (node (ref "R176") (pin "1") (pinfunction "1_1") (pintype "passive"))
    )
    (net (code "325") (name "RD0") (class "Default")
      (node (ref "J9") (pin "2") (pinfunction "2_2") (pintype "bidirectional"))
      (node (ref "Q170") (pin "D") (pinfunction "D_D") (pintype "passive"))
      (node (ref "R257") (pin "1") (pinfunction "1_1") (pintype "passive"))
    )
    (net (code "326") (name "RD1") (class "Default")
      (node (ref "J9") (pin "3") (pinfunction "3_3") (pintype "bidirectional"))
      (node (ref "Q175") (pin "D") (pinfunction "D_D") (pintype "passive"))
      (node (ref "R258") (pin "1") (pinfunction "1_1") (pintype "passive"))
    )
    (net (code "327") (name "RD2") (class "Default")
      (node (ref "J9") (pin "4") (pinfunction "4_4") (pintype "bidirectional"))
      (node (ref "Q180") (pin "D") (pinfunction "D_D") (pintype "passive"))
      (node (ref "R259") (pin "1") (pinfunction "1_1") (pintype "passive"))
    )
    (net (code "328") (name "RD3") (class "Default")
      (node (ref "J9") (pin "5") (pinfunction "5_5") (pintype "bidirectional"))
      (node (ref "Q185") (pin "D") (pinfunction "D_D") (pintype "passive"))
      (node (ref "R260") (pin "1") (pinfunction "1_1") (pintype "passive"))
    )
    (net (code "329") (name "RD4") (class "Default")
      (node (ref "J9") (pin "6") (pinfunction "6_6") (pintype "bidirectional"))
      (node (ref "Q190") (pin "D") (pinfunction "D_D") (pintype "passive"))
      (node (ref "R253") (pin "1") (pinfunction "1_1") (pintype "passive"))
    )
    (net (code "330") (name "RD5") (class "Default")
      (node (ref "J9") (pin "7") (pinfunction "7_7") (pintype "bidirectional"))
      (node (ref "Q195") (pin "D") (pinfunction "D_D") (pintype "passive"))
      (node (ref "R254") (pin "1") (pinfunction "1_1") (pintype "passive"))
    )
    (net (code "331") (name "RD6") (class "Default")
      (node (ref "J9") (pin "8") (pinfunction "8_8") (pintype "bidirectional"))
      (node (ref "Q200") (pin "D") (pinfunction "D_D") (pintype "passive"))
      (node (ref "R255") (pin "1") (pinfunction "1_1") (pintype "passive"))
    )
    (net (code "332") (name "RD7") (class "Default")
      (node (ref "J9") (pin "9") (pinfunction "9_9") (pintype "bidirectional"))
      (node (ref "Q205") (pin "D") (pinfunction "D_D") (pintype "passive"))
      (node (ref "R256") (pin "1") (pinfunction "1_1") (pintype "passive"))
    )
    (net (code "333") (name "SEL_A0") (class "Default")
      (node (ref "Q233") (pin "D") (pinfunction "D_D") (pintype "passive"))
      (node (ref "Q241") (pin "G") (pinfunction "G_G") (pintype "passive"))
      (node (ref "Q249") (pin "G") (pinfunction "G_G") (pintype "passive"))
      (node (ref "R241") (pin "1") (pinfunction "1_1") (pintype "passive"))
    )
    (net (code "334") (name "SEL_A0_N") (class "Default")
      (node (ref "J11") (pin "1") (pinfunction "1_1") (pintype "passive"))
      (node (ref "Q233") (pin "G") (pinfunction "G_G") (pintype "passive"))
      (node (ref "Q237") (pin "G") (pinfunction "G_G") (pintype "passive"))
      (node (ref "Q245") (pin "G") (pinfunction "G_G") (pintype "passive"))
    )
    (net (code "335") (name "SEL_A1") (class "Default")
      (node (ref "Q234") (pin "D") (pinfunction "D_D") (pintype "passive"))
      (node (ref "Q246") (pin "G") (pinfunction "G_G") (pintype "passive"))
      (node (ref "Q250") (pin "G") (pinfunction "G_G") (pintype "passive"))
      (node (ref "R242") (pin "1") (pinfunction "1_1") (pintype "passive"))
    )
    (net (code "336") (name "SEL_A1_N") (class "Default")
      (node (ref "J11") (pin "2") (pinfunction "2_2") (pintype "passive"))
      (node (ref "Q234") (pin "G") (pinfunction "G_G") (pintype "passive"))
      (node (ref "Q238") (pin "G") (pinfunction "G_G") (pintype "passive"))
      (node (ref "Q242") (pin "G") (pinfunction "G_G") (pintype "passive"))
    )
    (net (code "337") (name "WD0") (class "Default")
      (node (ref "J9") (pin "12") (pinfunction "12_12") (pintype "bidirectional"))
      (node (ref "Q209") (pin "G") (pinfunction "G_G") (pintype "passive"))
    )
    (net (code "338") (name "WD0_N") (class "Default")
      (node (ref "Q103") (pin "G") (pinfunction "G_G") (pintype "passive"))
      (node (ref "Q145") (pin "G") (pinfunction "G_G") (pintype "passive"))
      (node (ref "Q209") (pin "D") (pinfunction "D_D") (pintype "passive"))
      (node (ref "Q25") (pin "G") (pinfunction "G_G") (pintype "passive"))
      (node (ref "Q61") (pin "G") (pinfunction "G_G") (pintype "passive"))
      (node (ref "R217") (pin "1") (pinfunction "1_1") (pintype "passive"))
    )
    (net (code "339") (name "WD1") (class "Default")
      (node (ref "J9") (pin "13") (pinfunction "13_13") (pintype "bidirectional"))
      (node (ref "Q210") (pin "G") (pinfunction "G_G") (pintype "passive"))
    )
    (net (code "340") (name "WD1_N") (class "Default")
      (node (ref "Q104") (pin "G") (pinfunction "G_G") (pintype "passive"))
      (node (ref "Q146") (pin "G") (pinfunction "G_G") (pintype "passive"))
      (node (ref "Q210") (pin "D") (pinfunction "D_D") (pintype "passive"))
      (node (ref "Q26") (pin "G") (pinfunction "G_G") (pintype "passive"))
      (node (ref "Q62") (pin "G") (pinfunction "G_G") (pintype "passive"))
      (node (ref "R218") (pin "1") (pinfunction "1_1") (pintype "passive"))
    )
    (net (code "341") (name "WD2") (class "Default")
      (node (ref "J9") (pin "14") (pinfunction "14_14") (pintype "bidirectional"))
      (node (ref "Q211") (pin "G") (pinfunction "G_G") (pintype "passive"))
    )
    (net (code "342") (name "WD2_N") (class "Default")
      (node (ref "Q105") (pin "G") (pinfunction "G_G") (pintype "passive"))
      (node (ref "Q147") (pin "G") (pinfunction "G_G") (pintype "passive"))
      (node (ref "Q211") (pin "D") (pinfunction "D_D") (pintype "passive"))
      (node (ref "Q27") (pin "G") (pinfunction "G_G") (pintype "passive"))
      (node (ref "Q63") (pin "G") (pinfunction "G_G") (pintype "passive"))
      (node (ref "R219") (pin "1") (pinfunction "1_1") (pintype "passive"))
    )
    (net (code "343") (name "WD3") (class "Default")
      (node (ref "J9") (pin "15") (pinfunction "15_15") (pintype "bidirectional"))
      (node (ref "Q212") (pin "G") (pinfunction "G_G") (pintype "passive"))
    )
    (net (code "344") (name "WD3_N") (class "Default")
      (node (ref "Q106") (pin "G") (pinfunction "G_G") (pintype "passive"))
      (node (ref "Q148") (pin "G") (pinfunction "G_G") (pintype "passive"))
      (node (ref "Q212") (pin "D") (pinfunction "D_D") (pintype "passive"))
      (node (ref "Q28") (pin "G") (pinfunction "G_G") (pintype "passive"))
      (node (ref "Q64") (pin "G") (pinfunction "G_G") (pintype "passive"))
      (node (ref "R220") (pin "1") (pinfunction "1_1") (pintype "passive"))
    )
    (net (code "345") (name "WD4") (class "Default")
      (node (ref "J9") (pin "16") (pinfunction "16_16") (pintype "bidirectional"))
      (node (ref "Q213") (pin "G") (pinfunction "G_G") (pintype "passive"))
    )
    (net (code "346") (name "WD4_N") (class "Default")
      (node (ref "Q107") (pin "G") (pinfunction "G_G") (pintype "passive"))
      (node (ref "Q149") (pin "G") (pinfunction "G_G") (pintype "passive"))
      (node (ref "Q213") (pin "D") (pinfunction "D_D") (pintype "passive"))
      (node (ref "Q29") (pin "G") (pinfunction "G_G") (pintype "passive"))
      (node (ref "Q65") (pin "G") (pinfunction "G_G") (pintype "passive"))
      (node (ref "R221") (pin "1") (pinfunction "1_1") (pintype "passive"))
    )
    (net (code "347") (name "WD5") (class "Default")
      (node (ref "J9") (pin "17") (pinfunction "17_17") (pintype "bidirectional"))
      (node (ref "Q214") (pin "G") (pinfunction "G_G") (pintype "passive"))
    )
    (net (code "348") (name "WD5_N") (class "Default")
      (node (ref "Q108") (pin "G") (pinfunction "G_G") (pintype "passive"))
      (node (ref "Q150") (pin "G") (pinfunction "G_G") (pintype "passive"))
      (node (ref "Q214") (pin "D") (pinfunction "D_D") (pintype "passive"))
      (node (ref "Q30") (pin "G") (pinfunction "G_G") (pintype "passive"))
      (node (ref "Q66") (pin "G") (pinfunction "G_G") (pintype "passive"))
      (node (ref "R222") (pin "1") (pinfunction "1_1") (pintype "passive"))
    )
    (net (code "349") (name "WD6") (class "Default")
      (node (ref "J9") (pin "18") (pinfunction "18_18") (pintype "bidirectional"))
      (node (ref "Q215") (pin "G") (pinfunction "G_G") (pintype "passive"))
    )
    (net (code "350") (name "WD6_N") (class "Default")
      (node (ref "Q109") (pin "G") (pinfunction "G_G") (pintype "passive"))
      (node (ref "Q151") (pin "G") (pinfunction "G_G") (pintype "passive"))
      (node (ref "Q215") (pin "D") (pinfunction "D_D") (pintype "passive"))
      (node (ref "Q31") (pin "G") (pinfunction "G_G") (pintype "passive"))
      (node (ref "Q67") (pin "G") (pinfunction "G_G") (pintype "passive"))
      (node (ref "R223") (pin "1") (pinfunction "1_1") (pintype "passive"))
    )
    (net (code "351") (name "WD7") (class "Default")
      (node (ref "J9") (pin "19") (pinfunction "19_19") (pintype "bidirectional"))
      (node (ref "Q216") (pin "G") (pinfunction "G_G") (pintype "passive"))
    )
    (net (code "352") (name "WD7_N") (class "Default")
      (node (ref "Q110") (pin "G") (pinfunction "G_G") (pintype "passive"))
      (node (ref "Q152") (pin "G") (pinfunction "G_G") (pintype "passive"))
      (node (ref "Q216") (pin "D") (pinfunction "D_D") (pintype "passive"))
      (node (ref "Q32") (pin "G") (pinfunction "G_G") (pintype "passive"))
      (node (ref "Q68") (pin "G") (pinfunction "G_G") (pintype "passive"))
      (node (ref "R224") (pin "1") (pinfunction "1_1") (pintype "passive"))
    )
    (net (code "353") (name "WE") (class "Default")
      (node (ref "Q102") (pin "G") (pinfunction "G_G") (pintype "passive"))
      (node (ref "Q144") (pin "G") (pinfunction "G_G") (pintype "passive"))
      (node (ref "Q236") (pin "D") (pinfunction "D_D") (pintype "passive"))
      (node (ref "Q24") (pin "G") (pinfunction "G_G") (pintype "passive"))
      (node (ref "Q60") (pin "G") (pinfunction "G_G") (pintype "passive"))
      (node (ref "R244") (pin "1") (pinfunction "1_1") (pintype "passive"))
    )
    (net (code "354") (name "WE_N") (class "Default")
      (node (ref "J10") (pin "3") (pinfunction "3_3") (pintype "bidirectional"))
      (node (ref "Q236") (pin "G") (pinfunction "G_G") (pintype "passive"))
    )
  )
)
